# 4x16MUX_3.net
KiCad netlist of a schematic drawn in EAGLE
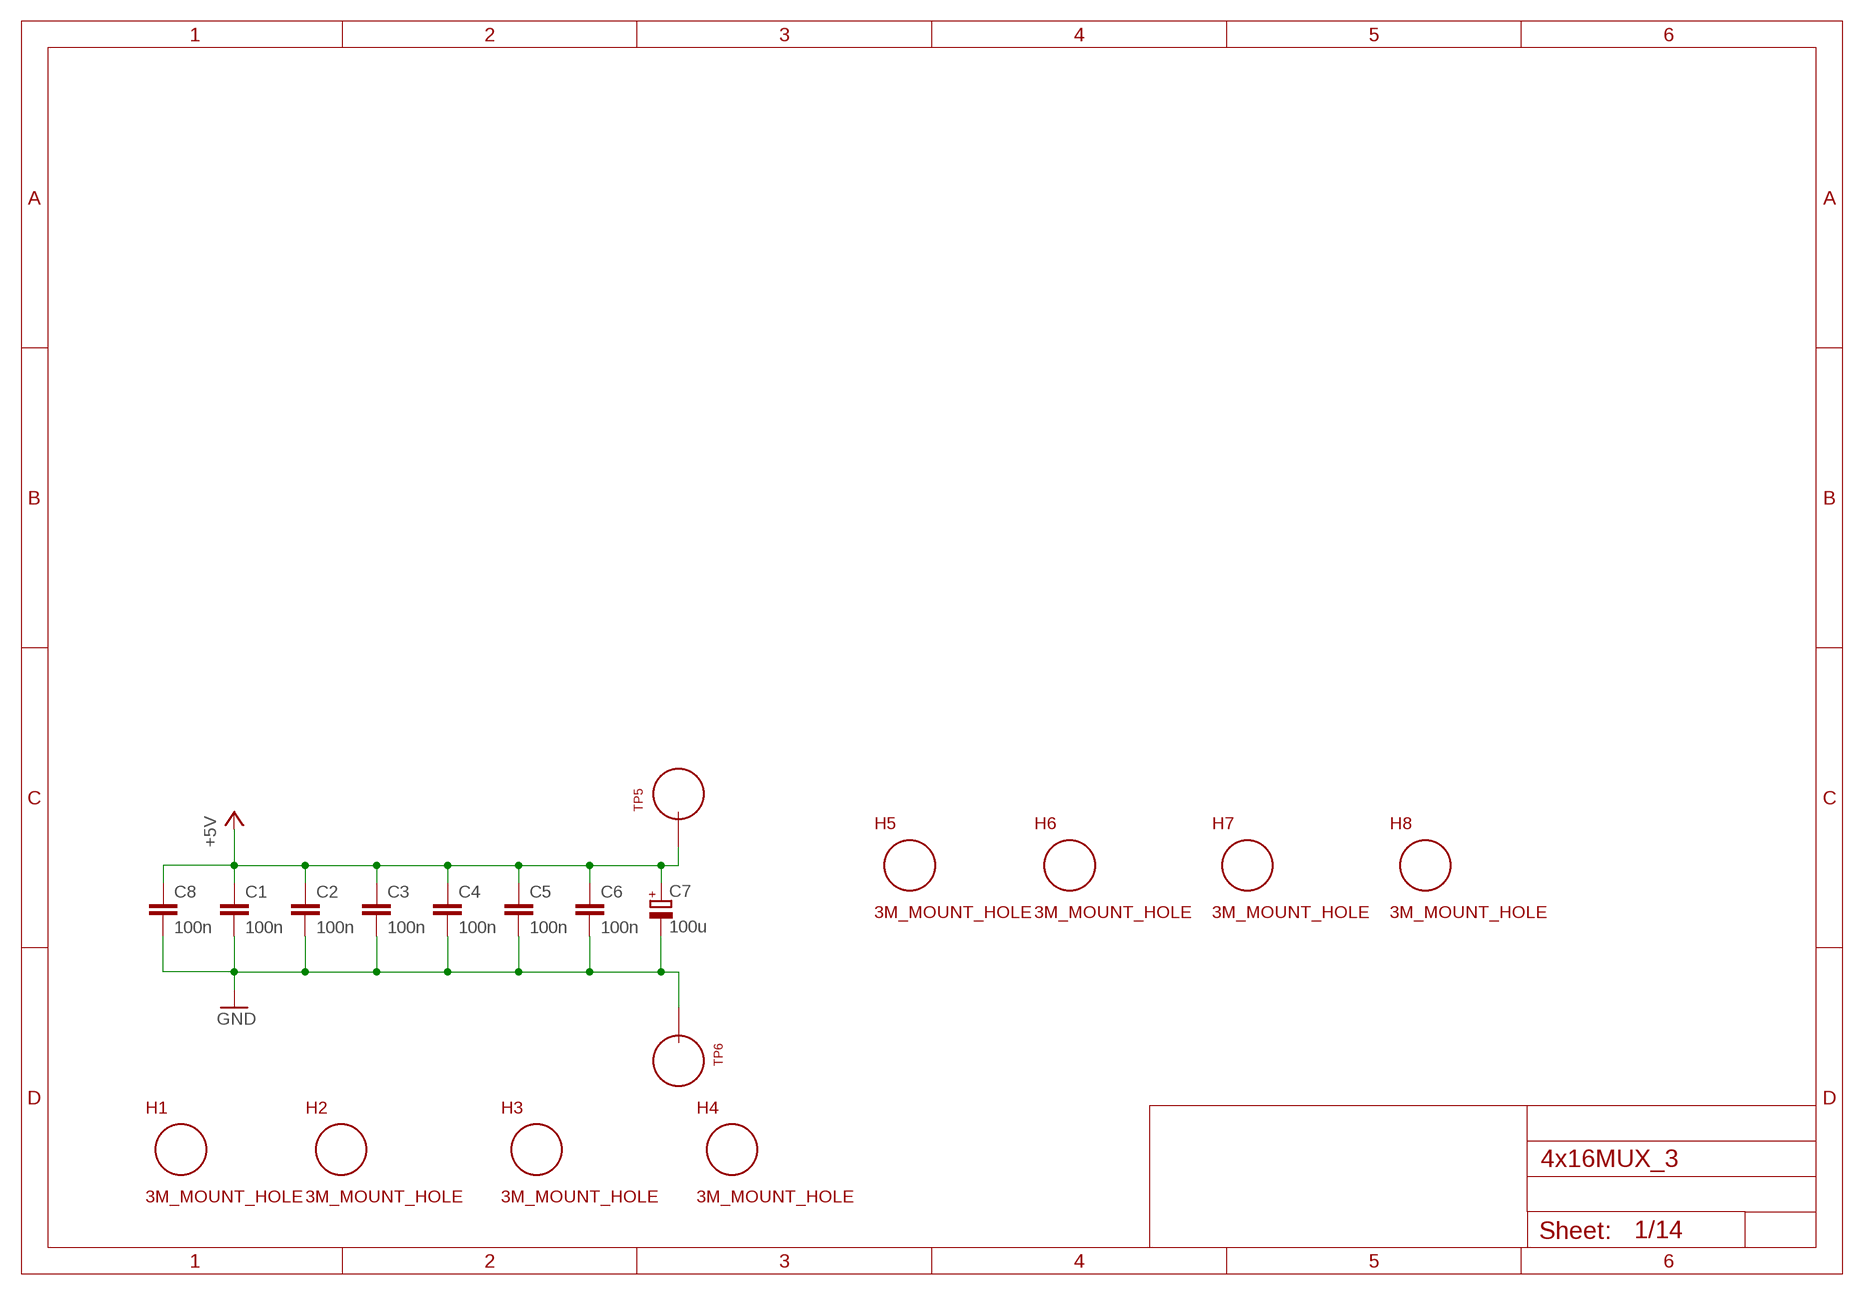
[diagram p0: schematic, sheet 1]
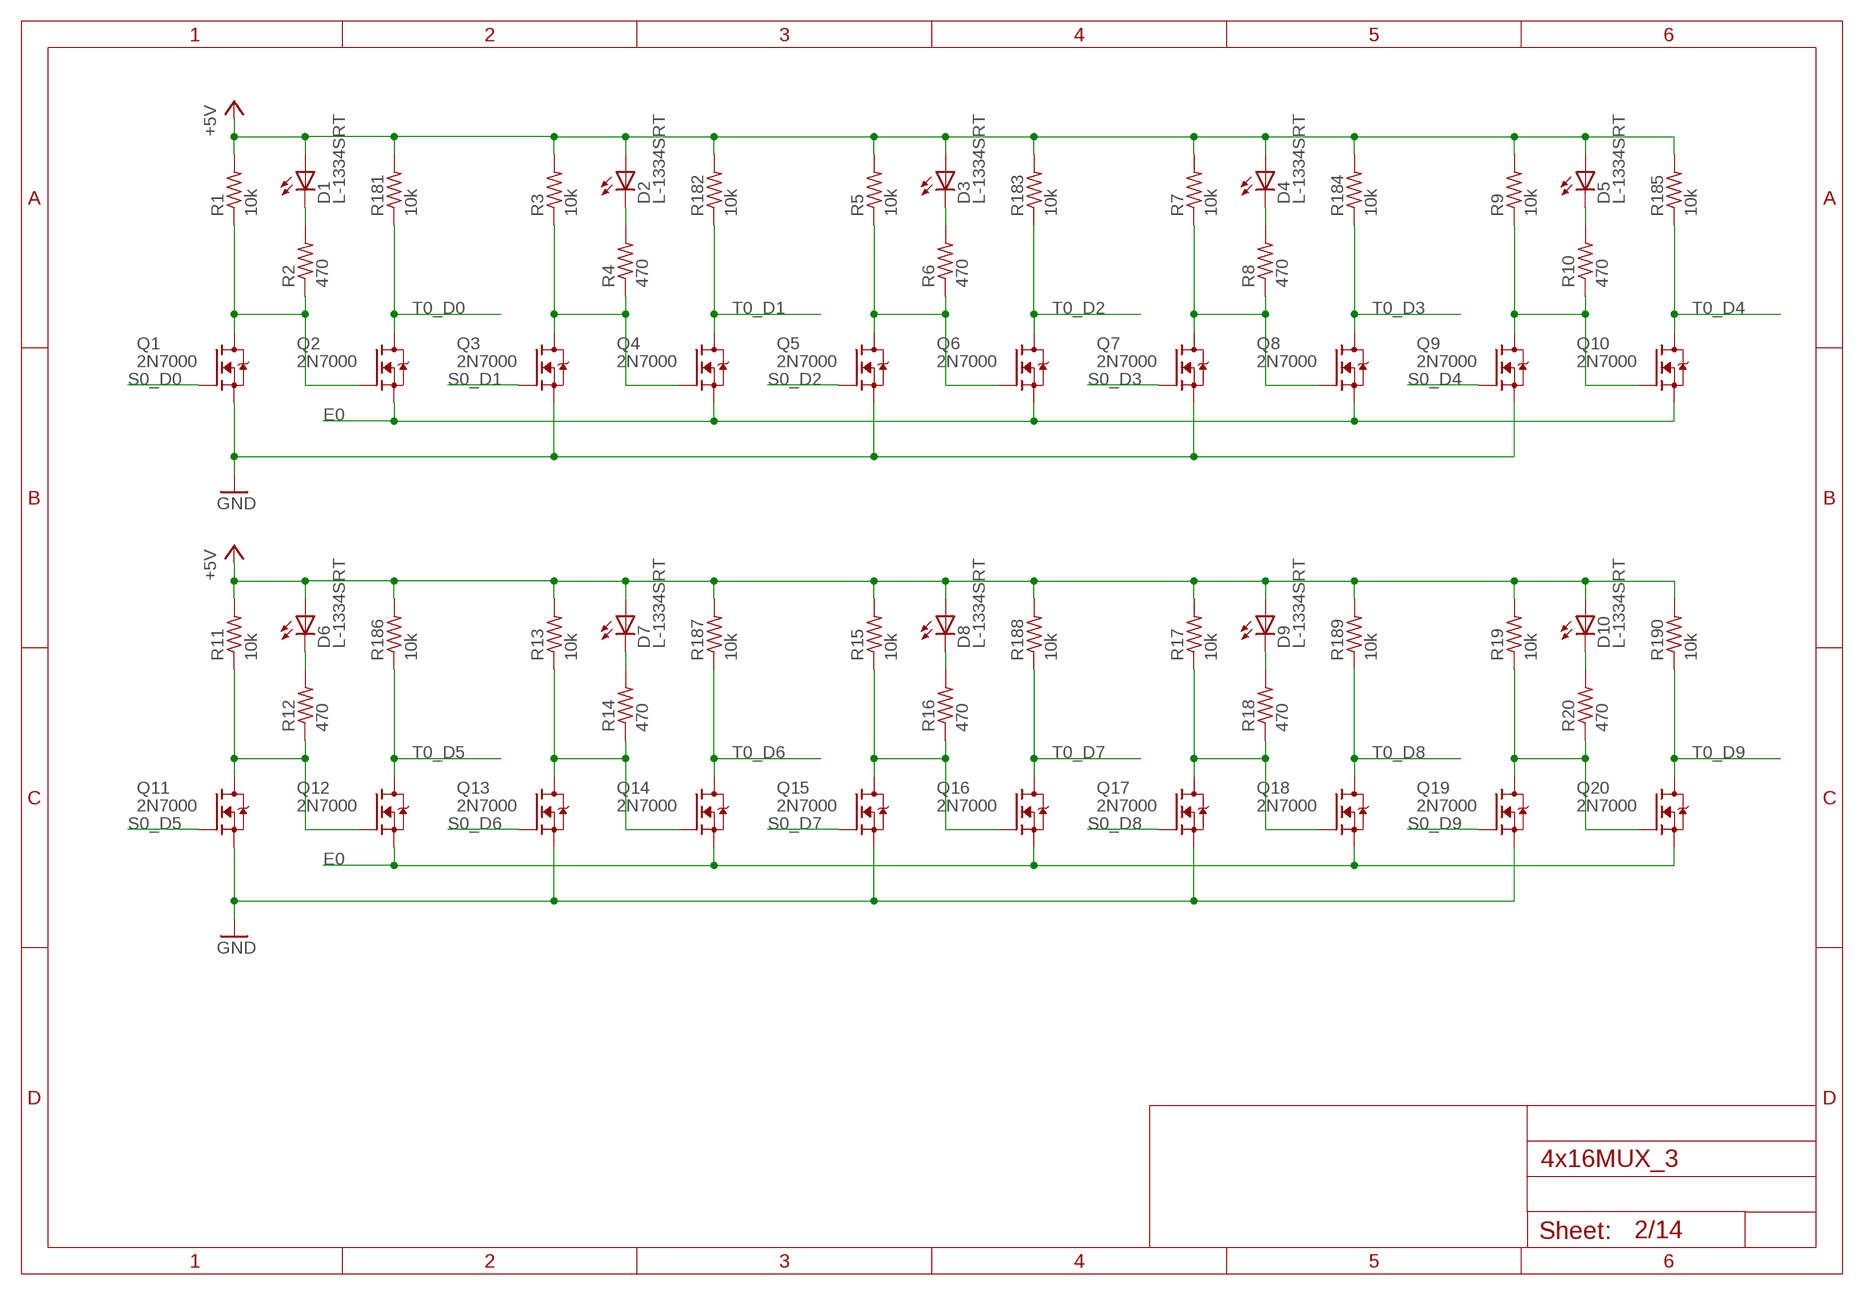
[diagram p1: schematic, sheet 2]
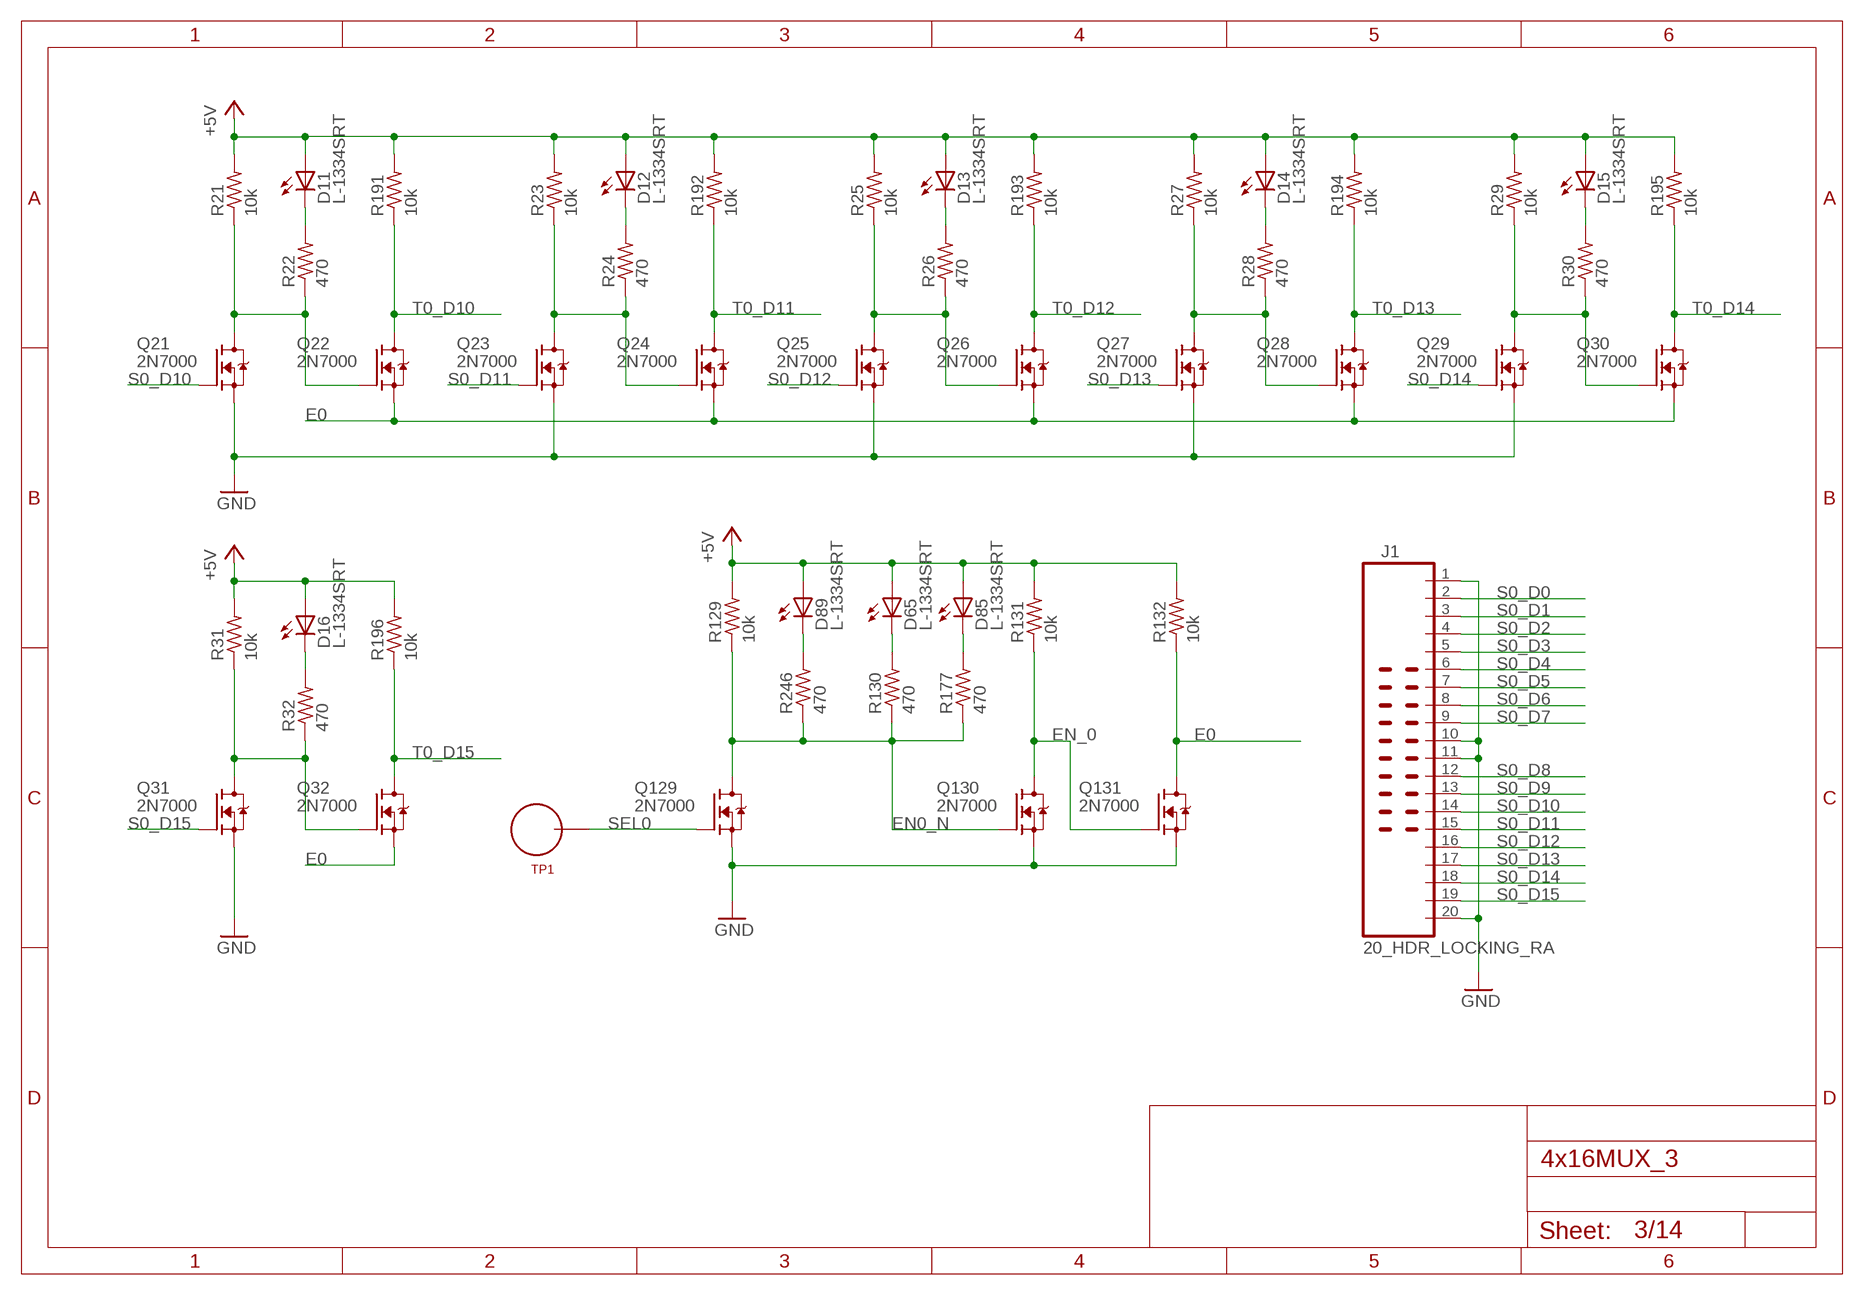
[diagram p2: schematic, sheet 3]
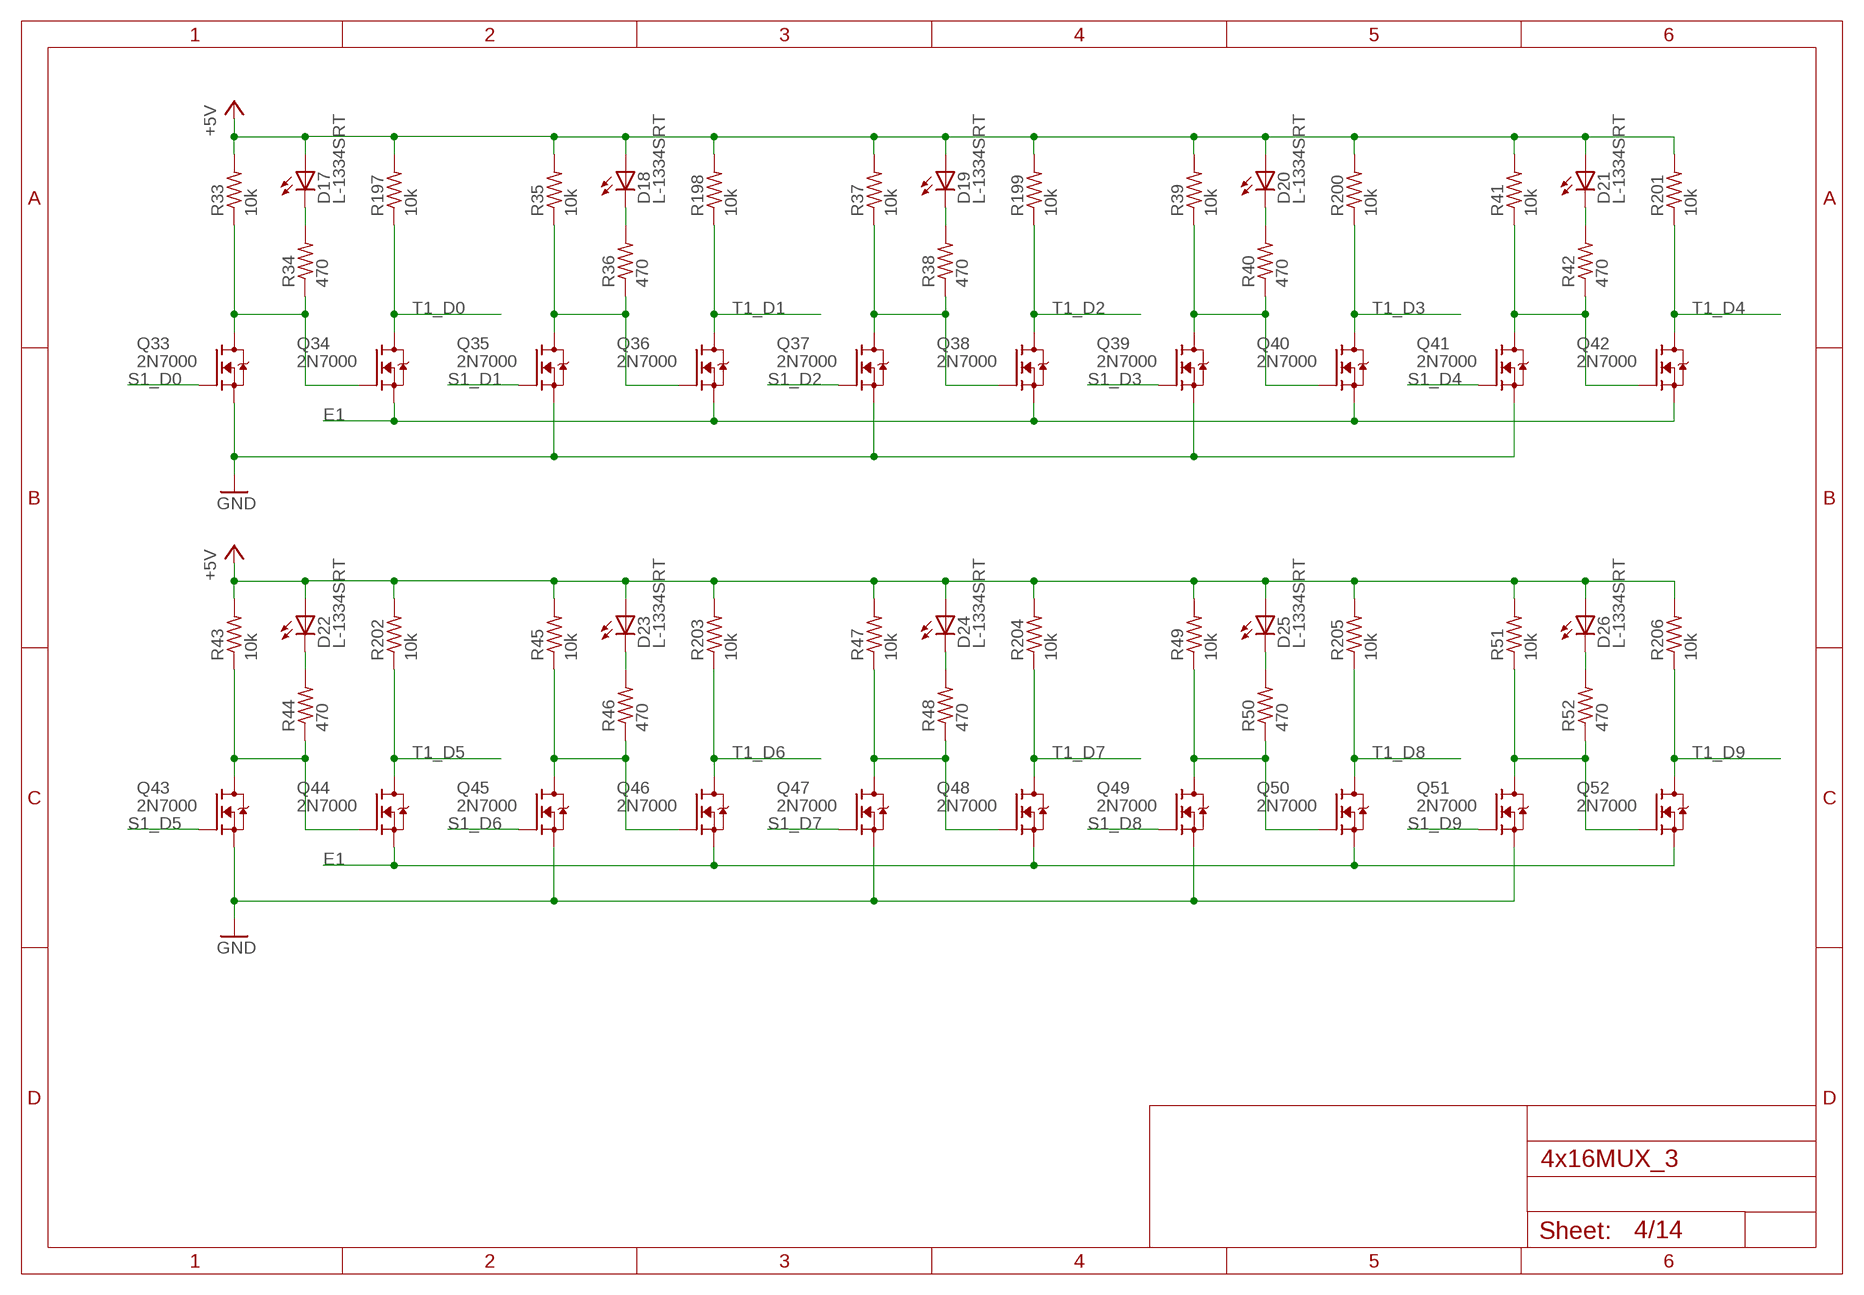
[diagram p3: schematic, sheet 4]
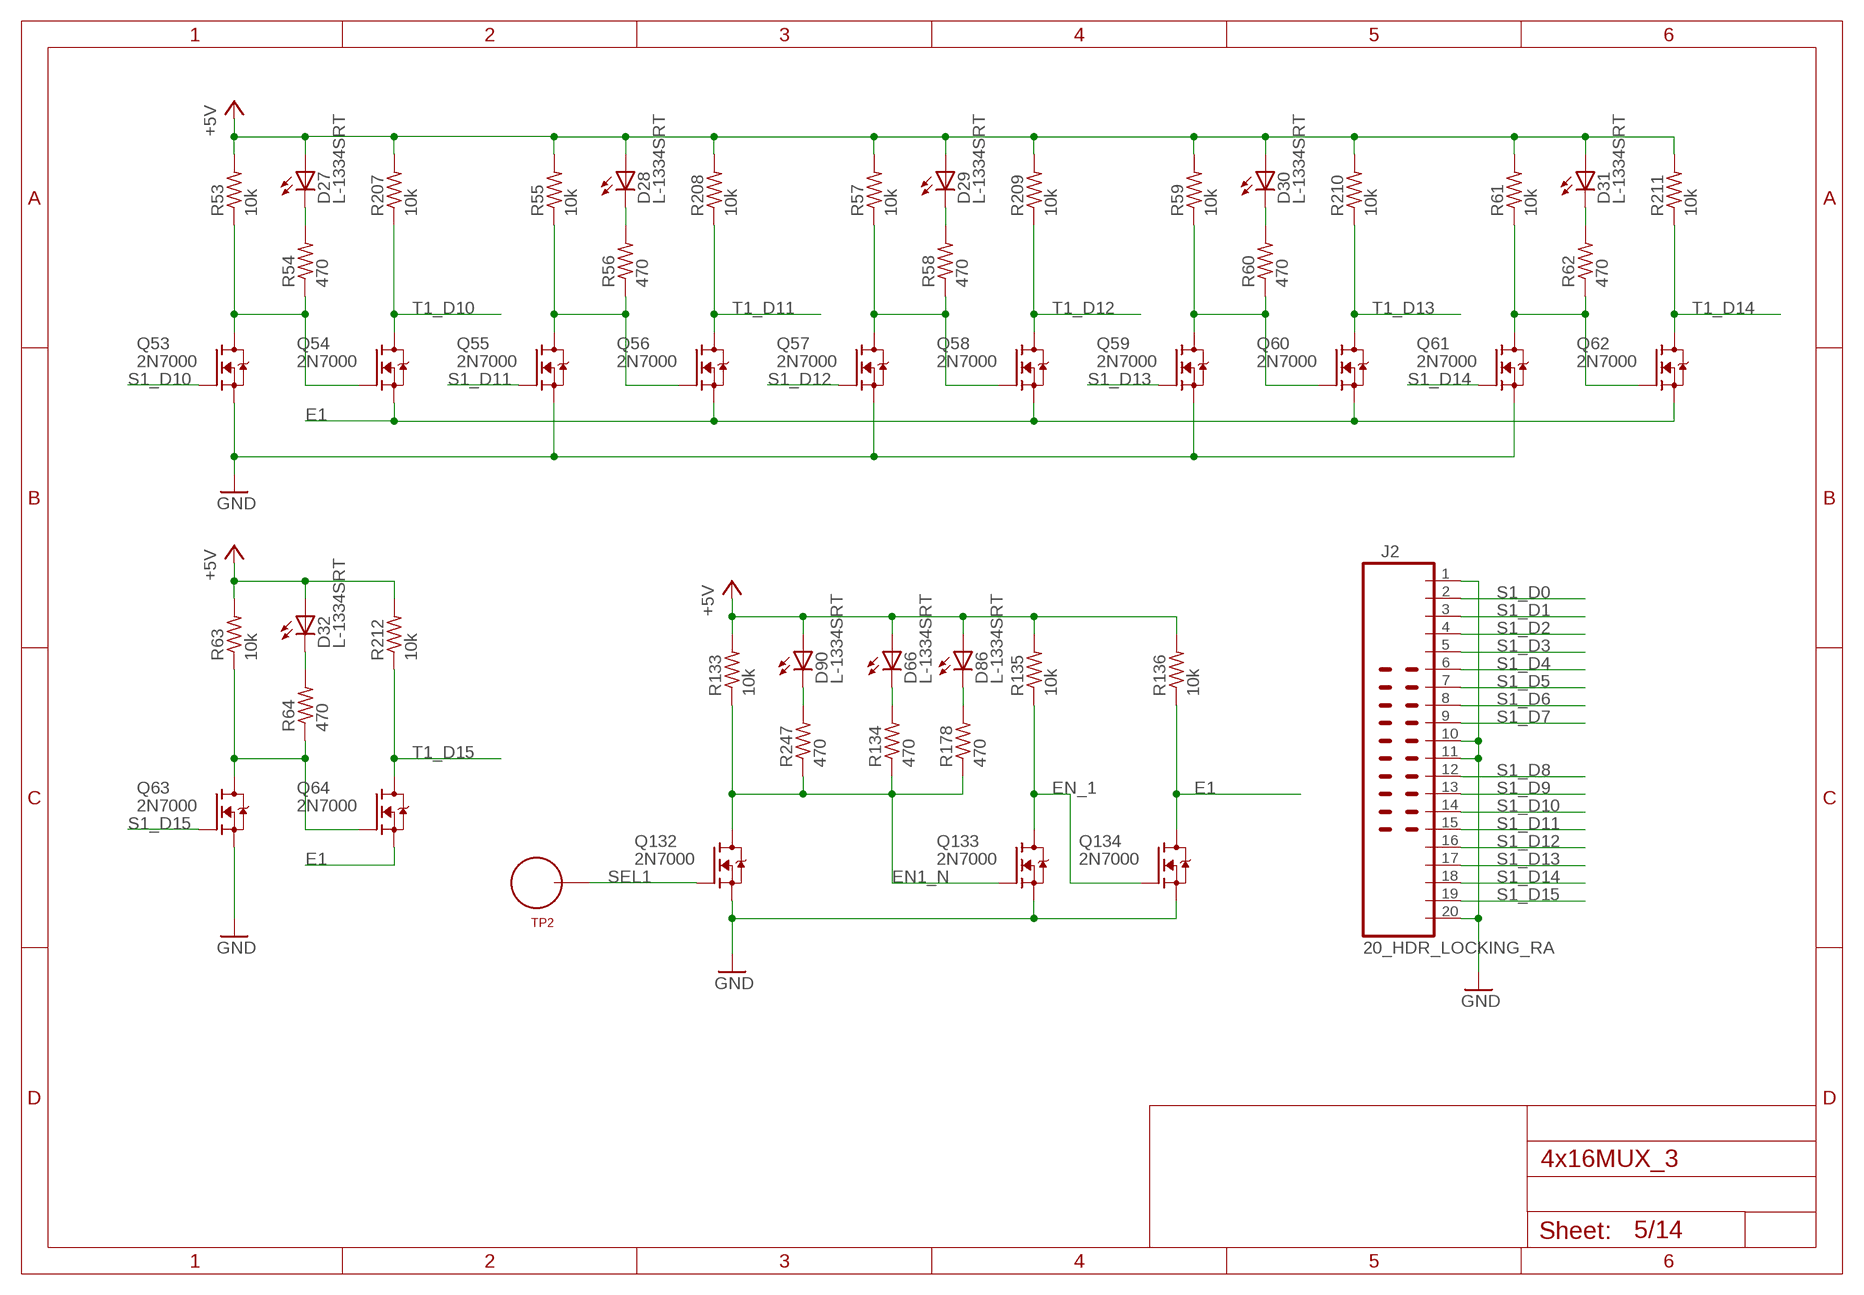
[diagram p4: schematic, sheet 5]
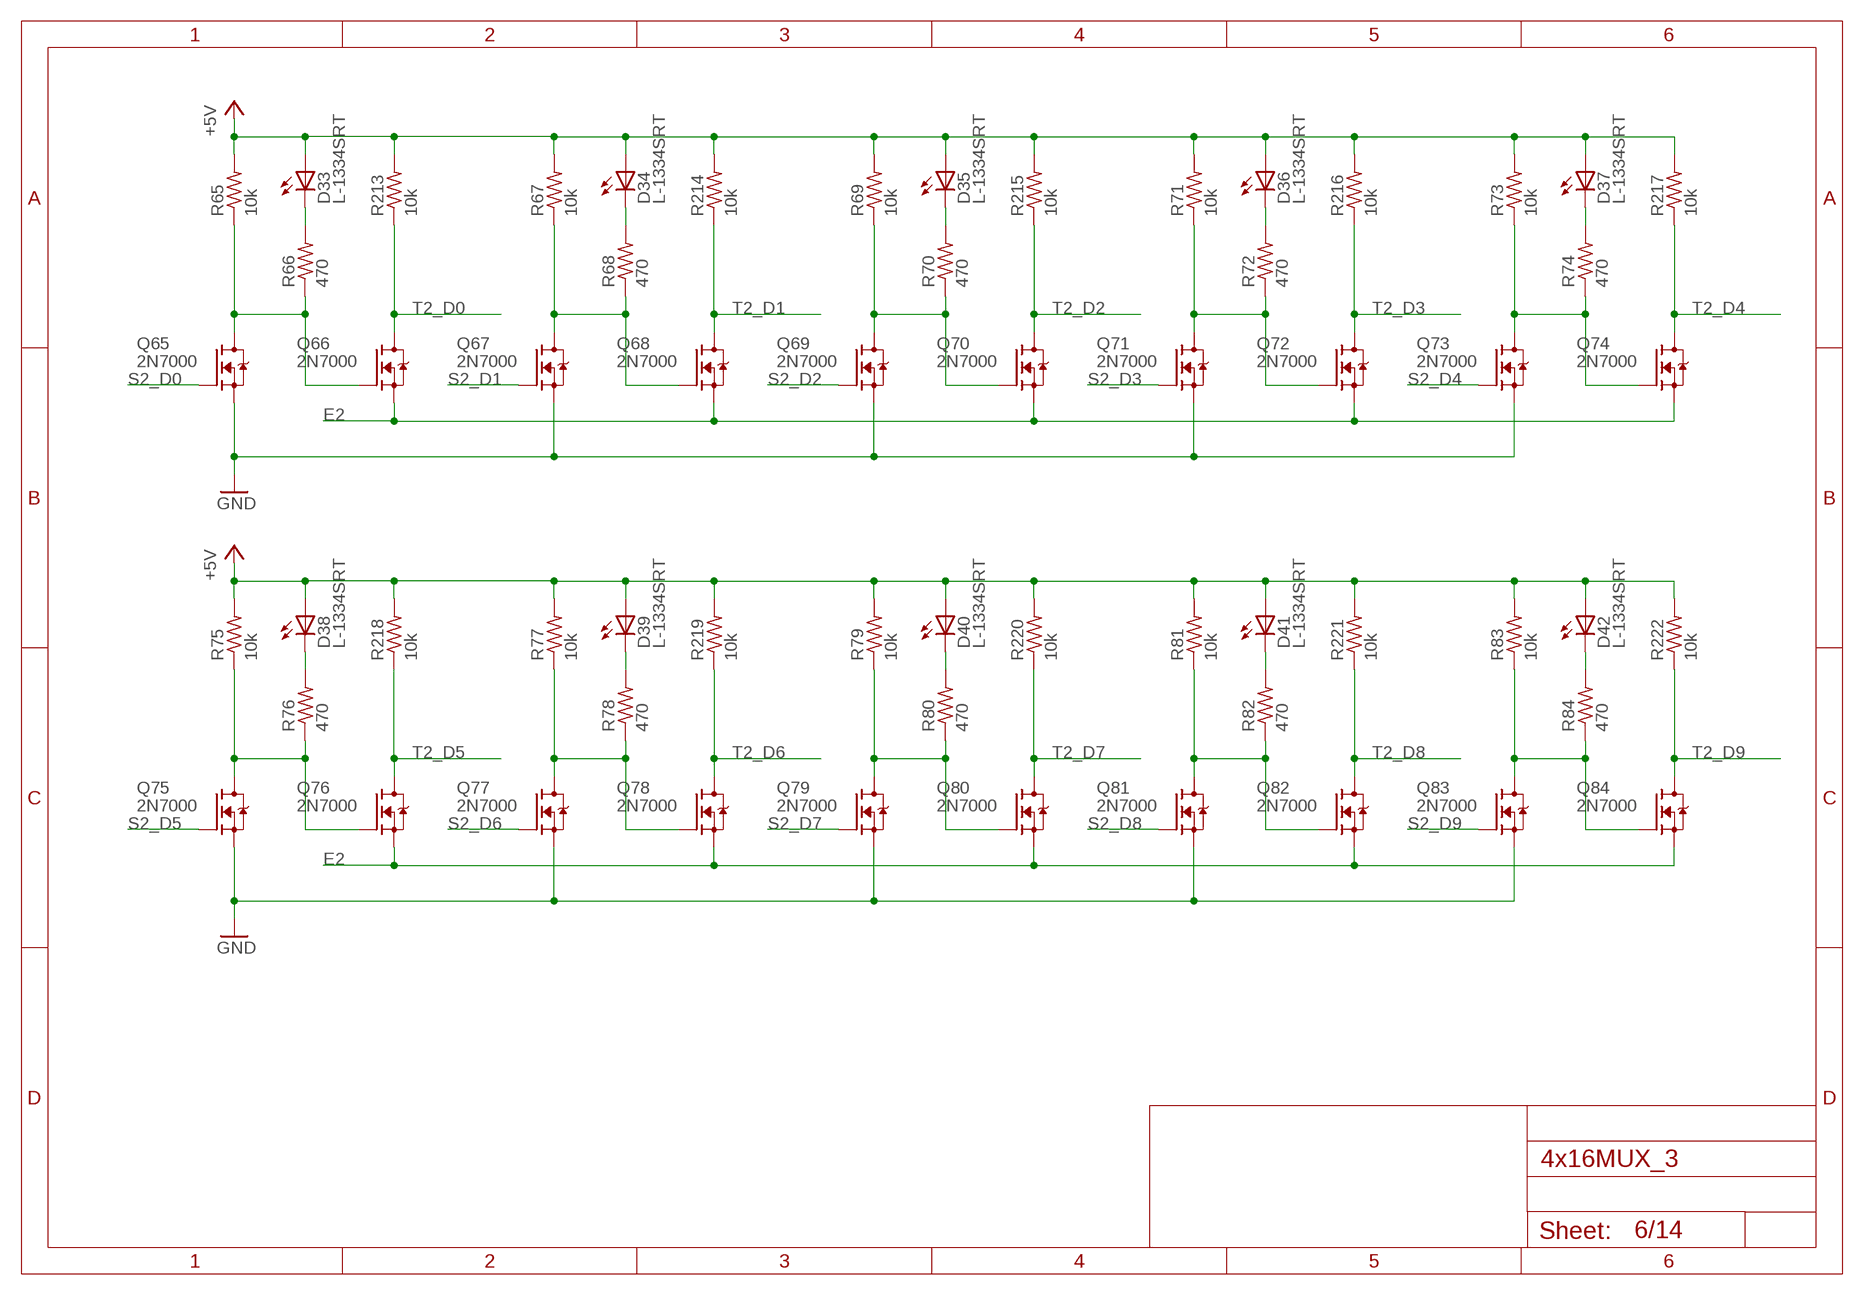
[diagram p5: schematic, sheet 6]
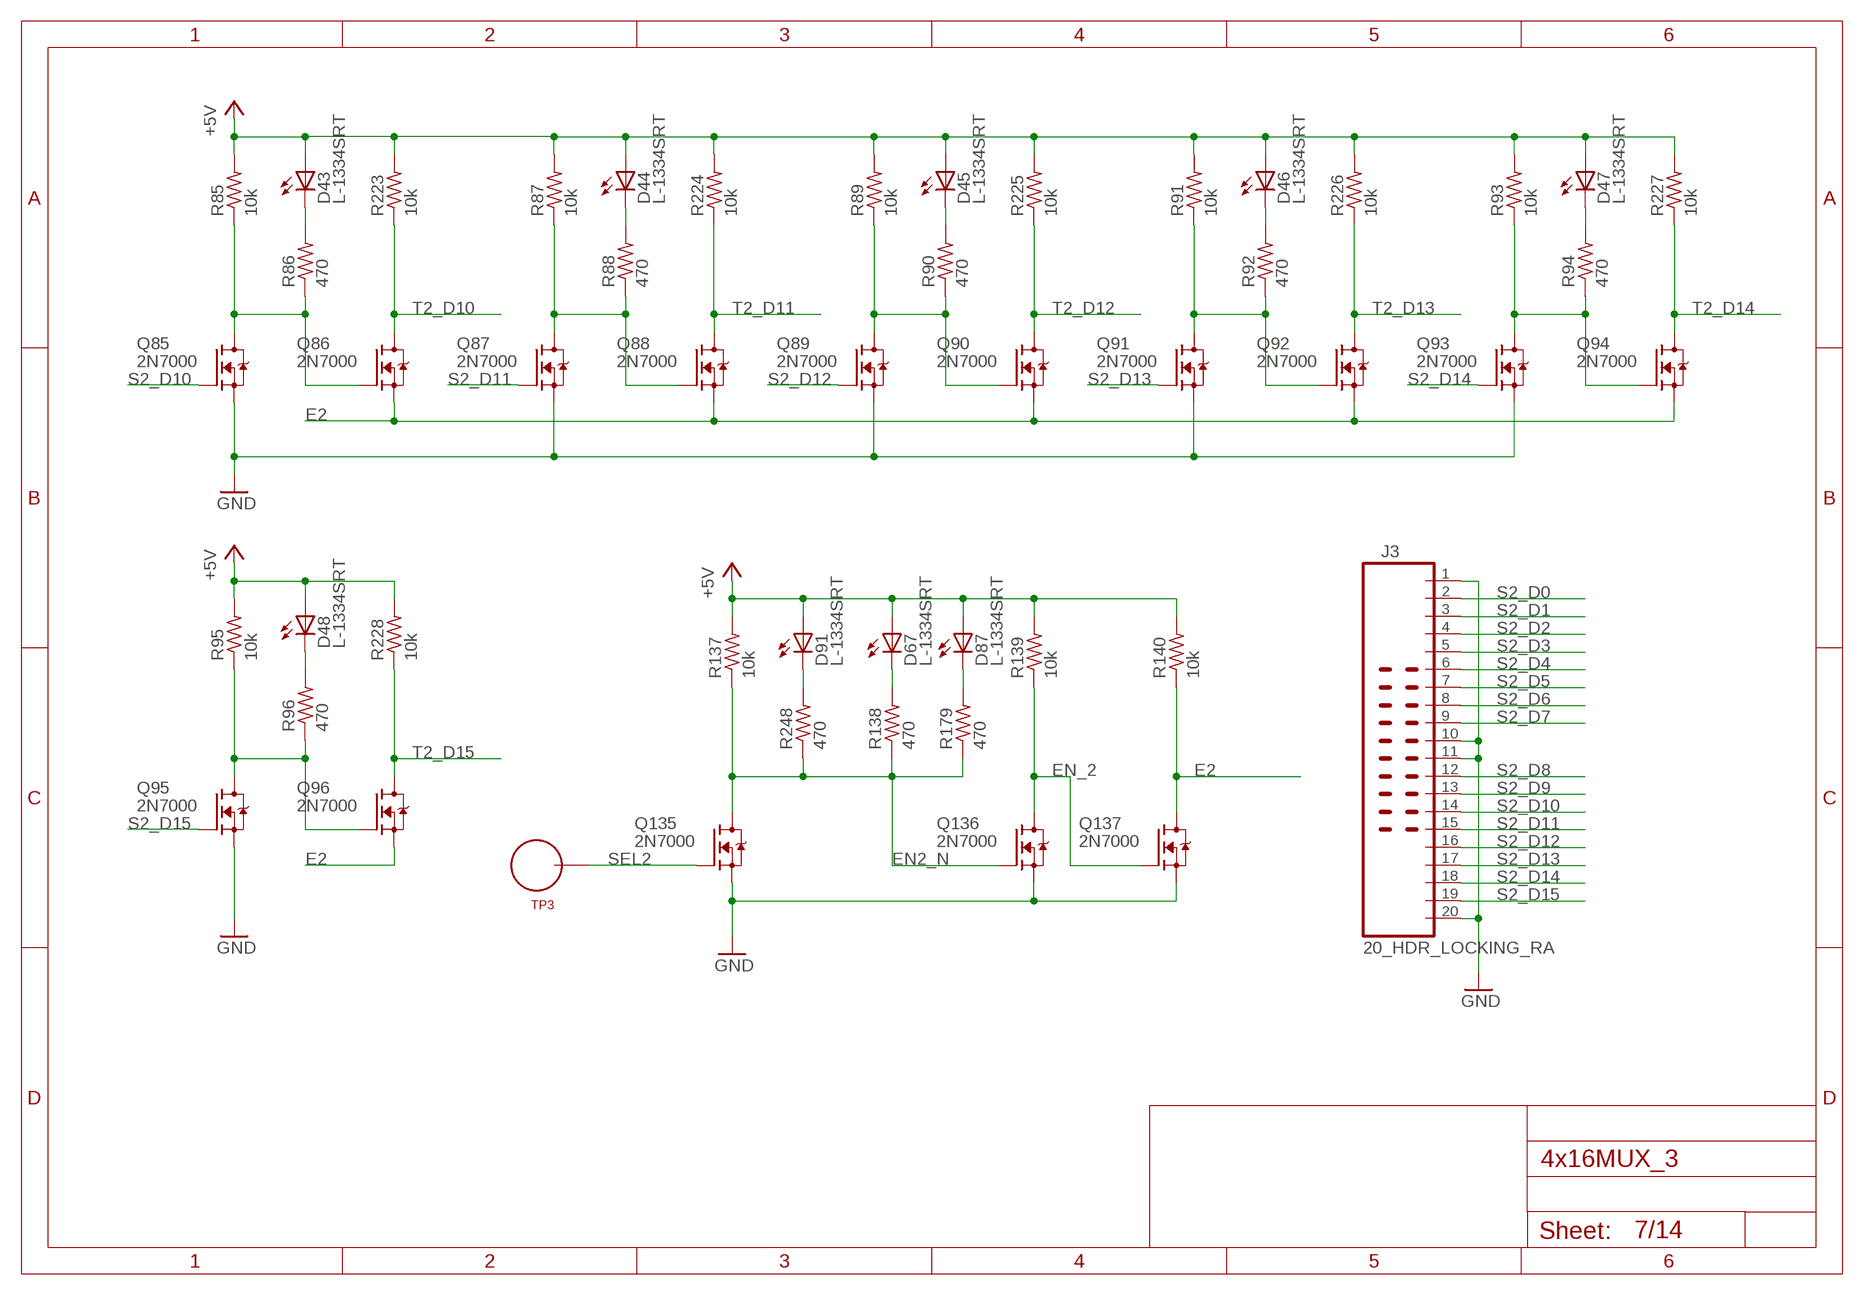
[diagram p6: schematic, sheet 7]
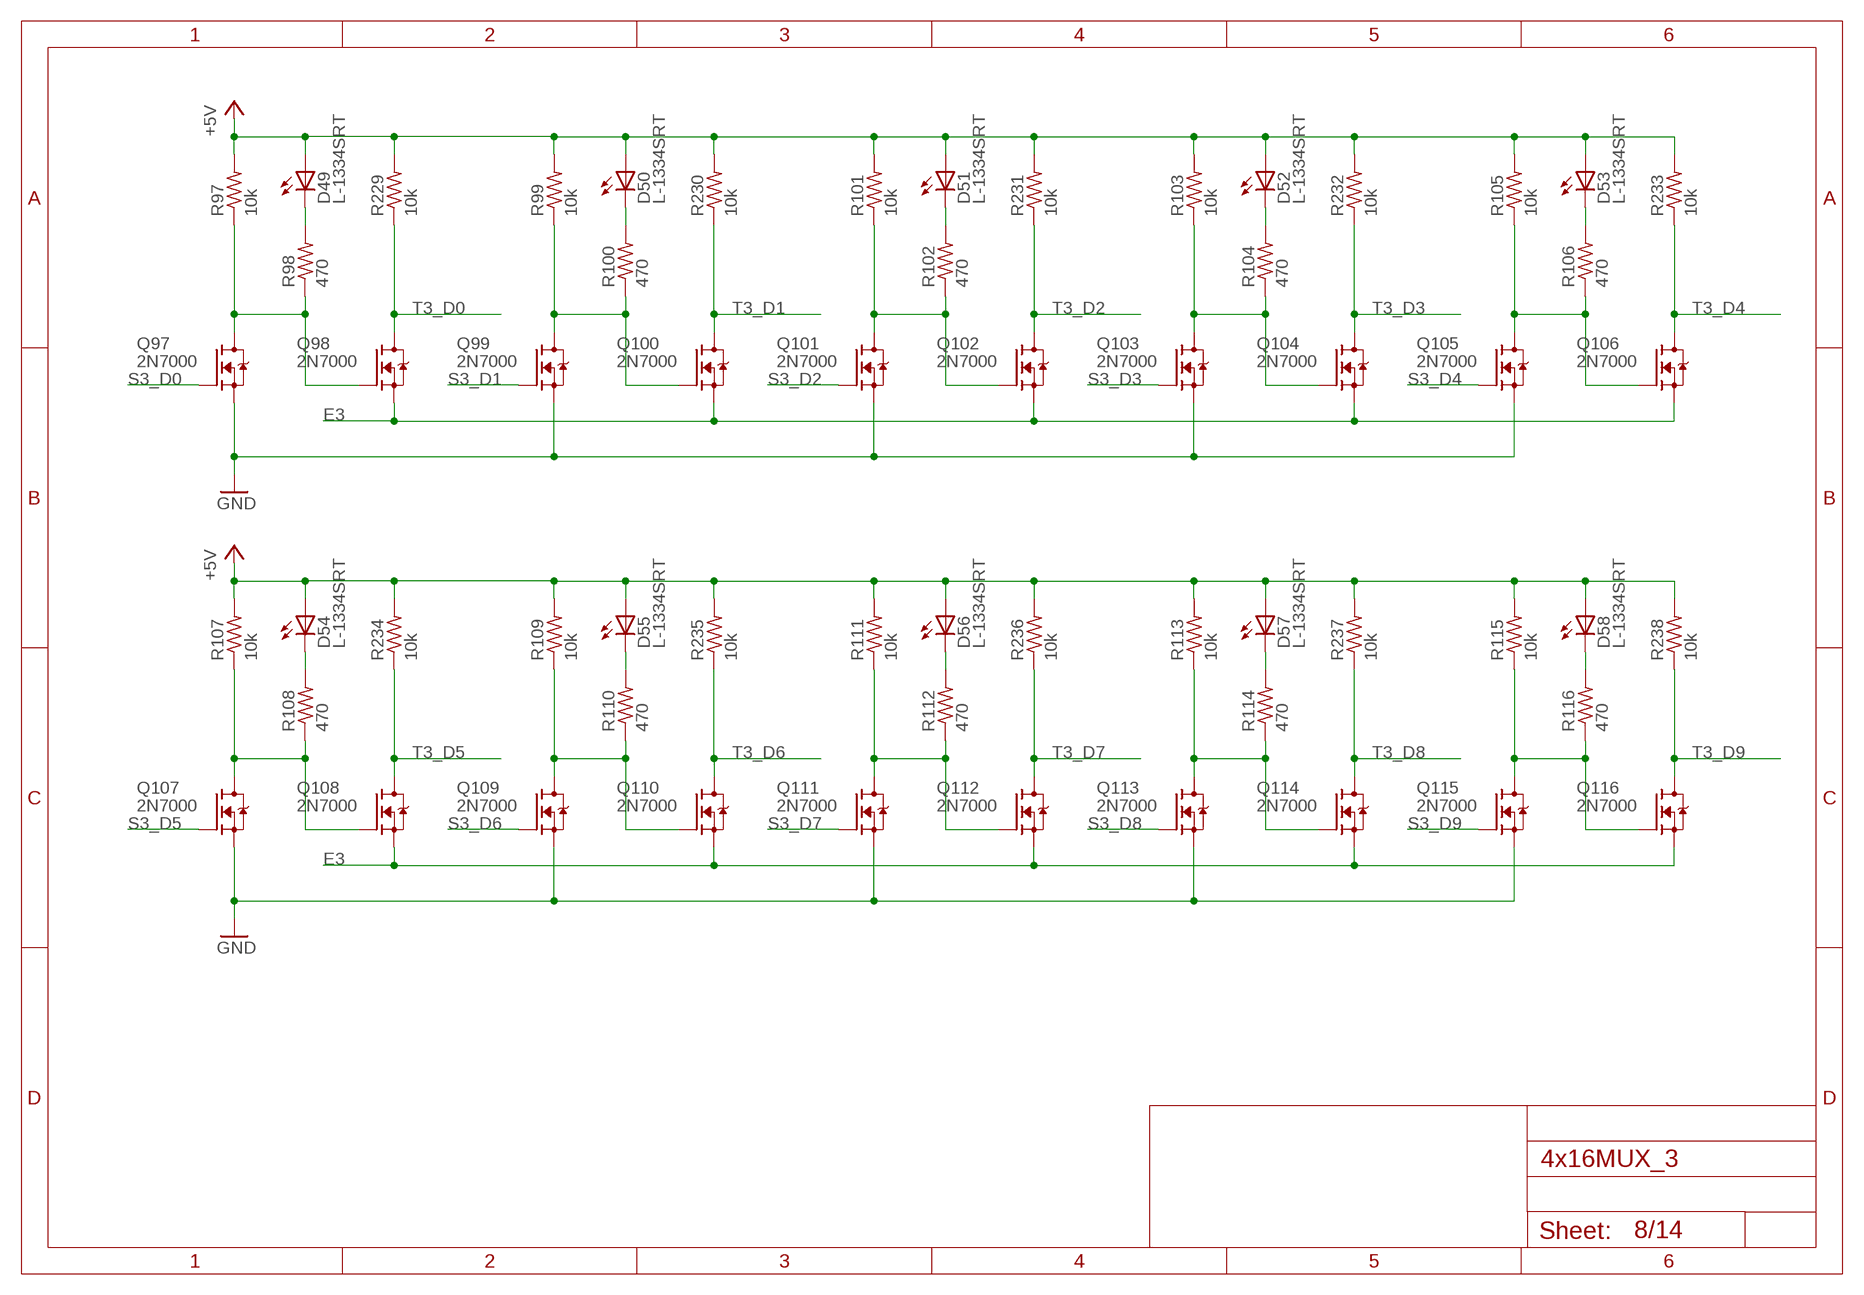
[diagram p7: schematic, sheet 8]
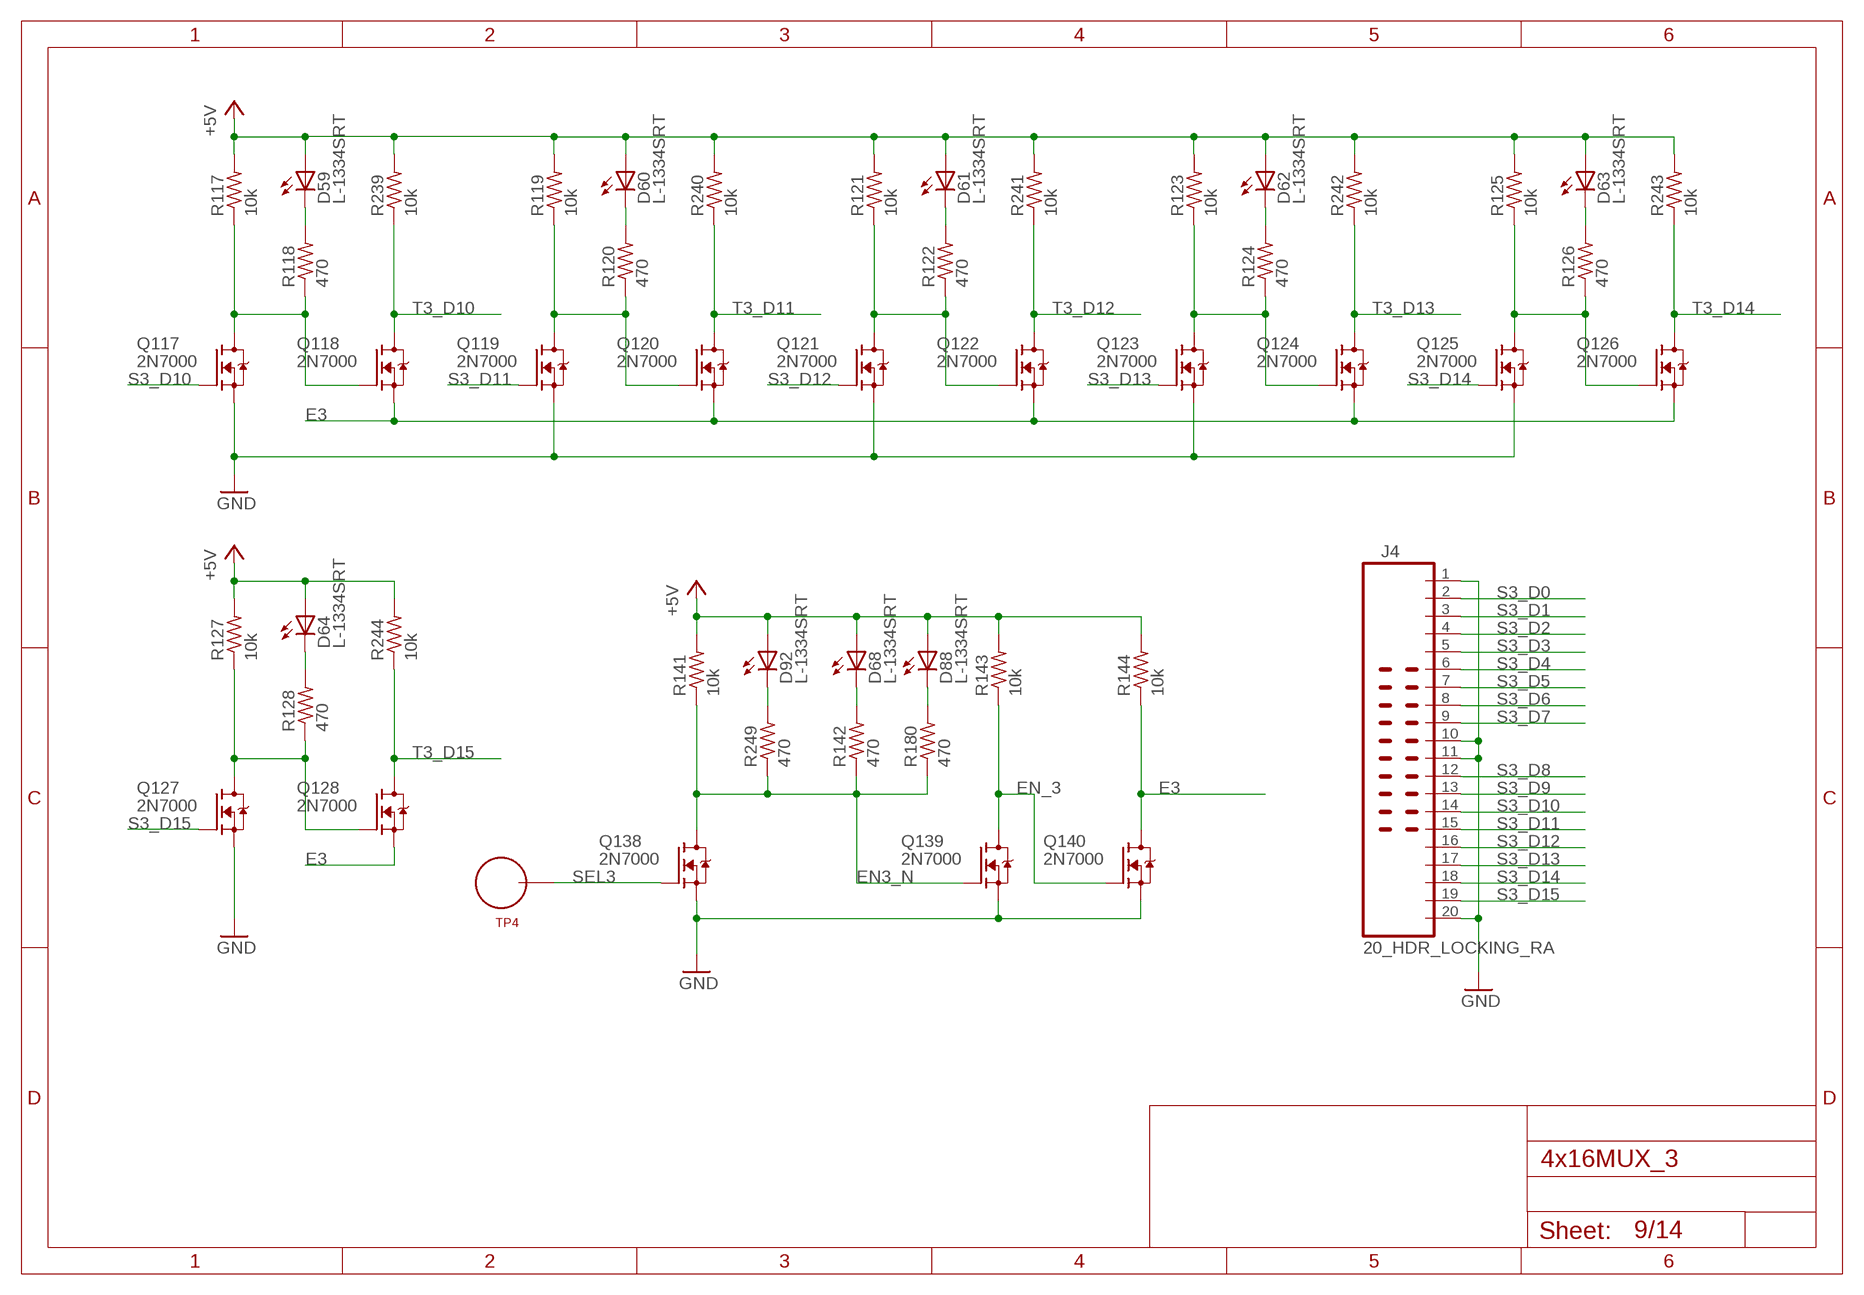
[diagram p8: schematic, sheet 9]
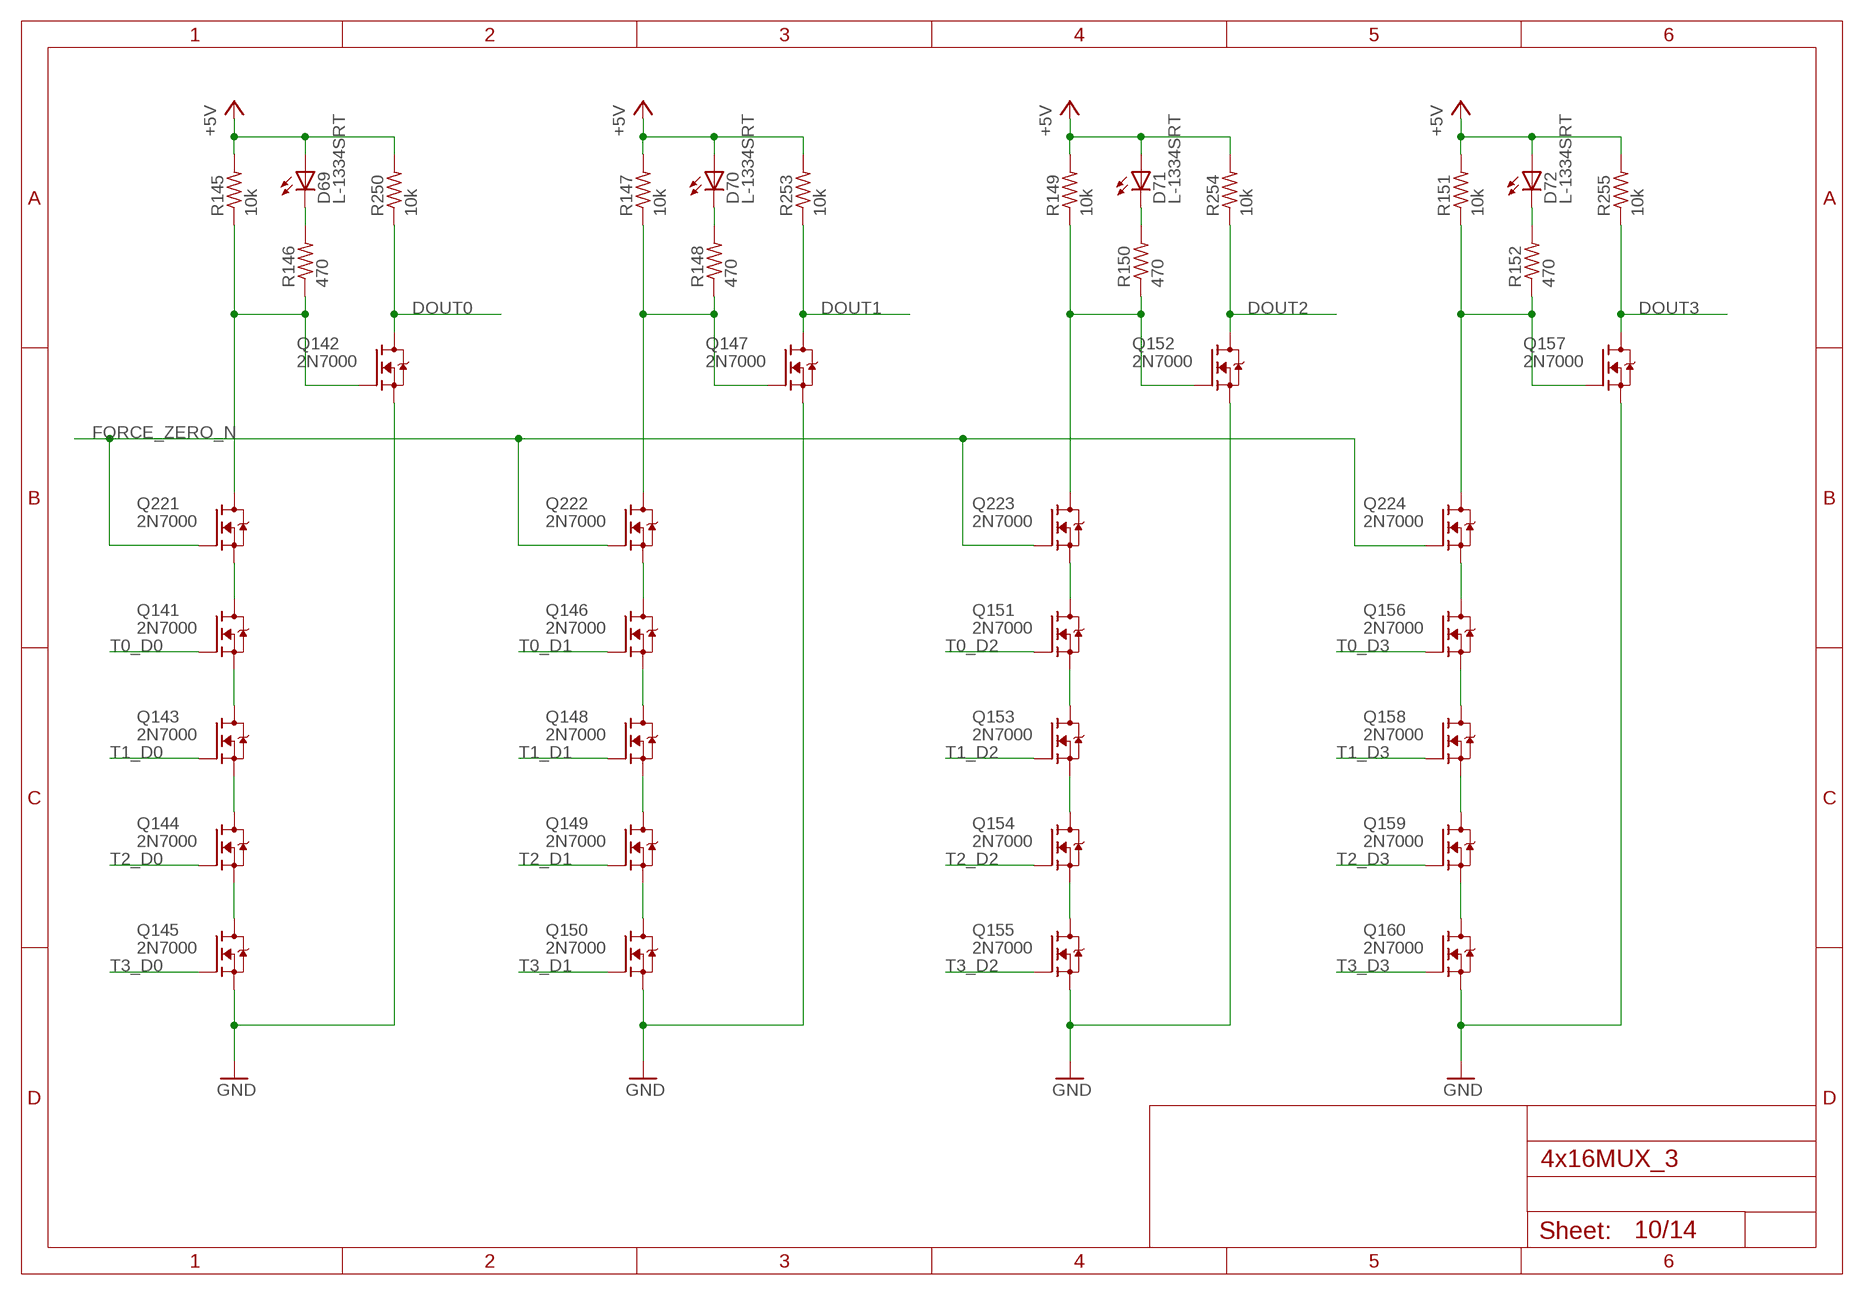
[diagram p9: schematic, sheet 10]
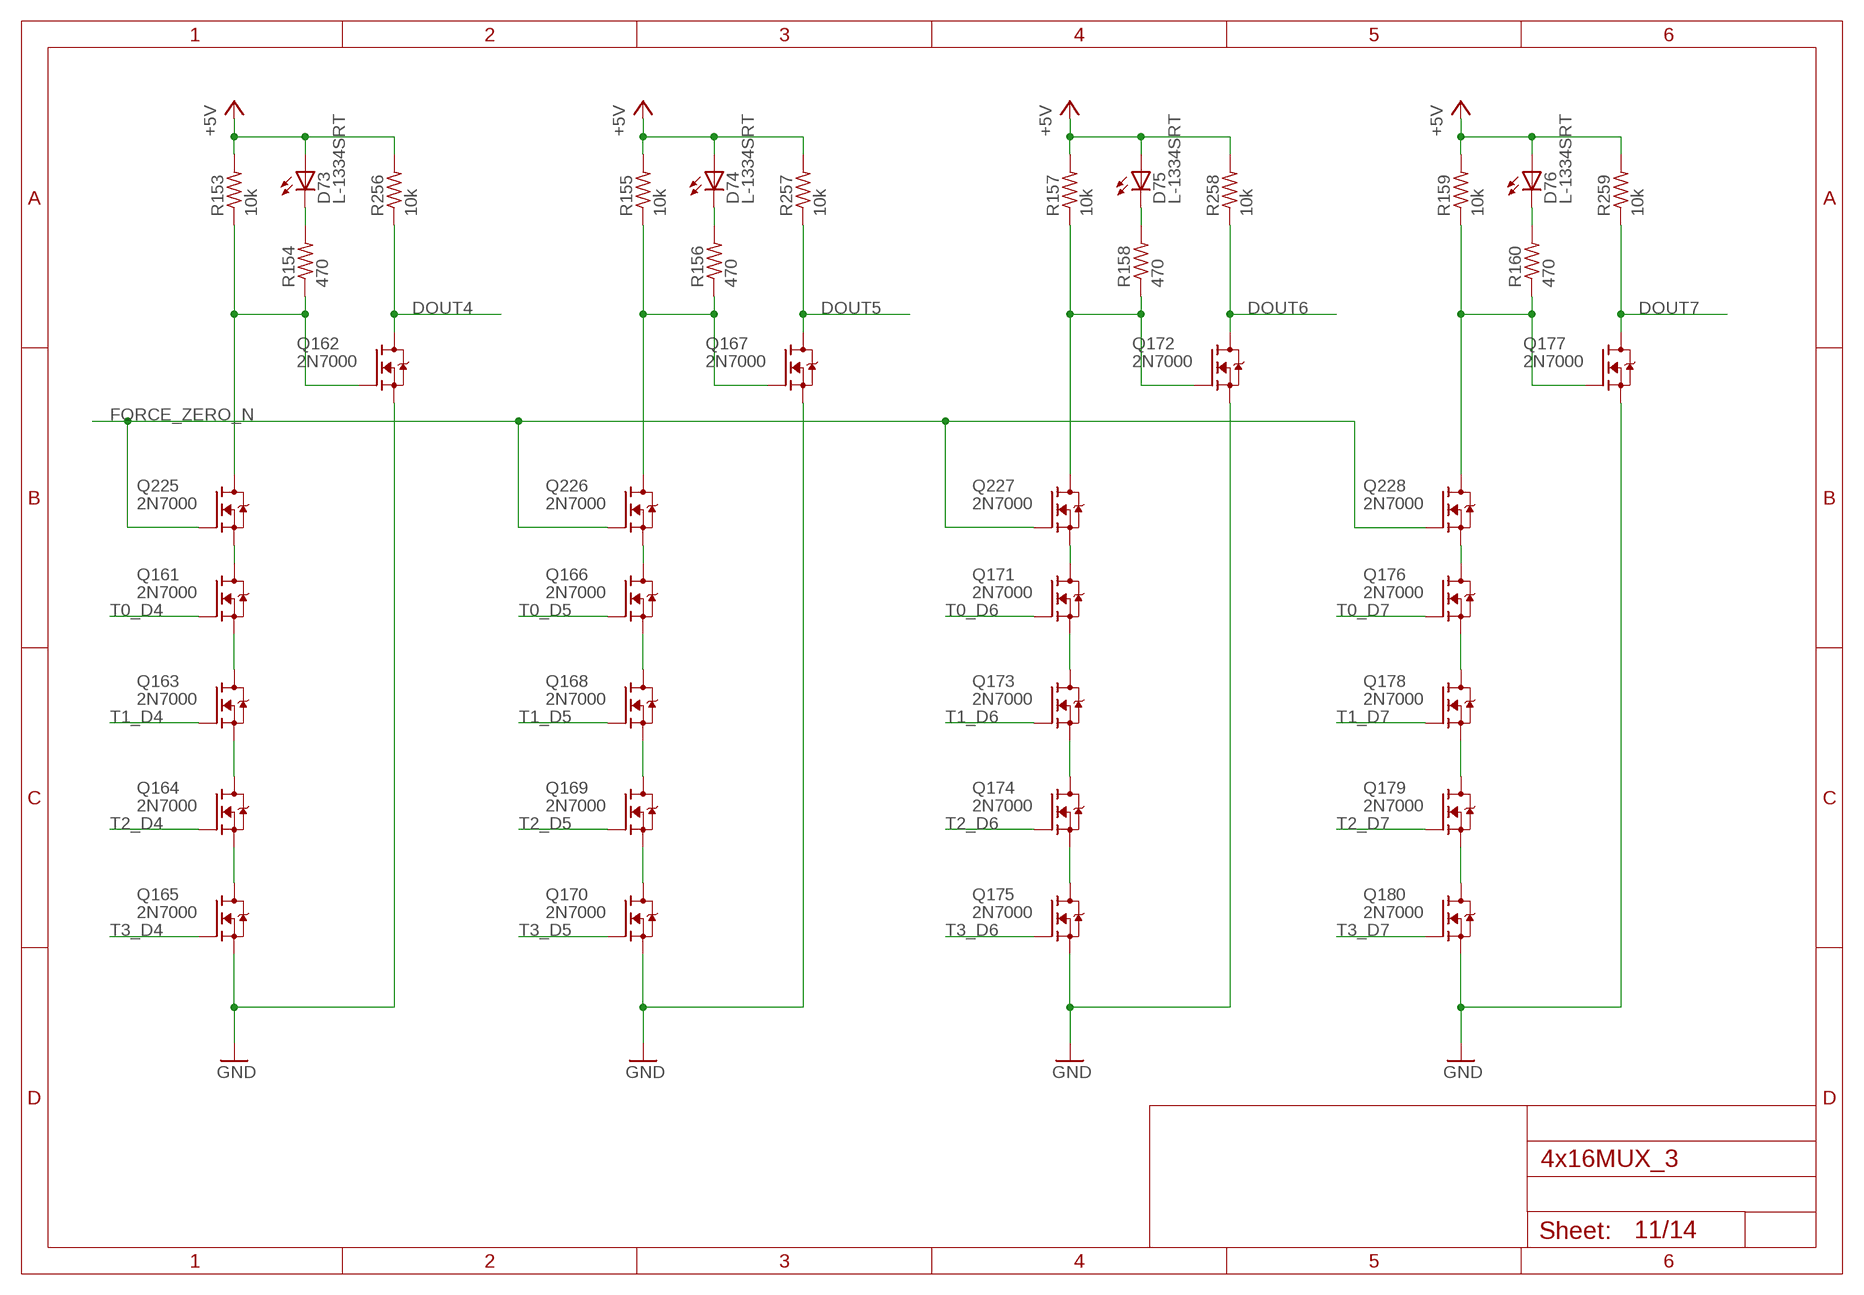
[diagram p10: schematic, sheet 11]
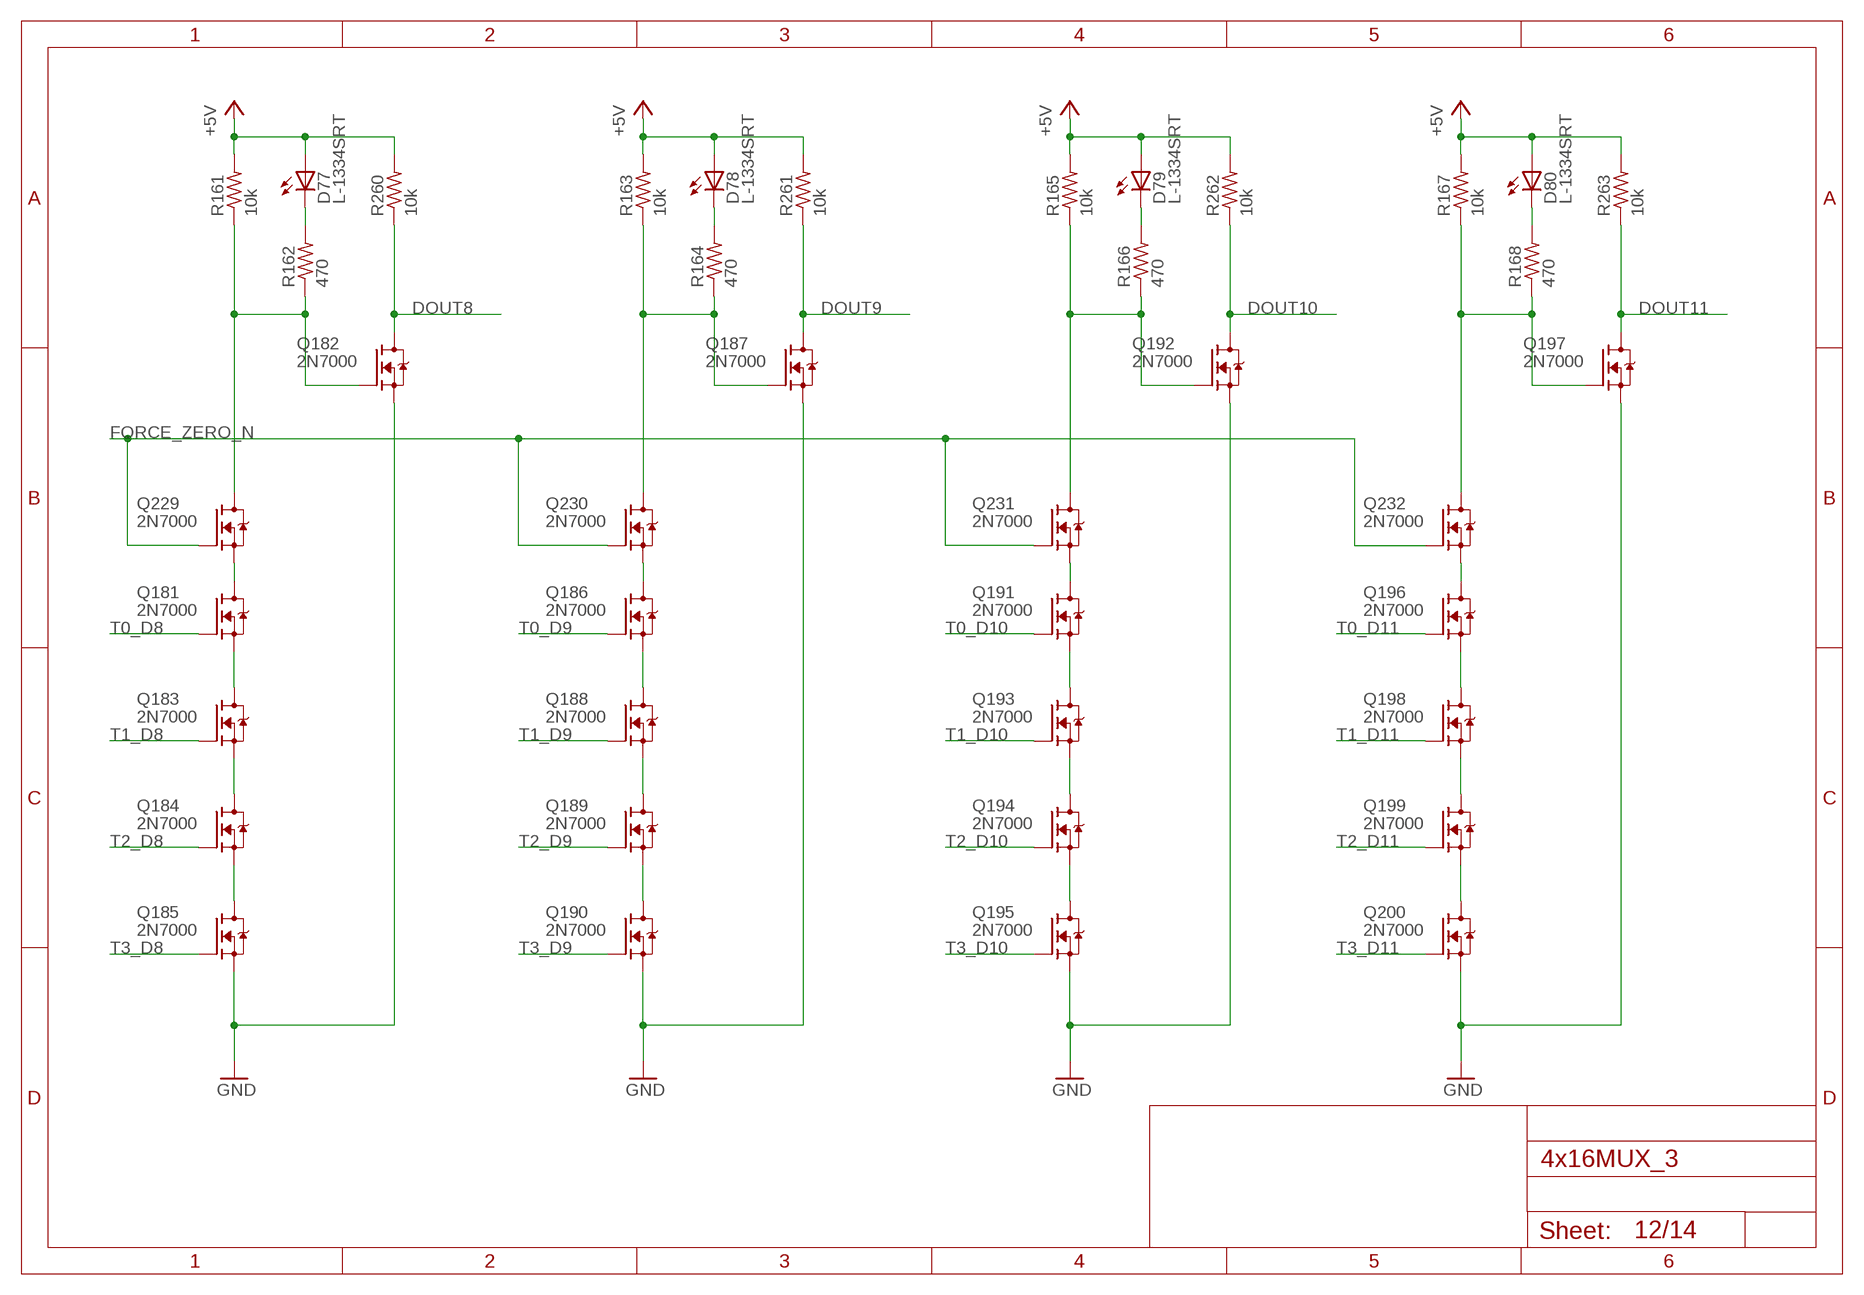
[diagram p11: schematic, sheet 12]
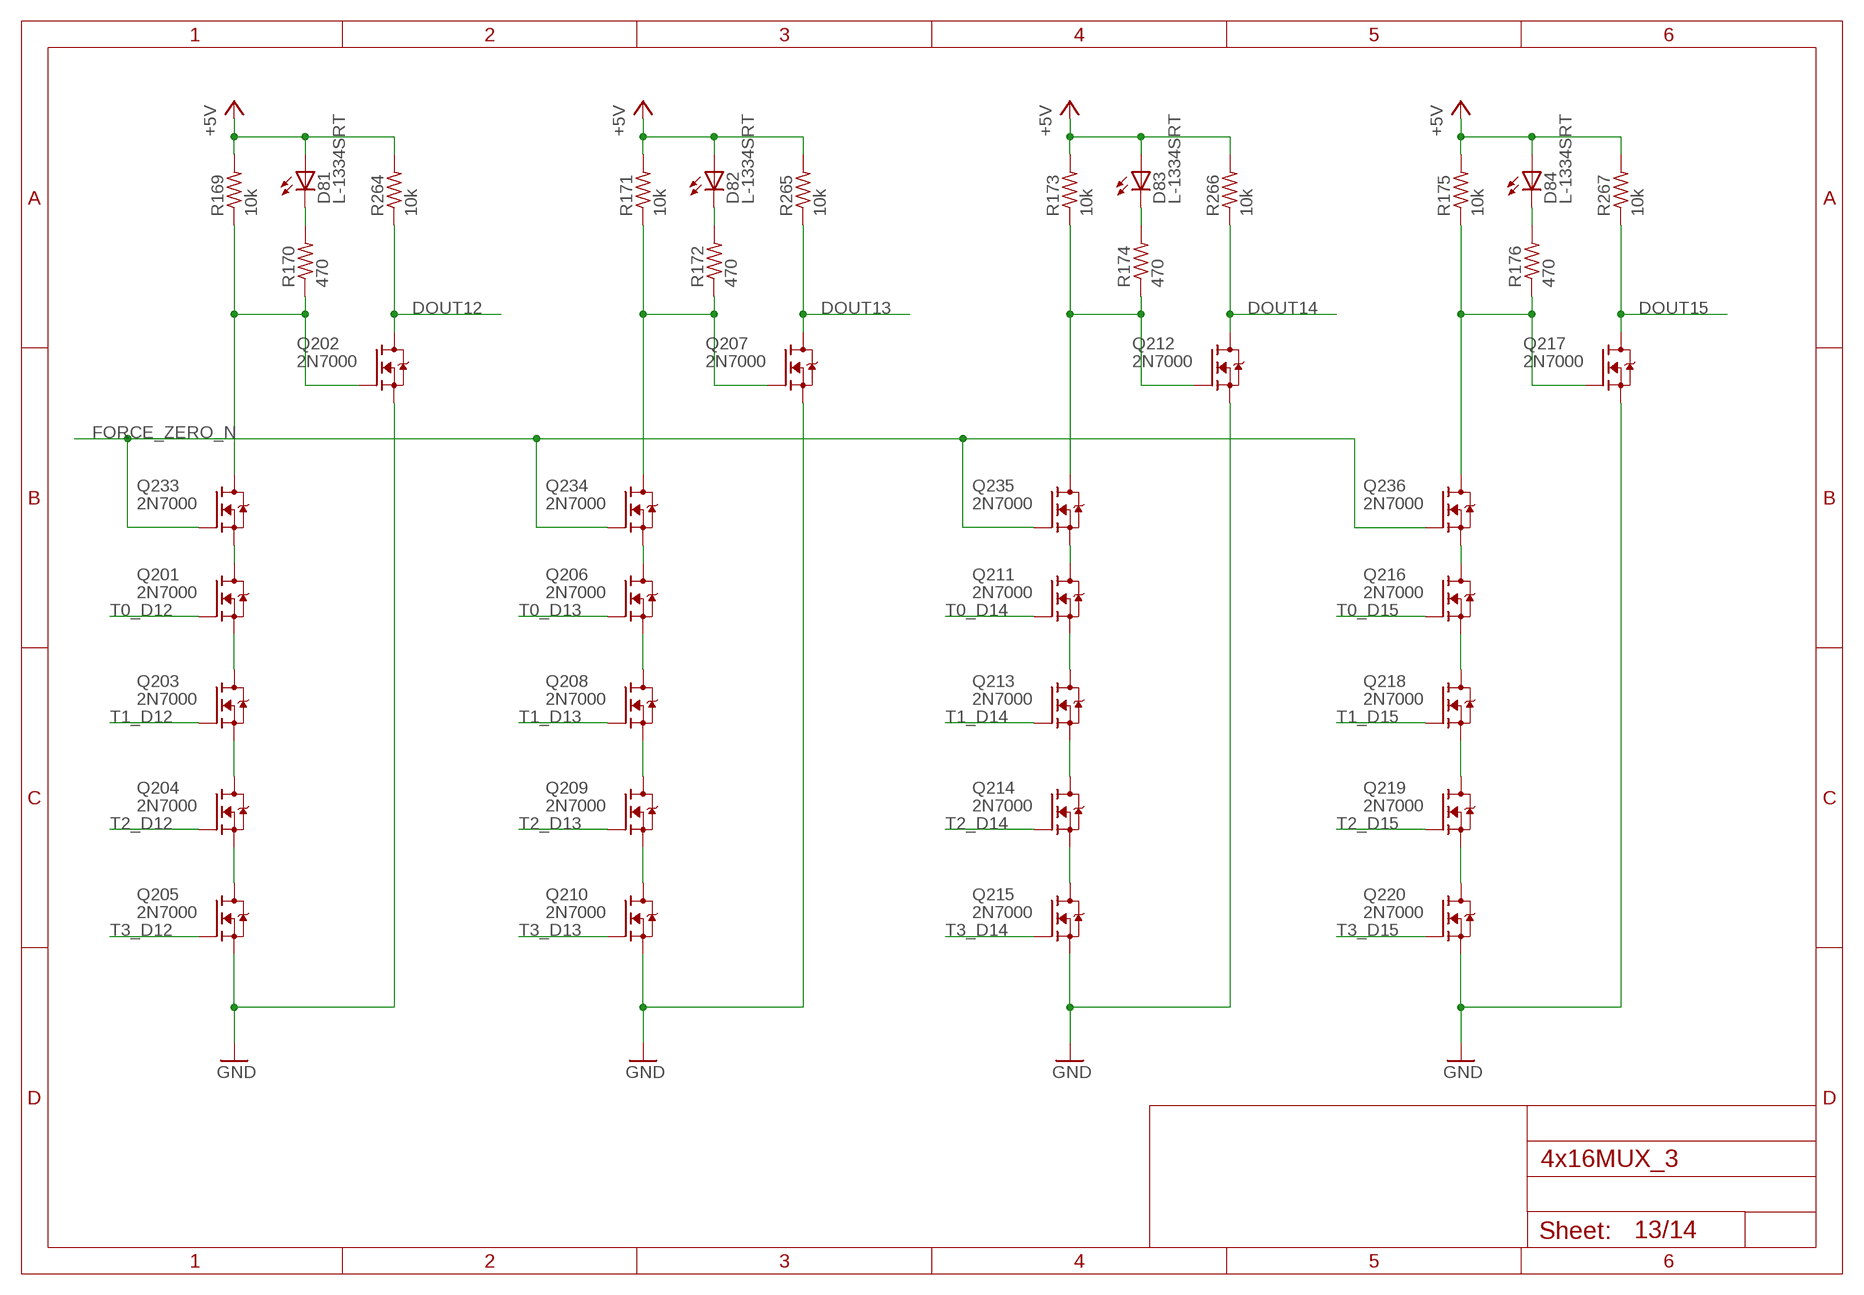
[diagram p12: schematic, sheet 13]
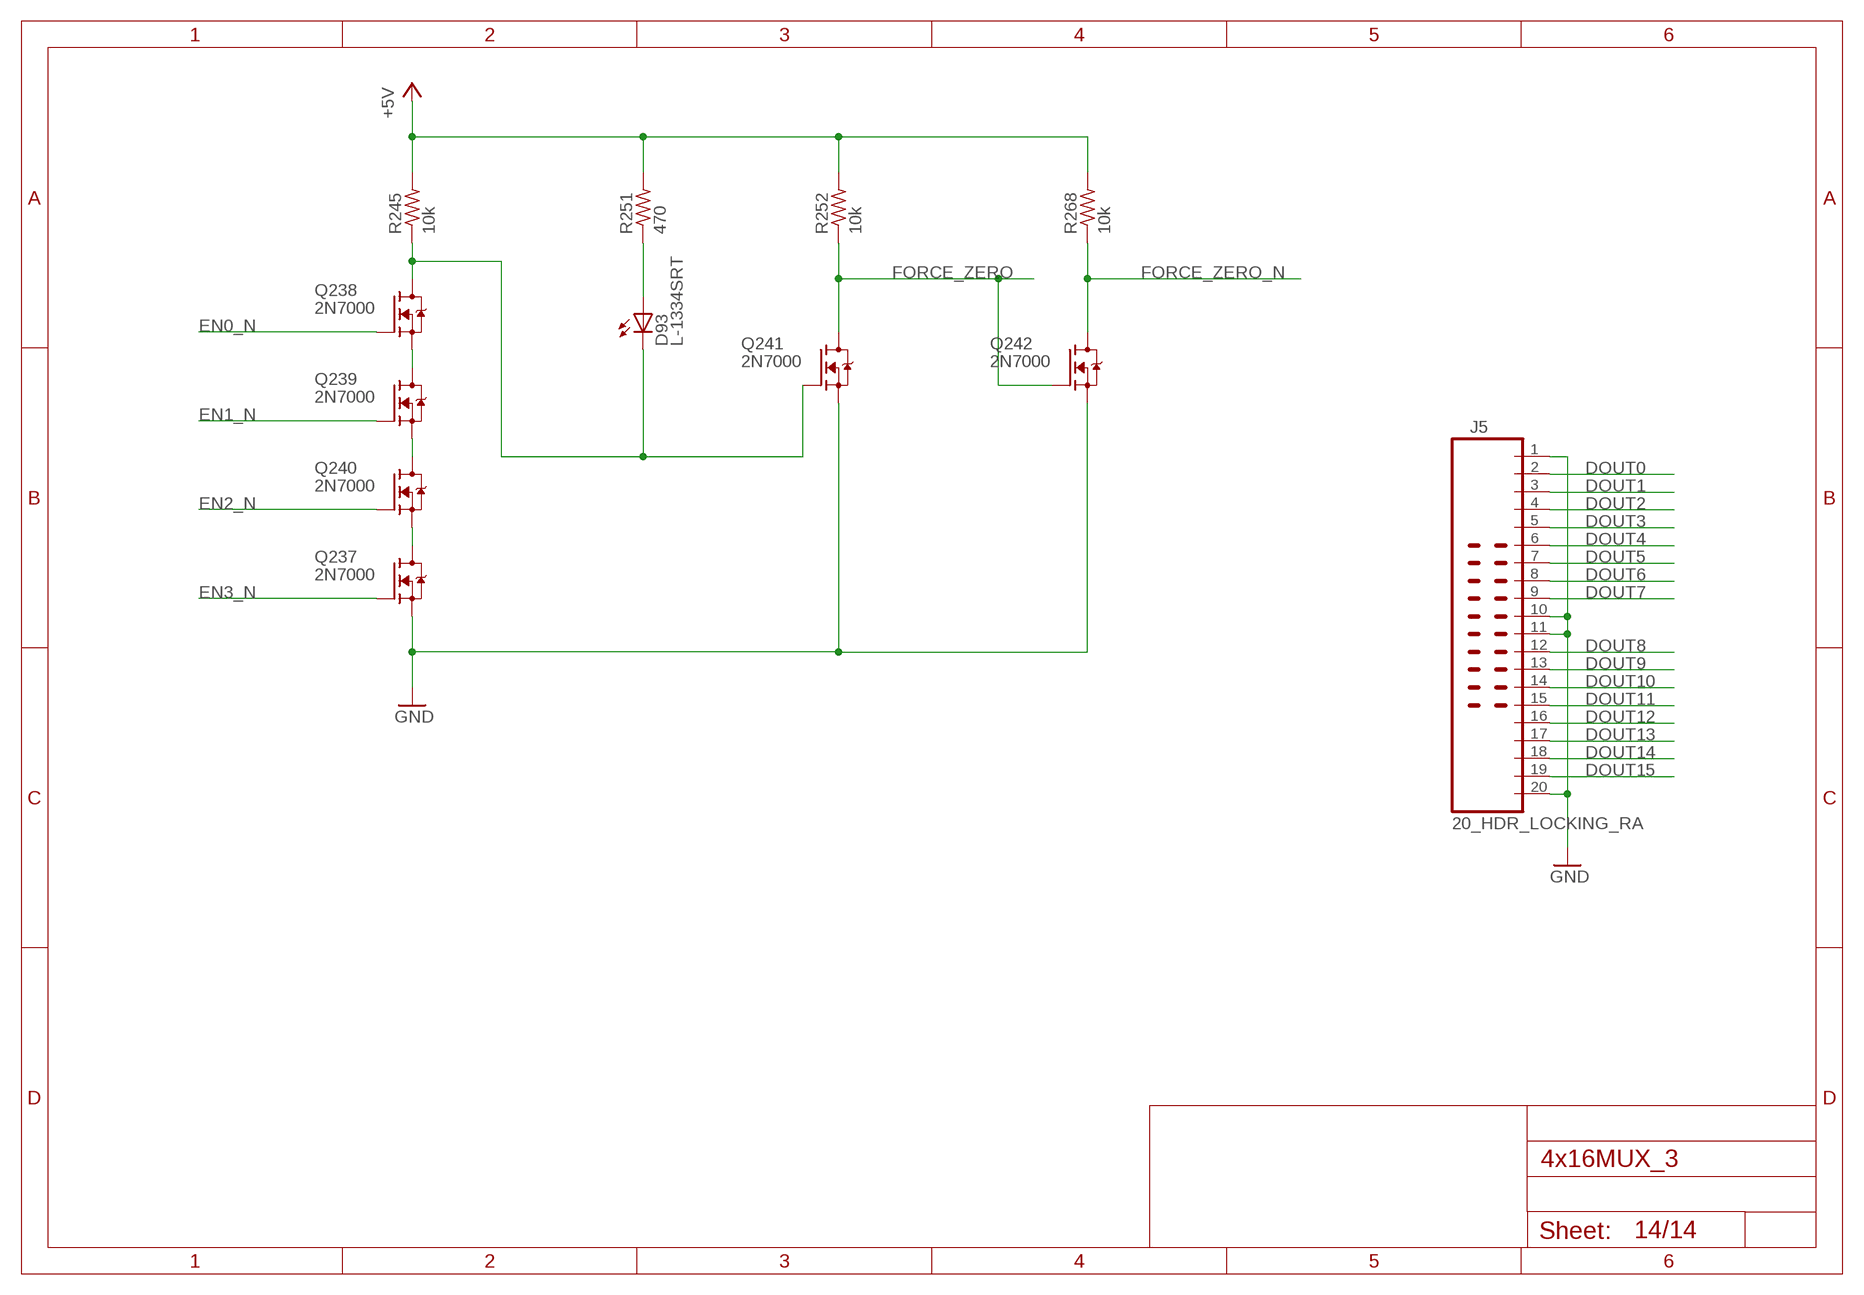
[diagram p13: schematic, sheet 14]

(export (version "E")
  (design (tool "Eeschema 10.0.6"))
  (components
    (comp (ref "D1")
      (value "L-1334SRT")
      (footprint "eagle-import:LED3MM")
      (libsource (lib "eagle-import") (part "L-1334SRT"))
    )
    (comp (ref "D2")
      (value "L-1334SRT")
      (footprint "eagle-import:LED3MM")
      (libsource (lib "eagle-import") (part "L-1334SRT"))
    )
    (comp (ref "D3")
      (value "L-1334SRT")
      (footprint "eagle-import:LED3MM")
      (libsource (lib "eagle-import") (part "L-1334SRT"))
    )
    (comp (ref "D4")
      (value "L-1334SRT")
      (footprint "eagle-import:LED3MM")
      (libsource (lib "eagle-import") (part "L-1334SRT"))
    )
    (comp (ref "D5")
      (value "L-1334SRT")
      (footprint "eagle-import:LED3MM")
      (libsource (lib "eagle-import") (part "L-1334SRT"))
    )
    (comp (ref "D6")
      (value "L-1334SRT")
      (footprint "eagle-import:LED3MM")
      (libsource (lib "eagle-import") (part "L-1334SRT"))
    )
    (comp (ref "D7")
      (value "L-1334SRT")
      (footprint "eagle-import:LED3MM")
      (libsource (lib "eagle-import") (part "L-1334SRT"))
    )
    (comp (ref "D8")
      (value "L-1334SRT")
      (footprint "eagle-import:LED3MM")
      (libsource (lib "eagle-import") (part "L-1334SRT"))
    )
    (comp (ref "D9")
      (value "L-1334SRT")
      (footprint "eagle-import:LED3MM")
      (libsource (lib "eagle-import") (part "L-1334SRT"))
    )
    (comp (ref "D10")
      (value "L-1334SRT")
      (footprint "eagle-import:LED3MM")
      (libsource (lib "eagle-import") (part "L-1334SRT"))
    )
    (comp (ref "Q1")
      (value "2N7000")
      (footprint "eagle-import:TO92-DGS")
      (libsource (lib "eagle-import") (part "2N7000"))
    )
    (comp (ref "Q2")
      (value "2N7000")
      (footprint "eagle-import:TO92-DGS")
      (libsource (lib "eagle-import") (part "2N7000"))
    )
    (comp (ref "Q3")
      (value "2N7000")
      (footprint "eagle-import:TO92-DGS")
      (libsource (lib "eagle-import") (part "2N7000"))
    )
    (comp (ref "Q4")
      (value "2N7000")
      (footprint "eagle-import:TO92-DGS")
      (libsource (lib "eagle-import") (part "2N7000"))
    )
    (comp (ref "Q5")
      (value "2N7000")
      (footprint "eagle-import:TO92-DGS")
      (libsource (lib "eagle-import") (part "2N7000"))
    )
    (comp (ref "Q6")
      (value "2N7000")
      (footprint "eagle-import:TO92-DGS")
      (libsource (lib "eagle-import") (part "2N7000"))
    )
    (comp (ref "Q7")
      (value "2N7000")
      (footprint "eagle-import:TO92-DGS")
      (libsource (lib "eagle-import") (part "2N7000"))
    )
    (comp (ref "Q8")
      (value "2N7000")
      (footprint "eagle-import:TO92-DGS")
      (libsource (lib "eagle-import") (part "2N7000"))
    )
    (comp (ref "Q9")
      (value "2N7000")
      (footprint "eagle-import:TO92-DGS")
      (libsource (lib "eagle-import") (part "2N7000"))
    )
    (comp (ref "Q10")
      (value "2N7000")
      (footprint "eagle-import:TO92-DGS")
      (libsource (lib "eagle-import") (part "2N7000"))
    )
    (comp (ref "Q11")
      (value "2N7000")
      (footprint "eagle-import:TO92-DGS")
      (libsource (lib "eagle-import") (part "2N7000"))
    )
    (comp (ref "Q12")
      (value "2N7000")
      (footprint "eagle-import:TO92-DGS")
      (libsource (lib "eagle-import") (part "2N7000"))
    )
    (comp (ref "Q13")
      (value "2N7000")
      (footprint "eagle-import:TO92-DGS")
      (libsource (lib "eagle-import") (part "2N7000"))
    )
    (comp (ref "Q14")
      (value "2N7000")
      (footprint "eagle-import:TO92-DGS")
      (libsource (lib "eagle-import") (part "2N7000"))
    )
    (comp (ref "Q15")
      (value "2N7000")
      (footprint "eagle-import:TO92-DGS")
      (libsource (lib "eagle-import") (part "2N7000"))
    )
    (comp (ref "Q16")
      (value "2N7000")
      (footprint "eagle-import:TO92-DGS")
      (libsource (lib "eagle-import") (part "2N7000"))
    )
    (comp (ref "Q17")
      (value "2N7000")
      (footprint "eagle-import:TO92-DGS")
      (libsource (lib "eagle-import") (part "2N7000"))
    )
    (comp (ref "Q18")
      (value "2N7000")
      (footprint "eagle-import:TO92-DGS")
      (libsource (lib "eagle-import") (part "2N7000"))
    )
    (comp (ref "Q19")
      (value "2N7000")
      (footprint "eagle-import:TO92-DGS")
      (libsource (lib "eagle-import") (part "2N7000"))
    )
    (comp (ref "Q20")
      (value "2N7000")
      (footprint "eagle-import:TO92-DGS")
      (libsource (lib "eagle-import") (part "2N7000"))
    )
    (comp (ref "R1")
      (value "10k")
      (footprint "eagle-import:R_P2INCH")
      (libsource (lib "eagle-import") (part "R_P2INCH"))
    )
    (comp (ref "R2")
      (value "470")
      (footprint "eagle-import:R_P2INCH")
      (libsource (lib "eagle-import") (part "R_P2INCH"))
    )
    (comp (ref "R3")
      (value "10k")
      (footprint "eagle-import:R_P2INCH")
      (libsource (lib "eagle-import") (part "R_P2INCH"))
    )
    (comp (ref "R4")
      (value "470")
      (footprint "eagle-import:R_P2INCH")
      (libsource (lib "eagle-import") (part "R_P2INCH"))
    )
    (comp (ref "R5")
      (value "10k")
      (footprint "eagle-import:R_P2INCH")
      (libsource (lib "eagle-import") (part "R_P2INCH"))
    )
    (comp (ref "R6")
      (value "470")
      (footprint "eagle-import:R_P2INCH")
      (libsource (lib "eagle-import") (part "R_P2INCH"))
    )
    (comp (ref "R7")
      (value "10k")
      (footprint "eagle-import:R_P2INCH")
      (libsource (lib "eagle-import") (part "R_P2INCH"))
    )
    (comp (ref "R8")
      (value "470")
      (footprint "eagle-import:R_P2INCH")
      (libsource (lib "eagle-import") (part "R_P2INCH"))
    )
    (comp (ref "R9")
      (value "10k")
      (footprint "eagle-import:R_P2INCH")
      (libsource (lib "eagle-import") (part "R_P2INCH"))
    )
    (comp (ref "R10")
      (value "470")
      (footprint "eagle-import:R_P2INCH")
      (libsource (lib "eagle-import") (part "R_P2INCH"))
    )
    (comp (ref "R11")
      (value "10k")
      (footprint "eagle-import:R_P2INCH")
      (libsource (lib "eagle-import") (part "R_P2INCH"))
    )
    (comp (ref "R12")
      (value "470")
      (footprint "eagle-import:R_P2INCH")
      (libsource (lib "eagle-import") (part "R_P2INCH"))
    )
    (comp (ref "R13")
      (value "10k")
      (footprint "eagle-import:R_P2INCH")
      (libsource (lib "eagle-import") (part "R_P2INCH"))
    )
    (comp (ref "R14")
      (value "470")
      (footprint "eagle-import:R_P2INCH")
      (libsource (lib "eagle-import") (part "R_P2INCH"))
    )
    (comp (ref "R15")
      (value "10k")
      (footprint "eagle-import:R_P2INCH")
      (libsource (lib "eagle-import") (part "R_P2INCH"))
    )
    (comp (ref "R16")
      (value "470")
      (footprint "eagle-import:R_P2INCH")
      (libsource (lib "eagle-import") (part "R_P2INCH"))
    )
    (comp (ref "R17")
      (value "10k")
      (footprint "eagle-import:R_P2INCH")
      (libsource (lib "eagle-import") (part "R_P2INCH"))
    )
    (comp (ref "R18")
      (value "470")
      (footprint "eagle-import:R_P2INCH")
      (libsource (lib "eagle-import") (part "R_P2INCH"))
    )
    (comp (ref "R19")
      (value "10k")
      (footprint "eagle-import:R_P2INCH")
      (libsource (lib "eagle-import") (part "R_P2INCH"))
    )
    (comp (ref "R20")
      (value "470")
      (footprint "eagle-import:R_P2INCH")
      (libsource (lib "eagle-import") (part "R_P2INCH"))
    )
    (comp (ref "R181")
      (value "10k")
      (footprint "eagle-import:R_P2INCH")
      (libsource (lib "eagle-import") (part "R_P2INCH"))
    )
    (comp (ref "R182")
      (value "10k")
      (footprint "eagle-import:R_P2INCH")
      (libsource (lib "eagle-import") (part "R_P2INCH"))
    )
    (comp (ref "R183")
      (value "10k")
      (footprint "eagle-import:R_P2INCH")
      (libsource (lib "eagle-import") (part "R_P2INCH"))
    )
    (comp (ref "R184")
      (value "10k")
      (footprint "eagle-import:R_P2INCH")
      (libsource (lib "eagle-import") (part "R_P2INCH"))
    )
    (comp (ref "R185")
      (value "10k")
      (footprint "eagle-import:R_P2INCH")
      (libsource (lib "eagle-import") (part "R_P2INCH"))
    )
    (comp (ref "R186")
      (value "10k")
      (footprint "eagle-import:R_P2INCH")
      (libsource (lib "eagle-import") (part "R_P2INCH"))
    )
    (comp (ref "R187")
      (value "10k")
      (footprint "eagle-import:R_P2INCH")
      (libsource (lib "eagle-import") (part "R_P2INCH"))
    )
    (comp (ref "R188")
      (value "10k")
      (footprint "eagle-import:R_P2INCH")
      (libsource (lib "eagle-import") (part "R_P2INCH"))
    )
    (comp (ref "R189")
      (value "10k")
      (footprint "eagle-import:R_P2INCH")
      (libsource (lib "eagle-import") (part "R_P2INCH"))
    )
    (comp (ref "R190")
      (value "10k")
      (footprint "eagle-import:R_P2INCH")
      (libsource (lib "eagle-import") (part "R_P2INCH"))
    )
    (comp (ref "D69")
      (value "L-1334SRT")
      (footprint "eagle-import:LED3MM")
      (libsource (lib "eagle-import") (part "L-1334SRT"))
    )
    (comp (ref "D70")
      (value "L-1334SRT")
      (footprint "eagle-import:LED3MM")
      (libsource (lib "eagle-import") (part "L-1334SRT"))
    )
    (comp (ref "D71")
      (value "L-1334SRT")
      (footprint "eagle-import:LED3MM")
      (libsource (lib "eagle-import") (part "L-1334SRT"))
    )
    (comp (ref "D72")
      (value "L-1334SRT")
      (footprint "eagle-import:LED3MM")
      (libsource (lib "eagle-import") (part "L-1334SRT"))
    )
    (comp (ref "Q141")
      (value "2N7000")
      (footprint "eagle-import:TO92-DGS")
      (libsource (lib "eagle-import") (part "2N7000"))
    )
    (comp (ref "Q142")
      (value "2N7000")
      (footprint "eagle-import:TO92-DGS")
      (libsource (lib "eagle-import") (part "2N7000"))
    )
    (comp (ref "Q143")
      (value "2N7000")
      (footprint "eagle-import:TO92-DGS")
      (libsource (lib "eagle-import") (part "2N7000"))
    )
    (comp (ref "Q144")
      (value "2N7000")
      (footprint "eagle-import:TO92-DGS")
      (libsource (lib "eagle-import") (part "2N7000"))
    )
    (comp (ref "Q145")
      (value "2N7000")
      (footprint "eagle-import:TO92-DGS")
      (libsource (lib "eagle-import") (part "2N7000"))
    )
    (comp (ref "Q146")
      (value "2N7000")
      (footprint "eagle-import:TO92-DGS")
      (libsource (lib "eagle-import") (part "2N7000"))
    )
    (comp (ref "Q147")
      (value "2N7000")
      (footprint "eagle-import:TO92-DGS")
      (libsource (lib "eagle-import") (part "2N7000"))
    )
    (comp (ref "Q148")
      (value "2N7000")
      (footprint "eagle-import:TO92-DGS")
      (libsource (lib "eagle-import") (part "2N7000"))
    )
    (comp (ref "Q149")
      (value "2N7000")
      (footprint "eagle-import:TO92-DGS")
      (libsource (lib "eagle-import") (part "2N7000"))
    )
    (comp (ref "Q150")
      (value "2N7000")
      (footprint "eagle-import:TO92-DGS")
      (libsource (lib "eagle-import") (part "2N7000"))
    )
    (comp (ref "Q151")
      (value "2N7000")
      (footprint "eagle-import:TO92-DGS")
      (libsource (lib "eagle-import") (part "2N7000"))
    )
    (comp (ref "Q152")
      (value "2N7000")
      (footprint "eagle-import:TO92-DGS")
      (libsource (lib "eagle-import") (part "2N7000"))
    )
    (comp (ref "Q153")
      (value "2N7000")
      (footprint "eagle-import:TO92-DGS")
      (libsource (lib "eagle-import") (part "2N7000"))
    )
    (comp (ref "Q154")
      (value "2N7000")
      (footprint "eagle-import:TO92-DGS")
      (libsource (lib "eagle-import") (part "2N7000"))
    )
    (comp (ref "Q155")
      (value "2N7000")
      (footprint "eagle-import:TO92-DGS")
      (libsource (lib "eagle-import") (part "2N7000"))
    )
    (comp (ref "Q156")
      (value "2N7000")
      (footprint "eagle-import:TO92-DGS")
      (libsource (lib "eagle-import") (part "2N7000"))
    )
    (comp (ref "Q157")
      (value "2N7000")
      (footprint "eagle-import:TO92-DGS")
      (libsource (lib "eagle-import") (part "2N7000"))
    )
    (comp (ref "Q158")
      (value "2N7000")
      (footprint "eagle-import:TO92-DGS")
      (libsource (lib "eagle-import") (part "2N7000"))
    )
    (comp (ref "Q159")
      (value "2N7000")
      (footprint "eagle-import:TO92-DGS")
      (libsource (lib "eagle-import") (part "2N7000"))
    )
    (comp (ref "Q160")
      (value "2N7000")
      (footprint "eagle-import:TO92-DGS")
      (libsource (lib "eagle-import") (part "2N7000"))
    )
    (comp (ref "Q221")
      (value "2N7000")
      (footprint "eagle-import:TO92-DGS")
      (libsource (lib "eagle-import") (part "2N7000"))
    )
    (comp (ref "Q222")
      (value "2N7000")
      (footprint "eagle-import:TO92-DGS")
      (libsource (lib "eagle-import") (part "2N7000"))
    )
    (comp (ref "Q223")
      (value "2N7000")
      (footprint "eagle-import:TO92-DGS")
      (libsource (lib "eagle-import") (part "2N7000"))
    )
    (comp (ref "Q224")
      (value "2N7000")
      (footprint "eagle-import:TO92-DGS")
      (libsource (lib "eagle-import") (part "2N7000"))
    )
    (comp (ref "R145")
      (value "10k")
      (footprint "eagle-import:R_P2INCH")
      (libsource (lib "eagle-import") (part "R_P2INCH"))
    )
    (comp (ref "R146")
      (value "470")
      (footprint "eagle-import:R_P2INCH")
      (libsource (lib "eagle-import") (part "R_P2INCH"))
    )
    (comp (ref "R147")
      (value "10k")
      (footprint "eagle-import:R_P2INCH")
      (libsource (lib "eagle-import") (part "R_P2INCH"))
    )
    (comp (ref "R148")
      (value "470")
      (footprint "eagle-import:R_P2INCH")
      (libsource (lib "eagle-import") (part "R_P2INCH"))
    )
    (comp (ref "R149")
      (value "10k")
      (footprint "eagle-import:R_P2INCH")
      (libsource (lib "eagle-import") (part "R_P2INCH"))
    )
    (comp (ref "R150")
      (value "470")
      (footprint "eagle-import:R_P2INCH")
      (libsource (lib "eagle-import") (part "R_P2INCH"))
    )
    (comp (ref "R151")
      (value "10k")
      (footprint "eagle-import:R_P2INCH")
      (libsource (lib "eagle-import") (part "R_P2INCH"))
    )
    (comp (ref "R152")
      (value "470")
      (footprint "eagle-import:R_P2INCH")
      (libsource (lib "eagle-import") (part "R_P2INCH"))
    )
    (comp (ref "R250")
      (value "10k")
      (footprint "eagle-import:R_P2INCH")
      (libsource (lib "eagle-import") (part "R_P2INCH"))
    )
    (comp (ref "R253")
      (value "10k")
      (footprint "eagle-import:R_P2INCH")
      (libsource (lib "eagle-import") (part "R_P2INCH"))
    )
    (comp (ref "R254")
      (value "10k")
      (footprint "eagle-import:R_P2INCH")
      (libsource (lib "eagle-import") (part "R_P2INCH"))
    )
    (comp (ref "R255")
      (value "10k")
      (footprint "eagle-import:R_P2INCH")
      (libsource (lib "eagle-import") (part "R_P2INCH"))
    )
    (comp (ref "D49")
      (value "L-1334SRT")
      (footprint "eagle-import:LED3MM")
      (libsource (lib "eagle-import") (part "L-1334SRT"))
    )
    (comp (ref "D50")
      (value "L-1334SRT")
      (footprint "eagle-import:LED3MM")
      (libsource (lib "eagle-import") (part "L-1334SRT"))
    )
    (comp (ref "D51")
      (value "L-1334SRT")
      (footprint "eagle-import:LED3MM")
      (libsource (lib "eagle-import") (part "L-1334SRT"))
    )
    (comp (ref "D52")
      (value "L-1334SRT")
      (footprint "eagle-import:LED3MM")
      (libsource (lib "eagle-import") (part "L-1334SRT"))
    )
    (comp (ref "D53")
      (value "L-1334SRT")
      (footprint "eagle-import:LED3MM")
      (libsource (lib "eagle-import") (part "L-1334SRT"))
    )
    (comp (ref "D54")
      (value "L-1334SRT")
      (footprint "eagle-import:LED3MM")
      (libsource (lib "eagle-import") (part "L-1334SRT"))
    )
    (comp (ref "D55")
      (value "L-1334SRT")
      (footprint "eagle-import:LED3MM")
      (libsource (lib "eagle-import") (part "L-1334SRT"))
    )
    (comp (ref "D56")
      (value "L-1334SRT")
      (footprint "eagle-import:LED3MM")
      (libsource (lib "eagle-import") (part "L-1334SRT"))
    )
    (comp (ref "D57")
      (value "L-1334SRT")
      (footprint "eagle-import:LED3MM")
      (libsource (lib "eagle-import") (part "L-1334SRT"))
    )
    (comp (ref "D58")
      (value "L-1334SRT")
      (footprint "eagle-import:LED3MM")
      (libsource (lib "eagle-import") (part "L-1334SRT"))
    )
    (comp (ref "Q97")
      (value "2N7000")
      (footprint "eagle-import:TO92-DGS")
      (libsource (lib "eagle-import") (part "2N7000"))
    )
    (comp (ref "Q98")
      (value "2N7000")
      (footprint "eagle-import:TO92-DGS")
      (libsource (lib "eagle-import") (part "2N7000"))
    )
    (comp (ref "Q99")
      (value "2N7000")
      (footprint "eagle-import:TO92-DGS")
      (libsource (lib "eagle-import") (part "2N7000"))
    )
    (comp (ref "Q100")
      (value "2N7000")
      (footprint "eagle-import:TO92-DGS")
      (libsource (lib "eagle-import") (part "2N7000"))
    )
    (comp (ref "Q101")
      (value "2N7000")
      (footprint "eagle-import:TO92-DGS")
      (libsource (lib "eagle-import") (part "2N7000"))
    )
    (comp (ref "Q102")
      (value "2N7000")
      (footprint "eagle-import:TO92-DGS")
      (libsource (lib "eagle-import") (part "2N7000"))
    )
    (comp (ref "Q103")
      (value "2N7000")
      (footprint "eagle-import:TO92-DGS")
      (libsource (lib "eagle-import") (part "2N7000"))
    )
    (comp (ref "Q104")
      (value "2N7000")
      (footprint "eagle-import:TO92-DGS")
      (libsource (lib "eagle-import") (part "2N7000"))
    )
    (comp (ref "Q105")
      (value "2N7000")
      (footprint "eagle-import:TO92-DGS")
      (libsource (lib "eagle-import") (part "2N7000"))
    )
    (comp (ref "Q106")
      (value "2N7000")
      (footprint "eagle-import:TO92-DGS")
      (libsource (lib "eagle-import") (part "2N7000"))
    )
    (comp (ref "Q107")
      (value "2N7000")
      (footprint "eagle-import:TO92-DGS")
      (libsource (lib "eagle-import") (part "2N7000"))
    )
    (comp (ref "Q108")
      (value "2N7000")
      (footprint "eagle-import:TO92-DGS")
      (libsource (lib "eagle-import") (part "2N7000"))
    )
    (comp (ref "Q109")
      (value "2N7000")
      (footprint "eagle-import:TO92-DGS")
      (libsource (lib "eagle-import") (part "2N7000"))
    )
    (comp (ref "Q110")
      (value "2N7000")
      (footprint "eagle-import:TO92-DGS")
      (libsource (lib "eagle-import") (part "2N7000"))
    )
    (comp (ref "Q111")
      (value "2N7000")
      (footprint "eagle-import:TO92-DGS")
      (libsource (lib "eagle-import") (part "2N7000"))
    )
    (comp (ref "Q112")
      (value "2N7000")
      (footprint "eagle-import:TO92-DGS")
      (libsource (lib "eagle-import") (part "2N7000"))
    )
    (comp (ref "Q113")
      (value "2N7000")
      (footprint "eagle-import:TO92-DGS")
      (libsource (lib "eagle-import") (part "2N7000"))
    )
    (comp (ref "Q114")
      (value "2N7000")
      (footprint "eagle-import:TO92-DGS")
      (libsource (lib "eagle-import") (part "2N7000"))
    )
    (comp (ref "Q115")
      (value "2N7000")
      (footprint "eagle-import:TO92-DGS")
      (libsource (lib "eagle-import") (part "2N7000"))
    )
    (comp (ref "Q116")
      (value "2N7000")
      (footprint "eagle-import:TO92-DGS")
      (libsource (lib "eagle-import") (part "2N7000"))
    )
    (comp (ref "R97")
      (value "10k")
      (footprint "eagle-import:R_P2INCH")
      (libsource (lib "eagle-import") (part "R_P2INCH"))
    )
    (comp (ref "R98")
      (value "470")
      (footprint "eagle-import:R_P2INCH")
      (libsource (lib "eagle-import") (part "R_P2INCH"))
    )
    (comp (ref "R99")
      (value "10k")
      (footprint "eagle-import:R_P2INCH")
      (libsource (lib "eagle-import") (part "R_P2INCH"))
    )
    (comp (ref "R100")
      (value "470")
      (footprint "eagle-import:R_P2INCH")
      (libsource (lib "eagle-import") (part "R_P2INCH"))
    )
    (comp (ref "R101")
      (value "10k")
      (footprint "eagle-import:R_P2INCH")
      (libsource (lib "eagle-import") (part "R_P2INCH"))
    )
    (comp (ref "R102")
      (value "470")
      (footprint "eagle-import:R_P2INCH")
      (libsource (lib "eagle-import") (part "R_P2INCH"))
    )
    (comp (ref "R103")
      (value "10k")
      (footprint "eagle-import:R_P2INCH")
      (libsource (lib "eagle-import") (part "R_P2INCH"))
    )
    (comp (ref "R104")
      (value "470")
      (footprint "eagle-import:R_P2INCH")
      (libsource (lib "eagle-import") (part "R_P2INCH"))
    )
    (comp (ref "R105")
      (value "10k")
      (footprint "eagle-import:R_P2INCH")
      (libsource (lib "eagle-import") (part "R_P2INCH"))
    )
    (comp (ref "R106")
      (value "470")
      (footprint "eagle-import:R_P2INCH")
      (libsource (lib "eagle-import") (part "R_P2INCH"))
    )
    (comp (ref "R107")
      (value "10k")
      (footprint "eagle-import:R_P2INCH")
      (libsource (lib "eagle-import") (part "R_P2INCH"))
    )
    (comp (ref "R108")
      (value "470")
      (footprint "eagle-import:R_P2INCH")
      (libsource (lib "eagle-import") (part "R_P2INCH"))
    )
    (comp (ref "R109")
      (value "10k")
      (footprint "eagle-import:R_P2INCH")
      (libsource (lib "eagle-import") (part "R_P2INCH"))
    )
    (comp (ref "R110")
      (value "470")
      (footprint "eagle-import:R_P2INCH")
      (libsource (lib "eagle-import") (part "R_P2INCH"))
    )
    (comp (ref "R111")
      (value "10k")
      (footprint "eagle-import:R_P2INCH")
      (libsource (lib "eagle-import") (part "R_P2INCH"))
    )
    (comp (ref "R112")
      (value "470")
      (footprint "eagle-import:R_P2INCH")
      (libsource (lib "eagle-import") (part "R_P2INCH"))
    )
    (comp (ref "R113")
      (value "10k")
      (footprint "eagle-import:R_P2INCH")
      (libsource (lib "eagle-import") (part "R_P2INCH"))
    )
    (comp (ref "R114")
      (value "470")
      (footprint "eagle-import:R_P2INCH")
      (libsource (lib "eagle-import") (part "R_P2INCH"))
    )
    (comp (ref "R115")
      (value "10k")
      (footprint "eagle-import:R_P2INCH")
      (libsource (lib "eagle-import") (part "R_P2INCH"))
    )
    (comp (ref "R116")
      (value "470")
      (footprint "eagle-import:R_P2INCH")
      (libsource (lib "eagle-import") (part "R_P2INCH"))
    )
    (comp (ref "R229")
      (value "10k")
      (footprint "eagle-import:R_P2INCH")
      (libsource (lib "eagle-import") (part "R_P2INCH"))
    )
    (comp (ref "R230")
      (value "10k")
      (footprint "eagle-import:R_P2INCH")
      (libsource (lib "eagle-import") (part "R_P2INCH"))
    )
    (comp (ref "R231")
      (value "10k")
      (footprint "eagle-import:R_P2INCH")
      (libsource (lib "eagle-import") (part "R_P2INCH"))
    )
    (comp (ref "R232")
      (value "10k")
      (footprint "eagle-import:R_P2INCH")
      (libsource (lib "eagle-import") (part "R_P2INCH"))
    )
    (comp (ref "R233")
      (value "10k")
      (footprint "eagle-import:R_P2INCH")
      (libsource (lib "eagle-import") (part "R_P2INCH"))
    )
    (comp (ref "R234")
      (value "10k")
      (footprint "eagle-import:R_P2INCH")
      (libsource (lib "eagle-import") (part "R_P2INCH"))
    )
    (comp (ref "R235")
      (value "10k")
      (footprint "eagle-import:R_P2INCH")
      (libsource (lib "eagle-import") (part "R_P2INCH"))
    )
    (comp (ref "R236")
      (value "10k")
      (footprint "eagle-import:R_P2INCH")
      (libsource (lib "eagle-import") (part "R_P2INCH"))
    )
    (comp (ref "R237")
      (value "10k")
      (footprint "eagle-import:R_P2INCH")
      (libsource (lib "eagle-import") (part "R_P2INCH"))
    )
    (comp (ref "R238")
      (value "10k")
      (footprint "eagle-import:R_P2INCH")
      (libsource (lib "eagle-import") (part "R_P2INCH"))
    )
    (comp (ref "C1")
      (value "100n")
      (footprint "eagle-import:CAP_P2INCH")
      (libsource (lib "eagle-import") (part "C_P2INCH"))
    )
    (comp (ref "C2")
      (value "100n")
      (footprint "eagle-import:CAP_P2INCH")
      (libsource (lib "eagle-import") (part "C_P2INCH"))
    )
    (comp (ref "C3")
      (value "100n")
      (footprint "eagle-import:CAP_P2INCH")
      (libsource (lib "eagle-import") (part "C_P2INCH"))
    )
    (comp (ref "C4")
      (value "100n")
      (footprint "eagle-import:CAP_P2INCH")
      (libsource (lib "eagle-import") (part "C_P2INCH"))
    )
    (comp (ref "C5")
      (value "100n")
      (footprint "eagle-import:CAP_P2INCH")
      (libsource (lib "eagle-import") (part "C_P2INCH"))
    )
    (comp (ref "C6")
      (value "100n")
      (footprint "eagle-import:CAP_P2INCH")
      (libsource (lib "eagle-import") (part "C_P2INCH"))
    )
    (comp (ref "C7")
      (value "100u")
      (footprint "eagle-import:POLARISED_CAP_2P5_6P3MM")
      (libsource (lib "eagle-import") (part "POLARISED_CAP_2P5_6P3MM"))
    )
    (comp (ref "C8")
      (value "100n")
      (footprint "eagle-import:CAP_P2INCH")
      (libsource (lib "eagle-import") (part "C_P2INCH"))
    )
    (comp (ref "H1")
      (value "3M_MOUNT_HOLE")
      (footprint "eagle-import:3M_HOLE")
      (libsource (lib "eagle-import") (part "3M_MOUNT_HOLE"))
    )
    (comp (ref "H2")
      (value "3M_MOUNT_HOLE")
      (footprint "eagle-import:3M_HOLE")
      (libsource (lib "eagle-import") (part "3M_MOUNT_HOLE"))
    )
    (comp (ref "H3")
      (value "3M_MOUNT_HOLE")
      (footprint "eagle-import:3M_HOLE")
      (libsource (lib "eagle-import") (part "3M_MOUNT_HOLE"))
    )
    (comp (ref "H4")
      (value "3M_MOUNT_HOLE")
      (footprint "eagle-import:3M_HOLE")
      (libsource (lib "eagle-import") (part "3M_MOUNT_HOLE"))
    )
    (comp (ref "H5")
      (value "3M_MOUNT_HOLE")
      (footprint "eagle-import:3M_HOLE")
      (libsource (lib "eagle-import") (part "3M_MOUNT_HOLE"))
    )
    (comp (ref "H6")
      (value "3M_MOUNT_HOLE")
      (footprint "eagle-import:3M_HOLE")
      (libsource (lib "eagle-import") (part "3M_MOUNT_HOLE"))
    )
    (comp (ref "H7")
      (value "3M_MOUNT_HOLE")
      (footprint "eagle-import:3M_HOLE")
      (libsource (lib "eagle-import") (part "3M_MOUNT_HOLE"))
    )
    (comp (ref "H8")
      (value "3M_MOUNT_HOLE")
      (footprint "eagle-import:3M_HOLE")
      (libsource (lib "eagle-import") (part "3M_MOUNT_HOLE"))
    )
    (comp (ref "TP5")
      (value "TEST_LOOP")
      (footprint "eagle-import:TEST_LOOP")
      (libsource (lib "eagle-import") (part "TEST_LOOP"))
    )
    (comp (ref "TP6")
      (value "TEST_LOOP")
      (footprint "eagle-import:TEST_LOOP")
      (libsource (lib "eagle-import") (part "TEST_LOOP"))
    )
    (comp (ref "D73")
      (value "L-1334SRT")
      (footprint "eagle-import:LED3MM")
      (libsource (lib "eagle-import") (part "L-1334SRT"))
    )
    (comp (ref "D74")
      (value "L-1334SRT")
      (footprint "eagle-import:LED3MM")
      (libsource (lib "eagle-import") (part "L-1334SRT"))
    )
    (comp (ref "D75")
      (value "L-1334SRT")
      (footprint "eagle-import:LED3MM")
      (libsource (lib "eagle-import") (part "L-1334SRT"))
    )
    (comp (ref "D76")
      (value "L-1334SRT")
      (footprint "eagle-import:LED3MM")
      (libsource (lib "eagle-import") (part "L-1334SRT"))
    )
    (comp (ref "Q161")
      (value "2N7000")
      (footprint "eagle-import:TO92-DGS")
      (libsource (lib "eagle-import") (part "2N7000"))
    )
    (comp (ref "Q162")
      (value "2N7000")
      (footprint "eagle-import:TO92-DGS")
      (libsource (lib "eagle-import") (part "2N7000"))
    )
    (comp (ref "Q163")
      (value "2N7000")
      (footprint "eagle-import:TO92-DGS")
      (libsource (lib "eagle-import") (part "2N7000"))
    )
    (comp (ref "Q164")
      (value "2N7000")
      (footprint "eagle-import:TO92-DGS")
      (libsource (lib "eagle-import") (part "2N7000"))
    )
    (comp (ref "Q165")
      (value "2N7000")
      (footprint "eagle-import:TO92-DGS")
      (libsource (lib "eagle-import") (part "2N7000"))
    )
    (comp (ref "Q166")
      (value "2N7000")
      (footprint "eagle-import:TO92-DGS")
      (libsource (lib "eagle-import") (part "2N7000"))
    )
    (comp (ref "Q167")
      (value "2N7000")
      (footprint "eagle-import:TO92-DGS")
      (libsource (lib "eagle-import") (part "2N7000"))
    )
    (comp (ref "Q168")
      (value "2N7000")
      (footprint "eagle-import:TO92-DGS")
      (libsource (lib "eagle-import") (part "2N7000"))
    )
    (comp (ref "Q169")
      (value "2N7000")
      (footprint "eagle-import:TO92-DGS")
      (libsource (lib "eagle-import") (part "2N7000"))
    )
    (comp (ref "Q170")
      (value "2N7000")
      (footprint "eagle-import:TO92-DGS")
      (libsource (lib "eagle-import") (part "2N7000"))
    )
    (comp (ref "Q171")
      (value "2N7000")
      (footprint "eagle-import:TO92-DGS")
      (libsource (lib "eagle-import") (part "2N7000"))
    )
    (comp (ref "Q172")
      (value "2N7000")
      (footprint "eagle-import:TO92-DGS")
      (libsource (lib "eagle-import") (part "2N7000"))
    )
    (comp (ref "Q173")
      (value "2N7000")
      (footprint "eagle-import:TO92-DGS")
      (libsource (lib "eagle-import") (part "2N7000"))
    )
    (comp (ref "Q174")
      (value "2N7000")
      (footprint "eagle-import:TO92-DGS")
      (libsource (lib "eagle-import") (part "2N7000"))
    )
    (comp (ref "Q175")
      (value "2N7000")
      (footprint "eagle-import:TO92-DGS")
      (libsource (lib "eagle-import") (part "2N7000"))
    )
    (comp (ref "Q176")
      (value "2N7000")
      (footprint "eagle-import:TO92-DGS")
      (libsource (lib "eagle-import") (part "2N7000"))
    )
    (comp (ref "Q177")
      (value "2N7000")
      (footprint "eagle-import:TO92-DGS")
      (libsource (lib "eagle-import") (part "2N7000"))
    )
    (comp (ref "Q178")
      (value "2N7000")
      (footprint "eagle-import:TO92-DGS")
      (libsource (lib "eagle-import") (part "2N7000"))
    )
    (comp (ref "Q179")
      (value "2N7000")
      (footprint "eagle-import:TO92-DGS")
      (libsource (lib "eagle-import") (part "2N7000"))
    )
    (comp (ref "Q180")
      (value "2N7000")
      (footprint "eagle-import:TO92-DGS")
      (libsource (lib "eagle-import") (part "2N7000"))
    )
    (comp (ref "Q225")
      (value "2N7000")
      (footprint "eagle-import:TO92-DGS")
      (libsource (lib "eagle-import") (part "2N7000"))
    )
    (comp (ref "Q226")
      (value "2N7000")
      (footprint "eagle-import:TO92-DGS")
      (libsource (lib "eagle-import") (part "2N7000"))
    )
    (comp (ref "Q227")
      (value "2N7000")
      (footprint "eagle-import:TO92-DGS")
      (libsource (lib "eagle-import") (part "2N7000"))
    )
    (comp (ref "Q228")
      (value "2N7000")
      (footprint "eagle-import:TO92-DGS")
      (libsource (lib "eagle-import") (part "2N7000"))
    )
    (comp (ref "R153")
      (value "10k")
      (footprint "eagle-import:R_P2INCH")
      (libsource (lib "eagle-import") (part "R_P2INCH"))
    )
    (comp (ref "R154")
      (value "470")
      (footprint "eagle-import:R_P2INCH")
      (libsource (lib "eagle-import") (part "R_P2INCH"))
    )
    (comp (ref "R155")
      (value "10k")
      (footprint "eagle-import:R_P2INCH")
      (libsource (lib "eagle-import") (part "R_P2INCH"))
    )
    (comp (ref "R156")
      (value "470")
      (footprint "eagle-import:R_P2INCH")
      (libsource (lib "eagle-import") (part "R_P2INCH"))
    )
    (comp (ref "R157")
      (value "10k")
      (footprint "eagle-import:R_P2INCH")
      (libsource (lib "eagle-import") (part "R_P2INCH"))
    )
    (comp (ref "R158")
      (value "470")
      (footprint "eagle-import:R_P2INCH")
      (libsource (lib "eagle-import") (part "R_P2INCH"))
    )
    (comp (ref "R159")
      (value "10k")
      (footprint "eagle-import:R_P2INCH")
      (libsource (lib "eagle-import") (part "R_P2INCH"))
    )
    (comp (ref "R160")
      (value "470")
      (footprint "eagle-import:R_P2INCH")
      (libsource (lib "eagle-import") (part "R_P2INCH"))
    )
    (comp (ref "R256")
      (value "10k")
      (footprint "eagle-import:R_P2INCH")
      (libsource (lib "eagle-import") (part "R_P2INCH"))
    )
    (comp (ref "R257")
      (value "10k")
      (footprint "eagle-import:R_P2INCH")
      (libsource (lib "eagle-import") (part "R_P2INCH"))
    )
    (comp (ref "R258")
      (value "10k")
      (footprint "eagle-import:R_P2INCH")
      (libsource (lib "eagle-import") (part "R_P2INCH"))
    )
    (comp (ref "R259")
      (value "10k")
      (footprint "eagle-import:R_P2INCH")
      (libsource (lib "eagle-import") (part "R_P2INCH"))
    )
    (comp (ref "D77")
      (value "L-1334SRT")
      (footprint "eagle-import:LED3MM")
      (libsource (lib "eagle-import") (part "L-1334SRT"))
    )
    (comp (ref "D78")
      (value "L-1334SRT")
      (footprint "eagle-import:LED3MM")
      (libsource (lib "eagle-import") (part "L-1334SRT"))
    )
    (comp (ref "D79")
      (value "L-1334SRT")
      (footprint "eagle-import:LED3MM")
      (libsource (lib "eagle-import") (part "L-1334SRT"))
    )
    (comp (ref "D80")
      (value "L-1334SRT")
      (footprint "eagle-import:LED3MM")
      (libsource (lib "eagle-import") (part "L-1334SRT"))
    )
    (comp (ref "Q181")
      (value "2N7000")
      (footprint "eagle-import:TO92-DGS")
      (libsource (lib "eagle-import") (part "2N7000"))
    )
    (comp (ref "Q182")
      (value "2N7000")
      (footprint "eagle-import:TO92-DGS")
      (libsource (lib "eagle-import") (part "2N7000"))
    )
    (comp (ref "Q183")
      (value "2N7000")
      (footprint "eagle-import:TO92-DGS")
      (libsource (lib "eagle-import") (part "2N7000"))
    )
    (comp (ref "Q184")
      (value "2N7000")
      (footprint "eagle-import:TO92-DGS")
      (libsource (lib "eagle-import") (part "2N7000"))
    )
    (comp (ref "Q185")
      (value "2N7000")
      (footprint "eagle-import:TO92-DGS")
      (libsource (lib "eagle-import") (part "2N7000"))
    )
    (comp (ref "Q186")
      (value "2N7000")
      (footprint "eagle-import:TO92-DGS")
      (libsource (lib "eagle-import") (part "2N7000"))
    )
    (comp (ref "Q187")
      (value "2N7000")
      (footprint "eagle-import:TO92-DGS")
      (libsource (lib "eagle-import") (part "2N7000"))
    )
    (comp (ref "Q188")
      (value "2N7000")
      (footprint "eagle-import:TO92-DGS")
      (libsource (lib "eagle-import") (part "2N7000"))
    )
    (comp (ref "Q189")
      (value "2N7000")
      (footprint "eagle-import:TO92-DGS")
      (libsource (lib "eagle-import") (part "2N7000"))
    )
    (comp (ref "Q190")
      (value "2N7000")
      (footprint "eagle-import:TO92-DGS")
      (libsource (lib "eagle-import") (part "2N7000"))
    )
    (comp (ref "Q191")
      (value "2N7000")
      (footprint "eagle-import:TO92-DGS")
      (libsource (lib "eagle-import") (part "2N7000"))
    )
    (comp (ref "Q192")
      (value "2N7000")
      (footprint "eagle-import:TO92-DGS")
      (libsource (lib "eagle-import") (part "2N7000"))
    )
    (comp (ref "Q193")
      (value "2N7000")
      (footprint "eagle-import:TO92-DGS")
      (libsource (lib "eagle-import") (part "2N7000"))
    )
    (comp (ref "Q194")
      (value "2N7000")
      (footprint "eagle-import:TO92-DGS")
      (libsource (lib "eagle-import") (part "2N7000"))
    )
    (comp (ref "Q195")
      (value "2N7000")
      (footprint "eagle-import:TO92-DGS")
      (libsource (lib "eagle-import") (part "2N7000"))
    )
    (comp (ref "Q196")
      (value "2N7000")
      (footprint "eagle-import:TO92-DGS")
      (libsource (lib "eagle-import") (part "2N7000"))
    )
    (comp (ref "Q197")
      (value "2N7000")
      (footprint "eagle-import:TO92-DGS")
      (libsource (lib "eagle-import") (part "2N7000"))
    )
    (comp (ref "Q198")
      (value "2N7000")
      (footprint "eagle-import:TO92-DGS")
      (libsource (lib "eagle-import") (part "2N7000"))
    )
    (comp (ref "Q199")
      (value "2N7000")
      (footprint "eagle-import:TO92-DGS")
      (libsource (lib "eagle-import") (part "2N7000"))
    )
    (comp (ref "Q200")
      (value "2N7000")
      (footprint "eagle-import:TO92-DGS")
      (libsource (lib "eagle-import") (part "2N7000"))
    )
    (comp (ref "Q229")
      (value "2N7000")
      (footprint "eagle-import:TO92-DGS")
      (libsource (lib "eagle-import") (part "2N7000"))
    )
    (comp (ref "Q230")
      (value "2N7000")
      (footprint "eagle-import:TO92-DGS")
      (libsource (lib "eagle-import") (part "2N7000"))
    )
    (comp (ref "Q231")
      (value "2N7000")
      (footprint "eagle-import:TO92-DGS")
      (libsource (lib "eagle-import") (part "2N7000"))
    )
    (comp (ref "Q232")
      (value "2N7000")
      (footprint "eagle-import:TO92-DGS")
      (libsource (lib "eagle-import") (part "2N7000"))
    )
    (comp (ref "R161")
      (value "10k")
      (footprint "eagle-import:R_P2INCH")
      (libsource (lib "eagle-import") (part "R_P2INCH"))
    )
    (comp (ref "R162")
      (value "470")
      (footprint "eagle-import:R_P2INCH")
      (libsource (lib "eagle-import") (part "R_P2INCH"))
    )
    (comp (ref "R163")
      (value "10k")
      (footprint "eagle-import:R_P2INCH")
      (libsource (lib "eagle-import") (part "R_P2INCH"))
    )
    (comp (ref "R164")
      (value "470")
      (footprint "eagle-import:R_P2INCH")
      (libsource (lib "eagle-import") (part "R_P2INCH"))
    )
    (comp (ref "R165")
      (value "10k")
      (footprint "eagle-import:R_P2INCH")
      (libsource (lib "eagle-import") (part "R_P2INCH"))
    )
    (comp (ref "R166")
      (value "470")
      (footprint "eagle-import:R_P2INCH")
      (libsource (lib "eagle-import") (part "R_P2INCH"))
    )
    (comp (ref "R167")
      (value "10k")
      (footprint "eagle-import:R_P2INCH")
      (libsource (lib "eagle-import") (part "R_P2INCH"))
    )
    (comp (ref "R168")
      (value "470")
      (footprint "eagle-import:R_P2INCH")
      (libsource (lib "eagle-import") (part "R_P2INCH"))
    )
    (comp (ref "R260")
      (value "10k")
      (footprint "eagle-import:R_P2INCH")
      (libsource (lib "eagle-import") (part "R_P2INCH"))
    )
    (comp (ref "R261")
      (value "10k")
      (footprint "eagle-import:R_P2INCH")
      (libsource (lib "eagle-import") (part "R_P2INCH"))
    )
    (comp (ref "R262")
      (value "10k")
      (footprint "eagle-import:R_P2INCH")
      (libsource (lib "eagle-import") (part "R_P2INCH"))
    )
    (comp (ref "R263")
      (value "10k")
      (footprint "eagle-import:R_P2INCH")
      (libsource (lib "eagle-import") (part "R_P2INCH"))
    )
    (comp (ref "D43")
      (value "L-1334SRT")
      (footprint "eagle-import:LED3MM")
      (libsource (lib "eagle-import") (part "L-1334SRT"))
    )
    (comp (ref "D44")
      (value "L-1334SRT")
      (footprint "eagle-import:LED3MM")
      (libsource (lib "eagle-import") (part "L-1334SRT"))
    )
    (comp (ref "D45")
      (value "L-1334SRT")
      (footprint "eagle-import:LED3MM")
      (libsource (lib "eagle-import") (part "L-1334SRT"))
    )
    (comp (ref "D46")
      (value "L-1334SRT")
      (footprint "eagle-import:LED3MM")
      (libsource (lib "eagle-import") (part "L-1334SRT"))
    )
    (comp (ref "D47")
      (value "L-1334SRT")
      (footprint "eagle-import:LED3MM")
      (libsource (lib "eagle-import") (part "L-1334SRT"))
    )
    (comp (ref "D48")
      (value "L-1334SRT")
      (footprint "eagle-import:LED3MM")
      (libsource (lib "eagle-import") (part "L-1334SRT"))
    )
    (comp (ref "D67")
      (value "L-1334SRT")
      (footprint "eagle-import:LED3MM")
      (libsource (lib "eagle-import") (part "L-1334SRT"))
    )
    (comp (ref "D87")
      (value "L-1334SRT")
      (footprint "eagle-import:LED3MM")
      (libsource (lib "eagle-import") (part "L-1334SRT"))
    )
    (comp (ref "D91")
      (value "L-1334SRT")
      (footprint "eagle-import:LED3MM")
      (libsource (lib "eagle-import") (part "L-1334SRT"))
    )
    (comp (ref "J3")
      (value "20_HDR_LOCKING_RA")
      (footprint "eagle-import:20_HDR_LOCKING_RA")
      (libsource (lib "eagle-import") (part "20_HDR_LOCKING_RA"))
    )
    (comp (ref "Q85")
      (value "2N7000")
      (footprint "eagle-import:TO92-DGS")
      (libsource (lib "eagle-import") (part "2N7000"))
    )
    (comp (ref "Q86")
      (value "2N7000")
      (footprint "eagle-import:TO92-DGS")
      (libsource (lib "eagle-import") (part "2N7000"))
    )
    (comp (ref "Q87")
      (value "2N7000")
      (footprint "eagle-import:TO92-DGS")
      (libsource (lib "eagle-import") (part "2N7000"))
    )
    (comp (ref "Q88")
      (value "2N7000")
      (footprint "eagle-import:TO92-DGS")
      (libsource (lib "eagle-import") (part "2N7000"))
    )
    (comp (ref "Q89")
      (value "2N7000")
      (footprint "eagle-import:TO92-DGS")
      (libsource (lib "eagle-import") (part "2N7000"))
    )
    (comp (ref "Q90")
      (value "2N7000")
      (footprint "eagle-import:TO92-DGS")
      (libsource (lib "eagle-import") (part "2N7000"))
    )
    (comp (ref "Q91")
      (value "2N7000")
      (footprint "eagle-import:TO92-DGS")
      (libsource (lib "eagle-import") (part "2N7000"))
    )
    (comp (ref "Q92")
      (value "2N7000")
      (footprint "eagle-import:TO92-DGS")
      (libsource (lib "eagle-import") (part "2N7000"))
    )
    (comp (ref "Q93")
      (value "2N7000")
      (footprint "eagle-import:TO92-DGS")
      (libsource (lib "eagle-import") (part "2N7000"))
    )
    (comp (ref "Q94")
      (value "2N7000")
      (footprint "eagle-import:TO92-DGS")
      (libsource (lib "eagle-import") (part "2N7000"))
    )
    (comp (ref "Q95")
      (value "2N7000")
      (footprint "eagle-import:TO92-DGS")
      (libsource (lib "eagle-import") (part "2N7000"))
    )
    (comp (ref "Q96")
      (value "2N7000")
      (footprint "eagle-import:TO92-DGS")
      (libsource (lib "eagle-import") (part "2N7000"))
    )
    (comp (ref "Q135")
      (value "2N7000")
      (footprint "eagle-import:TO92-DGS")
      (libsource (lib "eagle-import") (part "2N7000"))
    )
    (comp (ref "Q136")
      (value "2N7000")
      (footprint "eagle-import:TO92-DGS")
      (libsource (lib "eagle-import") (part "2N7000"))
    )
    (comp (ref "Q137")
      (value "2N7000")
      (footprint "eagle-import:TO92-DGS")
      (libsource (lib "eagle-import") (part "2N7000"))
    )
    (comp (ref "R85")
      (value "10k")
      (footprint "eagle-import:R_P2INCH")
      (libsource (lib "eagle-import") (part "R_P2INCH"))
    )
    (comp (ref "R86")
      (value "470")
      (footprint "eagle-import:R_P2INCH")
      (libsource (lib "eagle-import") (part "R_P2INCH"))
    )
    (comp (ref "R87")
      (value "10k")
      (footprint "eagle-import:R_P2INCH")
      (libsource (lib "eagle-import") (part "R_P2INCH"))
    )
    (comp (ref "R88")
      (value "470")
      (footprint "eagle-import:R_P2INCH")
      (libsource (lib "eagle-import") (part "R_P2INCH"))
    )
    (comp (ref "R89")
      (value "10k")
      (footprint "eagle-import:R_P2INCH")
      (libsource (lib "eagle-import") (part "R_P2INCH"))
    )
    (comp (ref "R90")
      (value "470")
      (footprint "eagle-import:R_P2INCH")
      (libsource (lib "eagle-import") (part "R_P2INCH"))
    )
    (comp (ref "R91")
      (value "10k")
      (footprint "eagle-import:R_P2INCH")
      (libsource (lib "eagle-import") (part "R_P2INCH"))
    )
    (comp (ref "R92")
      (value "470")
      (footprint "eagle-import:R_P2INCH")
      (libsource (lib "eagle-import") (part "R_P2INCH"))
    )
    (comp (ref "R93")
      (value "10k")
      (footprint "eagle-import:R_P2INCH")
      (libsource (lib "eagle-import") (part "R_P2INCH"))
    )
    (comp (ref "R94")
      (value "470")
      (footprint "eagle-import:R_P2INCH")
      (libsource (lib "eagle-import") (part "R_P2INCH"))
    )
    (comp (ref "R95")
      (value "10k")
      (footprint "eagle-import:R_P2INCH")
      (libsource (lib "eagle-import") (part "R_P2INCH"))
    )
    (comp (ref "R96")
      (value "470")
      (footprint "eagle-import:R_P2INCH")
      (libsource (lib "eagle-import") (part "R_P2INCH"))
    )
    (comp (ref "R137")
      (value "10k")
      (footprint "eagle-import:R_P2INCH")
      (libsource (lib "eagle-import") (part "R_P2INCH"))
    )
    (comp (ref "R138")
      (value "470")
      (footprint "eagle-import:R_P2INCH")
      (libsource (lib "eagle-import") (part "R_P2INCH"))
    )
    (comp (ref "R139")
      (value "10k")
      (footprint "eagle-import:R_P2INCH")
      (libsource (lib "eagle-import") (part "R_P2INCH"))
    )
    (comp (ref "R140")
      (value "10k")
      (footprint "eagle-import:R_P2INCH")
      (libsource (lib "eagle-import") (part "R_P2INCH"))
    )
    (comp (ref "R179")
      (value "470")
      (footprint "eagle-import:R_P2INCH")
      (libsource (lib "eagle-import") (part "R_P2INCH"))
    )
    (comp (ref "R223")
      (value "10k")
      (footprint "eagle-import:R_P2INCH")
      (libsource (lib "eagle-import") (part "R_P2INCH"))
    )
    (comp (ref "R224")
      (value "10k")
      (footprint "eagle-import:R_P2INCH")
      (libsource (lib "eagle-import") (part "R_P2INCH"))
    )
    (comp (ref "R225")
      (value "10k")
      (footprint "eagle-import:R_P2INCH")
      (libsource (lib "eagle-import") (part "R_P2INCH"))
    )
    (comp (ref "R226")
      (value "10k")
      (footprint "eagle-import:R_P2INCH")
      (libsource (lib "eagle-import") (part "R_P2INCH"))
    )
    (comp (ref "R227")
      (value "10k")
      (footprint "eagle-import:R_P2INCH")
      (libsource (lib "eagle-import") (part "R_P2INCH"))
    )
    (comp (ref "R228")
      (value "10k")
      (footprint "eagle-import:R_P2INCH")
      (libsource (lib "eagle-import") (part "R_P2INCH"))
    )
    (comp (ref "R248")
      (value "470")
      (footprint "eagle-import:R_P2INCH")
      (libsource (lib "eagle-import") (part "R_P2INCH"))
    )
    (comp (ref "TP3")
      (value "TEST_LOOP")
      (footprint "eagle-import:TEST_LOOP")
      (libsource (lib "eagle-import") (part "TEST_LOOP"))
    )
    (comp (ref "D27")
      (value "L-1334SRT")
      (footprint "eagle-import:LED3MM")
      (libsource (lib "eagle-import") (part "L-1334SRT"))
    )
    (comp (ref "D28")
      (value "L-1334SRT")
      (footprint "eagle-import:LED3MM")
      (libsource (lib "eagle-import") (part "L-1334SRT"))
    )
    (comp (ref "D29")
      (value "L-1334SRT")
      (footprint "eagle-import:LED3MM")
      (libsource (lib "eagle-import") (part "L-1334SRT"))
    )
    (comp (ref "D30")
      (value "L-1334SRT")
      (footprint "eagle-import:LED3MM")
      (libsource (lib "eagle-import") (part "L-1334SRT"))
    )
    (comp (ref "D31")
      (value "L-1334SRT")
      (footprint "eagle-import:LED3MM")
      (libsource (lib "eagle-import") (part "L-1334SRT"))
    )
    (comp (ref "D32")
      (value "L-1334SRT")
      (footprint "eagle-import:LED3MM")
      (libsource (lib "eagle-import") (part "L-1334SRT"))
    )
    (comp (ref "D66")
      (value "L-1334SRT")
      (footprint "eagle-import:LED3MM")
      (libsource (lib "eagle-import") (part "L-1334SRT"))
    )
    (comp (ref "D86")
      (value "L-1334SRT")
      (footprint "eagle-import:LED3MM")
      (libsource (lib "eagle-import") (part "L-1334SRT"))
    )
    (comp (ref "D90")
      (value "L-1334SRT")
      (footprint "eagle-import:LED3MM")
      (libsource (lib "eagle-import") (part "L-1334SRT"))
    )
    (comp (ref "J2")
      (value "20_HDR_LOCKING_RA")
      (footprint "eagle-import:20_HDR_LOCKING_RA")
      (libsource (lib "eagle-import") (part "20_HDR_LOCKING_RA"))
    )
    (comp (ref "Q53")
      (value "2N7000")
      (footprint "eagle-import:TO92-DGS")
      (libsource (lib "eagle-import") (part "2N7000"))
    )
    (comp (ref "Q54")
      (value "2N7000")
      (footprint "eagle-import:TO92-DGS")
      (libsource (lib "eagle-import") (part "2N7000"))
    )
    (comp (ref "Q55")
      (value "2N7000")
      (footprint "eagle-import:TO92-DGS")
      (libsource (lib "eagle-import") (part "2N7000"))
    )
    (comp (ref "Q56")
      (value "2N7000")
      (footprint "eagle-import:TO92-DGS")
      (libsource (lib "eagle-import") (part "2N7000"))
    )
    (comp (ref "Q57")
      (value "2N7000")
      (footprint "eagle-import:TO92-DGS")
      (libsource (lib "eagle-import") (part "2N7000"))
    )
    (comp (ref "Q58")
      (value "2N7000")
      (footprint "eagle-import:TO92-DGS")
      (libsource (lib "eagle-import") (part "2N7000"))
    )
    (comp (ref "Q59")
      (value "2N7000")
      (footprint "eagle-import:TO92-DGS")
      (libsource (lib "eagle-import") (part "2N7000"))
    )
    (comp (ref "Q60")
      (value "2N7000")
      (footprint "eagle-import:TO92-DGS")
      (libsource (lib "eagle-import") (part "2N7000"))
    )
    (comp (ref "Q61")
      (value "2N7000")
      (footprint "eagle-import:TO92-DGS")
      (libsource (lib "eagle-import") (part "2N7000"))
    )
    (comp (ref "Q62")
      (value "2N7000")
      (footprint "eagle-import:TO92-DGS")
      (libsource (lib "eagle-import") (part "2N7000"))
    )
    (comp (ref "Q63")
      (value "2N7000")
      (footprint "eagle-import:TO92-DGS")
      (libsource (lib "eagle-import") (part "2N7000"))
    )
    (comp (ref "Q64")
      (value "2N7000")
      (footprint "eagle-import:TO92-DGS")
      (libsource (lib "eagle-import") (part "2N7000"))
    )
    (comp (ref "Q132")
      (value "2N7000")
      (footprint "eagle-import:TO92-DGS")
      (libsource (lib "eagle-import") (part "2N7000"))
    )
    (comp (ref "Q133")
      (value "2N7000")
      (footprint "eagle-import:TO92-DGS")
      (libsource (lib "eagle-import") (part "2N7000"))
    )
    (comp (ref "Q134")
      (value "2N7000")
      (footprint "eagle-import:TO92-DGS")
      (libsource (lib "eagle-import") (part "2N7000"))
    )
    (comp (ref "R53")
      (value "10k")
      (footprint "eagle-import:R_P2INCH")
      (libsource (lib "eagle-import") (part "R_P2INCH"))
    )
    (comp (ref "R54")
      (value "470")
      (footprint "eagle-import:R_P2INCH")
      (libsource (lib "eagle-import") (part "R_P2INCH"))
    )
    (comp (ref "R55")
      (value "10k")
      (footprint "eagle-import:R_P2INCH")
      (libsource (lib "eagle-import") (part "R_P2INCH"))
    )
    (comp (ref "R56")
      (value "470")
      (footprint "eagle-import:R_P2INCH")
      (libsource (lib "eagle-import") (part "R_P2INCH"))
    )
    (comp (ref "R57")
      (value "10k")
      (footprint "eagle-import:R_P2INCH")
      (libsource (lib "eagle-import") (part "R_P2INCH"))
    )
    (comp (ref "R58")
      (value "470")
      (footprint "eagle-import:R_P2INCH")
      (libsource (lib "eagle-import") (part "R_P2INCH"))
    )
    (comp (ref "R59")
      (value "10k")
      (footprint "eagle-import:R_P2INCH")
      (libsource (lib "eagle-import") (part "R_P2INCH"))
    )
    (comp (ref "R60")
      (value "470")
      (footprint "eagle-import:R_P2INCH")
      (libsource (lib "eagle-import") (part "R_P2INCH"))
    )
    (comp (ref "R61")
      (value "10k")
      (footprint "eagle-import:R_P2INCH")
      (libsource (lib "eagle-import") (part "R_P2INCH"))
    )
    (comp (ref "R62")
      (value "470")
      (footprint "eagle-import:R_P2INCH")
      (libsource (lib "eagle-import") (part "R_P2INCH"))
    )
    (comp (ref "R63")
      (value "10k")
      (footprint "eagle-import:R_P2INCH")
      (libsource (lib "eagle-import") (part "R_P2INCH"))
    )
    (comp (ref "R64")
      (value "470")
      (footprint "eagle-import:R_P2INCH")
      (libsource (lib "eagle-import") (part "R_P2INCH"))
    )
    (comp (ref "R133")
      (value "10k")
      (footprint "eagle-import:R_P2INCH")
      (libsource (lib "eagle-import") (part "R_P2INCH"))
    )
    (comp (ref "R134")
      (value "470")
      (footprint "eagle-import:R_P2INCH")
      (libsource (lib "eagle-import") (part "R_P2INCH"))
    )
    (comp (ref "R135")
      (value "10k")
      (footprint "eagle-import:R_P2INCH")
      (libsource (lib "eagle-import") (part "R_P2INCH"))
    )
    (comp (ref "R136")
      (value "10k")
      (footprint "eagle-import:R_P2INCH")
      (libsource (lib "eagle-import") (part "R_P2INCH"))
    )
    (comp (ref "R178")
      (value "470")
      (footprint "eagle-import:R_P2INCH")
      (libsource (lib "eagle-import") (part "R_P2INCH"))
    )
    (comp (ref "R207")
      (value "10k")
      (footprint "eagle-import:R_P2INCH")
      (libsource (lib "eagle-import") (part "R_P2INCH"))
    )
    (comp (ref "R208")
      (value "10k")
      (footprint "eagle-import:R_P2INCH")
      (libsource (lib "eagle-import") (part "R_P2INCH"))
    )
    (comp (ref "R209")
      (value "10k")
      (footprint "eagle-import:R_P2INCH")
      (libsource (lib "eagle-import") (part "R_P2INCH"))
    )
    (comp (ref "R210")
      (value "10k")
      (footprint "eagle-import:R_P2INCH")
      (libsource (lib "eagle-import") (part "R_P2INCH"))
    )
    (comp (ref "R211")
      (value "10k")
      (footprint "eagle-import:R_P2INCH")
      (libsource (lib "eagle-import") (part "R_P2INCH"))
    )
    (comp (ref "R212")
      (value "10k")
      (footprint "eagle-import:R_P2INCH")
      (libsource (lib "eagle-import") (part "R_P2INCH"))
    )
    (comp (ref "R247")
      (value "470")
      (footprint "eagle-import:R_P2INCH")
      (libsource (lib "eagle-import") (part "R_P2INCH"))
    )
    (comp (ref "TP2")
      (value "TEST_LOOP")
      (footprint "eagle-import:TEST_LOOP")
      (libsource (lib "eagle-import") (part "TEST_LOOP"))
    )
    (comp (ref "D11")
      (value "L-1334SRT")
      (footprint "eagle-import:LED3MM")
      (libsource (lib "eagle-import") (part "L-1334SRT"))
    )
    (comp (ref "D12")
      (value "L-1334SRT")
      (footprint "eagle-import:LED3MM")
      (libsource (lib "eagle-import") (part "L-1334SRT"))
    )
    (comp (ref "D13")
      (value "L-1334SRT")
      (footprint "eagle-import:LED3MM")
      (libsource (lib "eagle-import") (part "L-1334SRT"))
    )
    (comp (ref "D14")
      (value "L-1334SRT")
      (footprint "eagle-import:LED3MM")
      (libsource (lib "eagle-import") (part "L-1334SRT"))
    )
    (comp (ref "D15")
      (value "L-1334SRT")
      (footprint "eagle-import:LED3MM")
      (libsource (lib "eagle-import") (part "L-1334SRT"))
    )
    (comp (ref "D16")
      (value "L-1334SRT")
      (footprint "eagle-import:LED3MM")
      (libsource (lib "eagle-import") (part "L-1334SRT"))
    )
    (comp (ref "D65")
      (value "L-1334SRT")
      (footprint "eagle-import:LED3MM")
      (libsource (lib "eagle-import") (part "L-1334SRT"))
    )
    (comp (ref "D85")
      (value "L-1334SRT")
      (footprint "eagle-import:LED3MM")
      (libsource (lib "eagle-import") (part "L-1334SRT"))
    )
    (comp (ref "D89")
      (value "L-1334SRT")
      (footprint "eagle-import:LED3MM")
      (libsource (lib "eagle-import") (part "L-1334SRT"))
    )
    (comp (ref "J1")
      (value "20_HDR_LOCKING_RA")
      (footprint "eagle-import:20_HDR_LOCKING_RA")
      (libsource (lib "eagle-import") (part "20_HDR_LOCKING_RA"))
    )
    (comp (ref "Q21")
      (value "2N7000")
      (footprint "eagle-import:TO92-DGS")
      (libsource (lib "eagle-import") (part "2N7000"))
    )
    (comp (ref "Q22")
      (value "2N7000")
      (footprint "eagle-import:TO92-DGS")
      (libsource (lib "eagle-import") (part "2N7000"))
    )
    (comp (ref "Q23")
      (value "2N7000")
      (footprint "eagle-import:TO92-DGS")
      (libsource (lib "eagle-import") (part "2N7000"))
    )
    (comp (ref "Q24")
      (value "2N7000")
      (footprint "eagle-import:TO92-DGS")
      (libsource (lib "eagle-import") (part "2N7000"))
    )
    (comp (ref "Q25")
      (value "2N7000")
      (footprint "eagle-import:TO92-DGS")
      (libsource (lib "eagle-import") (part "2N7000"))
    )
    (comp (ref "Q26")
      (value "2N7000")
      (footprint "eagle-import:TO92-DGS")
      (libsource (lib "eagle-import") (part "2N7000"))
    )
    (comp (ref "Q27")
      (value "2N7000")
      (footprint "eagle-import:TO92-DGS")
      (libsource (lib "eagle-import") (part "2N7000"))
    )
    (comp (ref "Q28")
      (value "2N7000")
      (footprint "eagle-import:TO92-DGS")
      (libsource (lib "eagle-import") (part "2N7000"))
    )
    (comp (ref "Q29")
      (value "2N7000")
      (footprint "eagle-import:TO92-DGS")
      (libsource (lib "eagle-import") (part "2N7000"))
    )
    (comp (ref "Q30")
      (value "2N7000")
      (footprint "eagle-import:TO92-DGS")
      (libsource (lib "eagle-import") (part "2N7000"))
    )
    (comp (ref "Q31")
      (value "2N7000")
      (footprint "eagle-import:TO92-DGS")
      (libsource (lib "eagle-import") (part "2N7000"))
    )
    (comp (ref "Q32")
      (value "2N7000")
      (footprint "eagle-import:TO92-DGS")
      (libsource (lib "eagle-import") (part "2N7000"))
    )
    (comp (ref "Q129")
      (value "2N7000")
      (footprint "eagle-import:TO92-DGS")
      (libsource (lib "eagle-import") (part "2N7000"))
    )
    (comp (ref "Q130")
      (value "2N7000")
      (footprint "eagle-import:TO92-DGS")
      (libsource (lib "eagle-import") (part "2N7000"))
    )
    (comp (ref "Q131")
      (value "2N7000")
      (footprint "eagle-import:TO92-DGS")
      (libsource (lib "eagle-import") (part "2N7000"))
    )
    (comp (ref "R21")
      (value "10k")
      (footprint "eagle-import:R_P2INCH")
      (libsource (lib "eagle-import") (part "R_P2INCH"))
    )
    (comp (ref "R22")
      (value "470")
      (footprint "eagle-import:R_P2INCH")
      (libsource (lib "eagle-import") (part "R_P2INCH"))
    )
    (comp (ref "R23")
      (value "10k")
      (footprint "eagle-import:R_P2INCH")
      (libsource (lib "eagle-import") (part "R_P2INCH"))
    )
    (comp (ref "R24")
      (value "470")
      (footprint "eagle-import:R_P2INCH")
      (libsource (lib "eagle-import") (part "R_P2INCH"))
    )
    (comp (ref "R25")
      (value "10k")
      (footprint "eagle-import:R_P2INCH")
      (libsource (lib "eagle-import") (part "R_P2INCH"))
    )
    (comp (ref "R26")
      (value "470")
      (footprint "eagle-import:R_P2INCH")
      (libsource (lib "eagle-import") (part "R_P2INCH"))
    )
    (comp (ref "R27")
      (value "10k")
      (footprint "eagle-import:R_P2INCH")
      (libsource (lib "eagle-import") (part "R_P2INCH"))
    )
    (comp (ref "R28")
      (value "470")
      (footprint "eagle-import:R_P2INCH")
      (libsource (lib "eagle-import") (part "R_P2INCH"))
    )
    (comp (ref "R29")
      (value "10k")
      (footprint "eagle-import:R_P2INCH")
      (libsource (lib "eagle-import") (part "R_P2INCH"))
    )
    (comp (ref "R30")
      (value "470")
      (footprint "eagle-import:R_P2INCH")
      (libsource (lib "eagle-import") (part "R_P2INCH"))
    )
    (comp (ref "R31")
      (value "10k")
      (footprint "eagle-import:R_P2INCH")
      (libsource (lib "eagle-import") (part "R_P2INCH"))
    )
    (comp (ref "R32")
      (value "470")
      (footprint "eagle-import:R_P2INCH")
      (libsource (lib "eagle-import") (part "R_P2INCH"))
    )
    (comp (ref "R129")
      (value "10k")
      (footprint "eagle-import:R_P2INCH")
      (libsource (lib "eagle-import") (part "R_P2INCH"))
    )
    (comp (ref "R130")
      (value "470")
      (footprint "eagle-import:R_P2INCH")
      (libsource (lib "eagle-import") (part "R_P2INCH"))
    )
    (comp (ref "R131")
      (value "10k")
      (footprint "eagle-import:R_P2INCH")
      (libsource (lib "eagle-import") (part "R_P2INCH"))
    )
    (comp (ref "R132")
      (value "10k")
      (footprint "eagle-import:R_P2INCH")
      (libsource (lib "eagle-import") (part "R_P2INCH"))
    )
    (comp (ref "R177")
      (value "470")
      (footprint "eagle-import:R_P2INCH")
      (libsource (lib "eagle-import") (part "R_P2INCH"))
    )
    (comp (ref "R191")
      (value "10k")
      (footprint "eagle-import:R_P2INCH")
      (libsource (lib "eagle-import") (part "R_P2INCH"))
    )
    (comp (ref "R192")
      (value "10k")
      (footprint "eagle-import:R_P2INCH")
      (libsource (lib "eagle-import") (part "R_P2INCH"))
    )
    (comp (ref "R193")
      (value "10k")
      (footprint "eagle-import:R_P2INCH")
      (libsource (lib "eagle-import") (part "R_P2INCH"))
    )
    (comp (ref "R194")
      (value "10k")
      (footprint "eagle-import:R_P2INCH")
      (libsource (lib "eagle-import") (part "R_P2INCH"))
    )
    (comp (ref "R195")
      (value "10k")
      (footprint "eagle-import:R_P2INCH")
      (libsource (lib "eagle-import") (part "R_P2INCH"))
    )
    (comp (ref "R196")
      (value "10k")
      (footprint "eagle-import:R_P2INCH")
      (libsource (lib "eagle-import") (part "R_P2INCH"))
    )
    (comp (ref "R246")
      (value "470")
      (footprint "eagle-import:R_P2INCH")
      (libsource (lib "eagle-import") (part "R_P2INCH"))
    )
    (comp (ref "TP1")
      (value "TEST_LOOP")
      (footprint "eagle-import:TEST_LOOP")
      (libsource (lib "eagle-import") (part "TEST_LOOP"))
    )
    (comp (ref "D17")
      (value "L-1334SRT")
      (footprint "eagle-import:LED3MM")
      (libsource (lib "eagle-import") (part "L-1334SRT"))
    )
    (comp (ref "D18")
      (value "L-1334SRT")
      (footprint "eagle-import:LED3MM")
      (libsource (lib "eagle-import") (part "L-1334SRT"))
    )
    (comp (ref "D19")
      (value "L-1334SRT")
      (footprint "eagle-import:LED3MM")
      (libsource (lib "eagle-import") (part "L-1334SRT"))
    )
    (comp (ref "D20")
      (value "L-1334SRT")
      (footprint "eagle-import:LED3MM")
      (libsource (lib "eagle-import") (part "L-1334SRT"))
    )
    (comp (ref "D21")
      (value "L-1334SRT")
      (footprint "eagle-import:LED3MM")
      (libsource (lib "eagle-import") (part "L-1334SRT"))
    )
    (comp (ref "D22")
      (value "L-1334SRT")
      (footprint "eagle-import:LED3MM")
      (libsource (lib "eagle-import") (part "L-1334SRT"))
    )
    (comp (ref "D23")
      (value "L-1334SRT")
      (footprint "eagle-import:LED3MM")
      (libsource (lib "eagle-import") (part "L-1334SRT"))
    )
    (comp (ref "D24")
      (value "L-1334SRT")
      (footprint "eagle-import:LED3MM")
      (libsource (lib "eagle-import") (part "L-1334SRT"))
    )
    (comp (ref "D25")
      (value "L-1334SRT")
      (footprint "eagle-import:LED3MM")
      (libsource (lib "eagle-import") (part "L-1334SRT"))
    )
    (comp (ref "D26")
      (value "L-1334SRT")
      (footprint "eagle-import:LED3MM")
      (libsource (lib "eagle-import") (part "L-1334SRT"))
    )
    (comp (ref "Q33")
      (value "2N7000")
      (footprint "eagle-import:TO92-DGS")
      (libsource (lib "eagle-import") (part "2N7000"))
    )
    (comp (ref "Q34")
      (value "2N7000")
      (footprint "eagle-import:TO92-DGS")
      (libsource (lib "eagle-import") (part "2N7000"))
    )
    (comp (ref "Q35")
      (value "2N7000")
      (footprint "eagle-import:TO92-DGS")
      (libsource (lib "eagle-import") (part "2N7000"))
    )
    (comp (ref "Q36")
      (value "2N7000")
      (footprint "eagle-import:TO92-DGS")
      (libsource (lib "eagle-import") (part "2N7000"))
    )
    (comp (ref "Q37")
      (value "2N7000")
      (footprint "eagle-import:TO92-DGS")
      (libsource (lib "eagle-import") (part "2N7000"))
    )
    (comp (ref "Q38")
      (value "2N7000")
      (footprint "eagle-import:TO92-DGS")
      (libsource (lib "eagle-import") (part "2N7000"))
    )
    (comp (ref "Q39")
      (value "2N7000")
      (footprint "eagle-import:TO92-DGS")
      (libsource (lib "eagle-import") (part "2N7000"))
    )
    (comp (ref "Q40")
      (value "2N7000")
      (footprint "eagle-import:TO92-DGS")
      (libsource (lib "eagle-import") (part "2N7000"))
    )
    (comp (ref "Q41")
      (value "2N7000")
      (footprint "eagle-import:TO92-DGS")
      (libsource (lib "eagle-import") (part "2N7000"))
    )
    (comp (ref "Q42")
      (value "2N7000")
      (footprint "eagle-import:TO92-DGS")
      (libsource (lib "eagle-import") (part "2N7000"))
    )
    (comp (ref "Q43")
      (value "2N7000")
      (footprint "eagle-import:TO92-DGS")
      (libsource (lib "eagle-import") (part "2N7000"))
    )
    (comp (ref "Q44")
      (value "2N7000")
      (footprint "eagle-import:TO92-DGS")
      (libsource (lib "eagle-import") (part "2N7000"))
    )
    (comp (ref "Q45")
      (value "2N7000")
      (footprint "eagle-import:TO92-DGS")
      (libsource (lib "eagle-import") (part "2N7000"))
    )
    (comp (ref "Q46")
      (value "2N7000")
      (footprint "eagle-import:TO92-DGS")
      (libsource (lib "eagle-import") (part "2N7000"))
    )
    (comp (ref "Q47")
      (value "2N7000")
      (footprint "eagle-import:TO92-DGS")
      (libsource (lib "eagle-import") (part "2N7000"))
    )
    (comp (ref "Q48")
      (value "2N7000")
      (footprint "eagle-import:TO92-DGS")
      (libsource (lib "eagle-import") (part "2N7000"))
    )
    (comp (ref "Q49")
      (value "2N7000")
      (footprint "eagle-import:TO92-DGS")
      (libsource (lib "eagle-import") (part "2N7000"))
    )
    (comp (ref "Q50")
      (value "2N7000")
      (footprint "eagle-import:TO92-DGS")
      (libsource (lib "eagle-import") (part "2N7000"))
    )
    (comp (ref "Q51")
      (value "2N7000")
      (footprint "eagle-import:TO92-DGS")
      (libsource (lib "eagle-import") (part "2N7000"))
    )
    (comp (ref "Q52")
      (value "2N7000")
      (footprint "eagle-import:TO92-DGS")
      (libsource (lib "eagle-import") (part "2N7000"))
    )
    (comp (ref "R33")
      (value "10k")
      (footprint "eagle-import:R_P2INCH")
      (libsource (lib "eagle-import") (part "R_P2INCH"))
    )
    (comp (ref "R34")
      (value "470")
      (footprint "eagle-import:R_P2INCH")
      (libsource (lib "eagle-import") (part "R_P2INCH"))
    )
    (comp (ref "R35")
      (value "10k")
      (footprint "eagle-import:R_P2INCH")
      (libsource (lib "eagle-import") (part "R_P2INCH"))
    )
    (comp (ref "R36")
      (value "470")
      (footprint "eagle-import:R_P2INCH")
      (libsource (lib "eagle-import") (part "R_P2INCH"))
    )
    (comp (ref "R37")
      (value "10k")
      (footprint "eagle-import:R_P2INCH")
      (libsource (lib "eagle-import") (part "R_P2INCH"))
    )
    (comp (ref "R38")
      (value "470")
      (footprint "eagle-import:R_P2INCH")
      (libsource (lib "eagle-import") (part "R_P2INCH"))
    )
    (comp (ref "R39")
      (value "10k")
      (footprint "eagle-import:R_P2INCH")
      (libsource (lib "eagle-import") (part "R_P2INCH"))
    )
    (comp (ref "R40")
      (value "470")
      (footprint "eagle-import:R_P2INCH")
      (libsource (lib "eagle-import") (part "R_P2INCH"))
    )
    (comp (ref "R41")
      (value "10k")
      (footprint "eagle-import:R_P2INCH")
      (libsource (lib "eagle-import") (part "R_P2INCH"))
    )
    (comp (ref "R42")
      (value "470")
      (footprint "eagle-import:R_P2INCH")
      (libsource (lib "eagle-import") (part "R_P2INCH"))
    )
    (comp (ref "R43")
      (value "10k")
      (footprint "eagle-import:R_P2INCH")
      (libsource (lib "eagle-import") (part "R_P2INCH"))
    )
    (comp (ref "R44")
      (value "470")
      (footprint "eagle-import:R_P2INCH")
      (libsource (lib "eagle-import") (part "R_P2INCH"))
    )
    (comp (ref "R45")
      (value "10k")
      (footprint "eagle-import:R_P2INCH")
      (libsource (lib "eagle-import") (part "R_P2INCH"))
    )
    (comp (ref "R46")
      (value "470")
      (footprint "eagle-import:R_P2INCH")
      (libsource (lib "eagle-import") (part "R_P2INCH"))
    )
    (comp (ref "R47")
      (value "10k")
      (footprint "eagle-import:R_P2INCH")
      (libsource (lib "eagle-import") (part "R_P2INCH"))
    )
    (comp (ref "R48")
      (value "470")
      (footprint "eagle-import:R_P2INCH")
      (libsource (lib "eagle-import") (part "R_P2INCH"))
    )
    (comp (ref "R49")
      (value "10k")
      (footprint "eagle-import:R_P2INCH")
      (libsource (lib "eagle-import") (part "R_P2INCH"))
    )
    (comp (ref "R50")
      (value "470")
      (footprint "eagle-import:R_P2INCH")
      (libsource (lib "eagle-import") (part "R_P2INCH"))
    )
    (comp (ref "R51")
      (value "10k")
      (footprint "eagle-import:R_P2INCH")
      (libsource (lib "eagle-import") (part "R_P2INCH"))
    )
    (comp (ref "R52")
      (value "470")
      (footprint "eagle-import:R_P2INCH")
      (libsource (lib "eagle-import") (part "R_P2INCH"))
    )
    (comp (ref "R197")
      (value "10k")
      (footprint "eagle-import:R_P2INCH")
      (libsource (lib "eagle-import") (part "R_P2INCH"))
    )
    (comp (ref "R198")
      (value "10k")
      (footprint "eagle-import:R_P2INCH")
      (libsource (lib "eagle-import") (part "R_P2INCH"))
    )
    (comp (ref "R199")
      (value "10k")
      (footprint "eagle-import:R_P2INCH")
      (libsource (lib "eagle-import") (part "R_P2INCH"))
    )
    (comp (ref "R200")
      (value "10k")
      (footprint "eagle-import:R_P2INCH")
      (libsource (lib "eagle-import") (part "R_P2INCH"))
    )
    (comp (ref "R201")
      (value "10k")
      (footprint "eagle-import:R_P2INCH")
      (libsource (lib "eagle-import") (part "R_P2INCH"))
    )
    (comp (ref "R202")
      (value "10k")
      (footprint "eagle-import:R_P2INCH")
      (libsource (lib "eagle-import") (part "R_P2INCH"))
    )
    (comp (ref "R203")
      (value "10k")
      (footprint "eagle-import:R_P2INCH")
      (libsource (lib "eagle-import") (part "R_P2INCH"))
    )
    (comp (ref "R204")
      (value "10k")
      (footprint "eagle-import:R_P2INCH")
      (libsource (lib "eagle-import") (part "R_P2INCH"))
    )
    (comp (ref "R205")
      (value "10k")
      (footprint "eagle-import:R_P2INCH")
      (libsource (lib "eagle-import") (part "R_P2INCH"))
    )
    (comp (ref "R206")
      (value "10k")
      (footprint "eagle-import:R_P2INCH")
      (libsource (lib "eagle-import") (part "R_P2INCH"))
    )
    (comp (ref "D59")
      (value "L-1334SRT")
      (footprint "eagle-import:LED3MM")
      (libsource (lib "eagle-import") (part "L-1334SRT"))
    )
    (comp (ref "D60")
      (value "L-1334SRT")
      (footprint "eagle-import:LED3MM")
      (libsource (lib "eagle-import") (part "L-1334SRT"))
    )
    (comp (ref "D61")
      (value "L-1334SRT")
      (footprint "eagle-import:LED3MM")
      (libsource (lib "eagle-import") (part "L-1334SRT"))
    )
    (comp (ref "D62")
      (value "L-1334SRT")
      (footprint "eagle-import:LED3MM")
      (libsource (lib "eagle-import") (part "L-1334SRT"))
    )
    (comp (ref "D63")
      (value "L-1334SRT")
      (footprint "eagle-import:LED3MM")
      (libsource (lib "eagle-import") (part "L-1334SRT"))
    )
    (comp (ref "D64")
      (value "L-1334SRT")
      (footprint "eagle-import:LED3MM")
      (libsource (lib "eagle-import") (part "L-1334SRT"))
    )
    (comp (ref "D68")
      (value "L-1334SRT")
      (footprint "eagle-import:LED3MM")
      (libsource (lib "eagle-import") (part "L-1334SRT"))
    )
    (comp (ref "D88")
      (value "L-1334SRT")
      (footprint "eagle-import:LED3MM")
      (libsource (lib "eagle-import") (part "L-1334SRT"))
    )
    (comp (ref "D92")
      (value "L-1334SRT")
      (footprint "eagle-import:LED3MM")
      (libsource (lib "eagle-import") (part "L-1334SRT"))
    )
    (comp (ref "J4")
      (value "20_HDR_LOCKING_RA")
      (footprint "eagle-import:20_HDR_LOCKING_RA")
      (libsource (lib "eagle-import") (part "20_HDR_LOCKING_RA"))
    )
    (comp (ref "Q117")
      (value "2N7000")
      (footprint "eagle-import:TO92-DGS")
      (libsource (lib "eagle-import") (part "2N7000"))
    )
    (comp (ref "Q118")
      (value "2N7000")
      (footprint "eagle-import:TO92-DGS")
      (libsource (lib "eagle-import") (part "2N7000"))
    )
    (comp (ref "Q119")
      (value "2N7000")
      (footprint "eagle-import:TO92-DGS")
      (libsource (lib "eagle-import") (part "2N7000"))
    )
    (comp (ref "Q120")
      (value "2N7000")
      (footprint "eagle-import:TO92-DGS")
      (libsource (lib "eagle-import") (part "2N7000"))
    )
    (comp (ref "Q121")
      (value "2N7000")
      (footprint "eagle-import:TO92-DGS")
      (libsource (lib "eagle-import") (part "2N7000"))
    )
    (comp (ref "Q122")
      (value "2N7000")
      (footprint "eagle-import:TO92-DGS")
      (libsource (lib "eagle-import") (part "2N7000"))
    )
    (comp (ref "Q123")
      (value "2N7000")
      (footprint "eagle-import:TO92-DGS")
      (libsource (lib "eagle-import") (part "2N7000"))
    )
    (comp (ref "Q124")
      (value "2N7000")
      (footprint "eagle-import:TO92-DGS")
      (libsource (lib "eagle-import") (part "2N7000"))
    )
    (comp (ref "Q125")
      (value "2N7000")
      (footprint "eagle-import:TO92-DGS")
      (libsource (lib "eagle-import") (part "2N7000"))
    )
    (comp (ref "Q126")
      (value "2N7000")
      (footprint "eagle-import:TO92-DGS")
      (libsource (lib "eagle-import") (part "2N7000"))
    )
    (comp (ref "Q127")
      (value "2N7000")
      (footprint "eagle-import:TO92-DGS")
      (libsource (lib "eagle-import") (part "2N7000"))
    )
    (comp (ref "Q128")
      (value "2N7000")
      (footprint "eagle-import:TO92-DGS")
      (libsource (lib "eagle-import") (part "2N7000"))
    )
    (comp (ref "Q138")
      (value "2N7000")
      (footprint "eagle-import:TO92-DGS")
      (libsource (lib "eagle-import") (part "2N7000"))
    )
    (comp (ref "Q139")
      (value "2N7000")
      (footprint "eagle-import:TO92-DGS")
      (libsource (lib "eagle-import") (part "2N7000"))
    )
    (comp (ref "Q140")
      (value "2N7000")
      (footprint "eagle-import:TO92-DGS")
      (libsource (lib "eagle-import") (part "2N7000"))
    )
    (comp (ref "R117")
      (value "10k")
      (footprint "eagle-import:R_P2INCH")
      (libsource (lib "eagle-import") (part "R_P2INCH"))
    )
    (comp (ref "R118")
      (value "470")
      (footprint "eagle-import:R_P2INCH")
      (libsource (lib "eagle-import") (part "R_P2INCH"))
    )
    (comp (ref "R119")
      (value "10k")
      (footprint "eagle-import:R_P2INCH")
      (libsource (lib "eagle-import") (part "R_P2INCH"))
    )
    (comp (ref "R120")
      (value "470")
      (footprint "eagle-import:R_P2INCH")
      (libsource (lib "eagle-import") (part "R_P2INCH"))
    )
    (comp (ref "R121")
      (value "10k")
      (footprint "eagle-import:R_P2INCH")
      (libsource (lib "eagle-import") (part "R_P2INCH"))
    )
    (comp (ref "R122")
      (value "470")
      (footprint "eagle-import:R_P2INCH")
      (libsource (lib "eagle-import") (part "R_P2INCH"))
    )
    (comp (ref "R123")
      (value "10k")
      (footprint "eagle-import:R_P2INCH")
      (libsource (lib "eagle-import") (part "R_P2INCH"))
    )
    (comp (ref "R124")
      (value "470")
      (footprint "eagle-import:R_P2INCH")
      (libsource (lib "eagle-import") (part "R_P2INCH"))
    )
    (comp (ref "R125")
      (value "10k")
      (footprint "eagle-import:R_P2INCH")
      (libsource (lib "eagle-import") (part "R_P2INCH"))
    )
    (comp (ref "R126")
      (value "470")
      (footprint "eagle-import:R_P2INCH")
      (libsource (lib "eagle-import") (part "R_P2INCH"))
    )
    (comp (ref "R127")
      (value "10k")
      (footprint "eagle-import:R_P2INCH")
      (libsource (lib "eagle-import") (part "R_P2INCH"))
    )
    (comp (ref "R128")
      (value "470")
      (footprint "eagle-import:R_P2INCH")
      (libsource (lib "eagle-import") (part "R_P2INCH"))
    )
    (comp (ref "R141")
      (value "10k")
      (footprint "eagle-import:R_P2INCH")
      (libsource (lib "eagle-import") (part "R_P2INCH"))
    )
    (comp (ref "R142")
      (value "470")
      (footprint "eagle-import:R_P2INCH")
      (libsource (lib "eagle-import") (part "R_P2INCH"))
    )
    (comp (ref "R143")
      (value "10k")
      (footprint "eagle-import:R_P2INCH")
      (libsource (lib "eagle-import") (part "R_P2INCH"))
    )
    (comp (ref "R144")
      (value "10k")
      (footprint "eagle-import:R_P2INCH")
      (libsource (lib "eagle-import") (part "R_P2INCH"))
    )
    (comp (ref "R180")
      (value "470")
      (footprint "eagle-import:R_P2INCH")
      (libsource (lib "eagle-import") (part "R_P2INCH"))
    )
    (comp (ref "R239")
      (value "10k")
      (footprint "eagle-import:R_P2INCH")
      (libsource (lib "eagle-import") (part "R_P2INCH"))
    )
    (comp (ref "R240")
      (value "10k")
      (footprint "eagle-import:R_P2INCH")
      (libsource (lib "eagle-import") (part "R_P2INCH"))
    )
    (comp (ref "R241")
      (value "10k")
      (footprint "eagle-import:R_P2INCH")
      (libsource (lib "eagle-import") (part "R_P2INCH"))
    )
    (comp (ref "R242")
      (value "10k")
      (footprint "eagle-import:R_P2INCH")
      (libsource (lib "eagle-import") (part "R_P2INCH"))
    )
    (comp (ref "R243")
      (value "10k")
      (footprint "eagle-import:R_P2INCH")
      (libsource (lib "eagle-import") (part "R_P2INCH"))
    )
    (comp (ref "R244")
      (value "10k")
      (footprint "eagle-import:R_P2INCH")
      (libsource (lib "eagle-import") (part "R_P2INCH"))
    )
    (comp (ref "R249")
      (value "470")
      (footprint "eagle-import:R_P2INCH")
      (libsource (lib "eagle-import") (part "R_P2INCH"))
    )
    (comp (ref "TP4")
      (value "TEST_LOOP")
      (footprint "eagle-import:TEST_LOOP")
      (libsource (lib "eagle-import") (part "TEST_LOOP"))
    )
    (comp (ref "D33")
      (value "L-1334SRT")
      (footprint "eagle-import:LED3MM")
      (libsource (lib "eagle-import") (part "L-1334SRT"))
    )
    (comp (ref "D34")
      (value "L-1334SRT")
      (footprint "eagle-import:LED3MM")
      (libsource (lib "eagle-import") (part "L-1334SRT"))
    )
    (comp (ref "D35")
      (value "L-1334SRT")
      (footprint "eagle-import:LED3MM")
      (libsource (lib "eagle-import") (part "L-1334SRT"))
    )
    (comp (ref "D36")
      (value "L-1334SRT")
      (footprint "eagle-import:LED3MM")
      (libsource (lib "eagle-import") (part "L-1334SRT"))
    )
    (comp (ref "D37")
      (value "L-1334SRT")
      (footprint "eagle-import:LED3MM")
      (libsource (lib "eagle-import") (part "L-1334SRT"))
    )
    (comp (ref "D38")
      (value "L-1334SRT")
      (footprint "eagle-import:LED3MM")
      (libsource (lib "eagle-import") (part "L-1334SRT"))
    )
    (comp (ref "D39")
      (value "L-1334SRT")
      (footprint "eagle-import:LED3MM")
      (libsource (lib "eagle-import") (part "L-1334SRT"))
    )
    (comp (ref "D40")
      (value "L-1334SRT")
      (footprint "eagle-import:LED3MM")
      (libsource (lib "eagle-import") (part "L-1334SRT"))
    )
    (comp (ref "D41")
      (value "L-1334SRT")
      (footprint "eagle-import:LED3MM")
      (libsource (lib "eagle-import") (part "L-1334SRT"))
    )
    (comp (ref "D42")
      (value "L-1334SRT")
      (footprint "eagle-import:LED3MM")
      (libsource (lib "eagle-import") (part "L-1334SRT"))
    )
    (comp (ref "Q65")
      (value "2N7000")
      (footprint "eagle-import:TO92-DGS")
      (libsource (lib "eagle-import") (part "2N7000"))
    )
    (comp (ref "Q66")
      (value "2N7000")
      (footprint "eagle-import:TO92-DGS")
      (libsource (lib "eagle-import") (part "2N7000"))
    )
    (comp (ref "Q67")
      (value "2N7000")
      (footprint "eagle-import:TO92-DGS")
      (libsource (lib "eagle-import") (part "2N7000"))
    )
    (comp (ref "Q68")
      (value "2N7000")
      (footprint "eagle-import:TO92-DGS")
      (libsource (lib "eagle-import") (part "2N7000"))
    )
    (comp (ref "Q69")
      (value "2N7000")
      (footprint "eagle-import:TO92-DGS")
      (libsource (lib "eagle-import") (part "2N7000"))
    )
    (comp (ref "Q70")
      (value "2N7000")
      (footprint "eagle-import:TO92-DGS")
      (libsource (lib "eagle-import") (part "2N7000"))
    )
    (comp (ref "Q71")
      (value "2N7000")
      (footprint "eagle-import:TO92-DGS")
      (libsource (lib "eagle-import") (part "2N7000"))
    )
    (comp (ref "Q72")
      (value "2N7000")
      (footprint "eagle-import:TO92-DGS")
      (libsource (lib "eagle-import") (part "2N7000"))
    )
    (comp (ref "Q73")
      (value "2N7000")
      (footprint "eagle-import:TO92-DGS")
      (libsource (lib "eagle-import") (part "2N7000"))
    )
    (comp (ref "Q74")
      (value "2N7000")
      (footprint "eagle-import:TO92-DGS")
      (libsource (lib "eagle-import") (part "2N7000"))
    )
    (comp (ref "Q75")
      (value "2N7000")
      (footprint "eagle-import:TO92-DGS")
      (libsource (lib "eagle-import") (part "2N7000"))
    )
    (comp (ref "Q76")
      (value "2N7000")
      (footprint "eagle-import:TO92-DGS")
      (libsource (lib "eagle-import") (part "2N7000"))
    )
    (comp (ref "Q77")
      (value "2N7000")
      (footprint "eagle-import:TO92-DGS")
      (libsource (lib "eagle-import") (part "2N7000"))
    )
    (comp (ref "Q78")
      (value "2N7000")
      (footprint "eagle-import:TO92-DGS")
      (libsource (lib "eagle-import") (part "2N7000"))
    )
    (comp (ref "Q79")
      (value "2N7000")
      (footprint "eagle-import:TO92-DGS")
      (libsource (lib "eagle-import") (part "2N7000"))
    )
    (comp (ref "Q80")
      (value "2N7000")
      (footprint "eagle-import:TO92-DGS")
      (libsource (lib "eagle-import") (part "2N7000"))
    )
    (comp (ref "Q81")
      (value "2N7000")
      (footprint "eagle-import:TO92-DGS")
      (libsource (lib "eagle-import") (part "2N7000"))
    )
    (comp (ref "Q82")
      (value "2N7000")
      (footprint "eagle-import:TO92-DGS")
      (libsource (lib "eagle-import") (part "2N7000"))
    )
    (comp (ref "Q83")
      (value "2N7000")
      (footprint "eagle-import:TO92-DGS")
      (libsource (lib "eagle-import") (part "2N7000"))
    )
    (comp (ref "Q84")
      (value "2N7000")
      (footprint "eagle-import:TO92-DGS")
      (libsource (lib "eagle-import") (part "2N7000"))
    )
    (comp (ref "R65")
      (value "10k")
      (footprint "eagle-import:R_P2INCH")
      (libsource (lib "eagle-import") (part "R_P2INCH"))
    )
    (comp (ref "R66")
      (value "470")
      (footprint "eagle-import:R_P2INCH")
      (libsource (lib "eagle-import") (part "R_P2INCH"))
    )
    (comp (ref "R67")
      (value "10k")
      (footprint "eagle-import:R_P2INCH")
      (libsource (lib "eagle-import") (part "R_P2INCH"))
    )
    (comp (ref "R68")
      (value "470")
      (footprint "eagle-import:R_P2INCH")
      (libsource (lib "eagle-import") (part "R_P2INCH"))
    )
    (comp (ref "R69")
      (value "10k")
      (footprint "eagle-import:R_P2INCH")
      (libsource (lib "eagle-import") (part "R_P2INCH"))
    )
    (comp (ref "R70")
      (value "470")
      (footprint "eagle-import:R_P2INCH")
      (libsource (lib "eagle-import") (part "R_P2INCH"))
    )
    (comp (ref "R71")
      (value "10k")
      (footprint "eagle-import:R_P2INCH")
      (libsource (lib "eagle-import") (part "R_P2INCH"))
    )
    (comp (ref "R72")
      (value "470")
      (footprint "eagle-import:R_P2INCH")
      (libsource (lib "eagle-import") (part "R_P2INCH"))
    )
    (comp (ref "R73")
      (value "10k")
      (footprint "eagle-import:R_P2INCH")
      (libsource (lib "eagle-import") (part "R_P2INCH"))
    )
    (comp (ref "R74")
      (value "470")
      (footprint "eagle-import:R_P2INCH")
      (libsource (lib "eagle-import") (part "R_P2INCH"))
    )
    (comp (ref "R75")
      (value "10k")
      (footprint "eagle-import:R_P2INCH")
      (libsource (lib "eagle-import") (part "R_P2INCH"))
    )
    (comp (ref "R76")
      (value "470")
      (footprint "eagle-import:R_P2INCH")
      (libsource (lib "eagle-import") (part "R_P2INCH"))
    )
    (comp (ref "R77")
      (value "10k")
      (footprint "eagle-import:R_P2INCH")
      (libsource (lib "eagle-import") (part "R_P2INCH"))
    )
    (comp (ref "R78")
      (value "470")
      (footprint "eagle-import:R_P2INCH")
      (libsource (lib "eagle-import") (part "R_P2INCH"))
    )
    (comp (ref "R79")
      (value "10k")
      (footprint "eagle-import:R_P2INCH")
      (libsource (lib "eagle-import") (part "R_P2INCH"))
    )
    (comp (ref "R80")
      (value "470")
      (footprint "eagle-import:R_P2INCH")
      (libsource (lib "eagle-import") (part "R_P2INCH"))
    )
    (comp (ref "R81")
      (value "10k")
      (footprint "eagle-import:R_P2INCH")
      (libsource (lib "eagle-import") (part "R_P2INCH"))
    )
    (comp (ref "R82")
      (value "470")
      (footprint "eagle-import:R_P2INCH")
      (libsource (lib "eagle-import") (part "R_P2INCH"))
    )
    (comp (ref "R83")
      (value "10k")
      (footprint "eagle-import:R_P2INCH")
      (libsource (lib "eagle-import") (part "R_P2INCH"))
    )
    (comp (ref "R84")
      (value "470")
      (footprint "eagle-import:R_P2INCH")
      (libsource (lib "eagle-import") (part "R_P2INCH"))
    )
    (comp (ref "R213")
      (value "10k")
      (footprint "eagle-import:R_P2INCH")
      (libsource (lib "eagle-import") (part "R_P2INCH"))
    )
    (comp (ref "R214")
      (value "10k")
      (footprint "eagle-import:R_P2INCH")
      (libsource (lib "eagle-import") (part "R_P2INCH"))
    )
    (comp (ref "R215")
      (value "10k")
      (footprint "eagle-import:R_P2INCH")
      (libsource (lib "eagle-import") (part "R_P2INCH"))
    )
    (comp (ref "R216")
      (value "10k")
      (footprint "eagle-import:R_P2INCH")
      (libsource (lib "eagle-import") (part "R_P2INCH"))
    )
    (comp (ref "R217")
      (value "10k")
      (footprint "eagle-import:R_P2INCH")
      (libsource (lib "eagle-import") (part "R_P2INCH"))
    )
    (comp (ref "R218")
      (value "10k")
      (footprint "eagle-import:R_P2INCH")
      (libsource (lib "eagle-import") (part "R_P2INCH"))
    )
    (comp (ref "R219")
      (value "10k")
      (footprint "eagle-import:R_P2INCH")
      (libsource (lib "eagle-import") (part "R_P2INCH"))
    )
    (comp (ref "R220")
      (value "10k")
      (footprint "eagle-import:R_P2INCH")
      (libsource (lib "eagle-import") (part "R_P2INCH"))
    )
    (comp (ref "R221")
      (value "10k")
      (footprint "eagle-import:R_P2INCH")
      (libsource (lib "eagle-import") (part "R_P2INCH"))
    )
    (comp (ref "R222")
      (value "10k")
      (footprint "eagle-import:R_P2INCH")
      (libsource (lib "eagle-import") (part "R_P2INCH"))
    )
    (comp (ref "D93")
      (value "L-1334SRT")
      (footprint "eagle-import:LED3MM")
      (libsource (lib "eagle-import") (part "L-1334SRT"))
    )
    (comp (ref "J5")
      (value "20_HDR_LOCKING_RA")
      (footprint "eagle-import:20_HDR_LOCKING_RA")
      (libsource (lib "eagle-import") (part "20_HDR_LOCKING_RA"))
    )
    (comp (ref "Q237")
      (value "2N7000")
      (footprint "eagle-import:TO92-DGS")
      (libsource (lib "eagle-import") (part "2N7000"))
    )
    (comp (ref "Q238")
      (value "2N7000")
      (footprint "eagle-import:TO92-DGS")
      (libsource (lib "eagle-import") (part "2N7000"))
    )
    (comp (ref "Q239")
      (value "2N7000")
      (footprint "eagle-import:TO92-DGS")
      (libsource (lib "eagle-import") (part "2N7000"))
    )
    (comp (ref "Q240")
      (value "2N7000")
      (footprint "eagle-import:TO92-DGS")
      (libsource (lib "eagle-import") (part "2N7000"))
    )
    (comp (ref "Q241")
      (value "2N7000")
      (footprint "eagle-import:TO92-DGS")
      (libsource (lib "eagle-import") (part "2N7000"))
    )
    (comp (ref "Q242")
      (value "2N7000")
      (footprint "eagle-import:TO92-DGS")
      (libsource (lib "eagle-import") (part "2N7000"))
    )
    (comp (ref "R245")
      (value "10k")
      (footprint "eagle-import:R_P2INCH")
      (libsource (lib "eagle-import") (part "R_P2INCH"))
    )
    (comp (ref "R251")
      (value "470")
      (footprint "eagle-import:R_P2INCH")
      (libsource (lib "eagle-import") (part "R_P2INCH"))
    )
    (comp (ref "R252")
      (value "10k")
      (footprint "eagle-import:R_P2INCH")
      (libsource (lib "eagle-import") (part "R_P2INCH"))
    )
    (comp (ref "R268")
      (value "10k")
      (footprint "eagle-import:R_P2INCH")
      (libsource (lib "eagle-import") (part "R_P2INCH"))
    )
    (comp (ref "D81")
      (value "L-1334SRT")
      (footprint "eagle-import:LED3MM")
      (libsource (lib "eagle-import") (part "L-1334SRT"))
    )
    (comp (ref "D82")
      (value "L-1334SRT")
      (footprint "eagle-import:LED3MM")
      (libsource (lib "eagle-import") (part "L-1334SRT"))
    )
    (comp (ref "D83")
      (value "L-1334SRT")
      (footprint "eagle-import:LED3MM")
      (libsource (lib "eagle-import") (part "L-1334SRT"))
    )
    (comp (ref "D84")
      (value "L-1334SRT")
      (footprint "eagle-import:LED3MM")
      (libsource (lib "eagle-import") (part "L-1334SRT"))
    )
    (comp (ref "Q201")
      (value "2N7000")
      (footprint "eagle-import:TO92-DGS")
      (libsource (lib "eagle-import") (part "2N7000"))
    )
    (comp (ref "Q202")
      (value "2N7000")
      (footprint "eagle-import:TO92-DGS")
      (libsource (lib "eagle-import") (part "2N7000"))
    )
    (comp (ref "Q203")
      (value "2N7000")
      (footprint "eagle-import:TO92-DGS")
      (libsource (lib "eagle-import") (part "2N7000"))
    )
    (comp (ref "Q204")
      (value "2N7000")
      (footprint "eagle-import:TO92-DGS")
      (libsource (lib "eagle-import") (part "2N7000"))
    )
    (comp (ref "Q205")
      (value "2N7000")
      (footprint "eagle-import:TO92-DGS")
      (libsource (lib "eagle-import") (part "2N7000"))
    )
    (comp (ref "Q206")
      (value "2N7000")
      (footprint "eagle-import:TO92-DGS")
      (libsource (lib "eagle-import") (part "2N7000"))
    )
    (comp (ref "Q207")
      (value "2N7000")
      (footprint "eagle-import:TO92-DGS")
      (libsource (lib "eagle-import") (part "2N7000"))
    )
    (comp (ref "Q208")
      (value "2N7000")
      (footprint "eagle-import:TO92-DGS")
      (libsource (lib "eagle-import") (part "2N7000"))
    )
    (comp (ref "Q209")
      (value "2N7000")
      (footprint "eagle-import:TO92-DGS")
      (libsource (lib "eagle-import") (part "2N7000"))
    )
    (comp (ref "Q210")
      (value "2N7000")
      (footprint "eagle-import:TO92-DGS")
      (libsource (lib "eagle-import") (part "2N7000"))
    )
    (comp (ref "Q211")
      (value "2N7000")
      (footprint "eagle-import:TO92-DGS")
      (libsource (lib "eagle-import") (part "2N7000"))
    )
    (comp (ref "Q212")
      (value "2N7000")
      (footprint "eagle-import:TO92-DGS")
      (libsource (lib "eagle-import") (part "2N7000"))
    )
    (comp (ref "Q213")
      (value "2N7000")
      (footprint "eagle-import:TO92-DGS")
      (libsource (lib "eagle-import") (part "2N7000"))
    )
    (comp (ref "Q214")
      (value "2N7000")
      (footprint "eagle-import:TO92-DGS")
      (libsource (lib "eagle-import") (part "2N7000"))
    )
    (comp (ref "Q215")
      (value "2N7000")
      (footprint "eagle-import:TO92-DGS")
      (libsource (lib "eagle-import") (part "2N7000"))
    )
    (comp (ref "Q216")
      (value "2N7000")
      (footprint "eagle-import:TO92-DGS")
      (libsource (lib "eagle-import") (part "2N7000"))
    )
    (comp (ref "Q217")
      (value "2N7000")
      (footprint "eagle-import:TO92-DGS")
      (libsource (lib "eagle-import") (part "2N7000"))
    )
    (comp (ref "Q218")
      (value "2N7000")
      (footprint "eagle-import:TO92-DGS")
      (libsource (lib "eagle-import") (part "2N7000"))
    )
    (comp (ref "Q219")
      (value "2N7000")
      (footprint "eagle-import:TO92-DGS")
      (libsource (lib "eagle-import") (part "2N7000"))
    )
    (comp (ref "Q220")
      (value "2N7000")
      (footprint "eagle-import:TO92-DGS")
      (libsource (lib "eagle-import") (part "2N7000"))
    )
    (comp (ref "Q233")
      (value "2N7000")
      (footprint "eagle-import:TO92-DGS")
      (libsource (lib "eagle-import") (part "2N7000"))
    )
    (comp (ref "Q234")
      (value "2N7000")
      (footprint "eagle-import:TO92-DGS")
      (libsource (lib "eagle-import") (part "2N7000"))
    )
    (comp (ref "Q235")
      (value "2N7000")
      (footprint "eagle-import:TO92-DGS")
      (libsource (lib "eagle-import") (part "2N7000"))
    )
    (comp (ref "Q236")
      (value "2N7000")
      (footprint "eagle-import:TO92-DGS")
      (libsource (lib "eagle-import") (part "2N7000"))
    )
    (comp (ref "R169")
      (value "10k")
      (footprint "eagle-import:R_P2INCH")
      (libsource (lib "eagle-import") (part "R_P2INCH"))
    )
    (comp (ref "R170")
      (value "470")
      (footprint "eagle-import:R_P2INCH")
      (libsource (lib "eagle-import") (part "R_P2INCH"))
    )
    (comp (ref "R171")
      (value "10k")
      (footprint "eagle-import:R_P2INCH")
      (libsource (lib "eagle-import") (part "R_P2INCH"))
    )
    (comp (ref "R172")
      (value "470")
      (footprint "eagle-import:R_P2INCH")
      (libsource (lib "eagle-import") (part "R_P2INCH"))
    )
    (comp (ref "R173")
      (value "10k")
      (footprint "eagle-import:R_P2INCH")
      (libsource (lib "eagle-import") (part "R_P2INCH"))
    )
    (comp (ref "R174")
      (value "470")
      (footprint "eagle-import:R_P2INCH")
      (libsource (lib "eagle-import") (part "R_P2INCH"))
    )
    (comp (ref "R175")
      (value "10k")
      (footprint "eagle-import:R_P2INCH")
      (libsource (lib "eagle-import") (part "R_P2INCH"))
    )
    (comp (ref "R176")
      (value "470")
      (footprint "eagle-import:R_P2INCH")
      (libsource (lib "eagle-import") (part "R_P2INCH"))
    )
    (comp (ref "R264")
      (value "10k")
      (footprint "eagle-import:R_P2INCH")
      (libsource (lib "eagle-import") (part "R_P2INCH"))
    )
    (comp (ref "R265")
      (value "10k")
      (footprint "eagle-import:R_P2INCH")
      (libsource (lib "eagle-import") (part "R_P2INCH"))
    )
    (comp (ref "R266")
      (value "10k")
      (footprint "eagle-import:R_P2INCH")
      (libsource (lib "eagle-import") (part "R_P2INCH"))
    )
    (comp (ref "R267")
      (value "10k")
      (footprint "eagle-import:R_P2INCH")
      (libsource (lib "eagle-import") (part "R_P2INCH"))
    )
  )
  (nets
    (net (code "1") (name "+5V") (class "Default")
      (node (ref "C1") (pin "1") (pinfunction "1_1") (pintype "passive"))
      (node (ref "C2") (pin "1") (pinfunction "1_1") (pintype "passive"))
      (node (ref "C3") (pin "1") (pinfunction "1_1") (pintype "passive"))
      (node (ref "C4") (pin "1") (pinfunction "1_1") (pintype "passive"))
      (node (ref "C5") (pin "1") (pinfunction "1_1") (pintype "passive"))
      (node (ref "C6") (pin "1") (pinfunction "1_1") (pintype "passive"))
      (node (ref "C7") (pin "A") (pinfunction "A_A") (pintype "passive"))
      (node (ref "C8") (pin "1") (pinfunction "1_1") (pintype "passive"))
      (node (ref "D1") (pin "A") (pinfunction "A_A") (pintype "passive"))
      (node (ref "D10") (pin "A") (pinfunction "A_A") (pintype "passive"))
      (node (ref "D11") (pin "A") (pinfunction "A_A") (pintype "passive"))
      (node (ref "D12") (pin "A") (pinfunction "A_A") (pintype "passive"))
      (node (ref "D13") (pin "A") (pinfunction "A_A") (pintype "passive"))
      (node (ref "D14") (pin "A") (pinfunction "A_A") (pintype "passive"))
      (node (ref "D15") (pin "A") (pinfunction "A_A") (pintype "passive"))
      (node (ref "D16") (pin "A") (pinfunction "A_A") (pintype "passive"))
      (node (ref "D17") (pin "A") (pinfunction "A_A") (pintype "passive"))
      (node (ref "D18") (pin "A") (pinfunction "A_A") (pintype "passive"))
      (node (ref "D19") (pin "A") (pinfunction "A_A") (pintype "passive"))
      (node (ref "D2") (pin "A") (pinfunction "A_A") (pintype "passive"))
      (node (ref "D20") (pin "A") (pinfunction "A_A") (pintype "passive"))
      (node (ref "D21") (pin "A") (pinfunction "A_A") (pintype "passive"))
      (node (ref "D22") (pin "A") (pinfunction "A_A") (pintype "passive"))
      (node (ref "D23") (pin "A") (pinfunction "A_A") (pintype "passive"))
      (node (ref "D24") (pin "A") (pinfunction "A_A") (pintype "passive"))
      (node (ref "D25") (pin "A") (pinfunction "A_A") (pintype "passive"))
      (node (ref "D26") (pin "A") (pinfunction "A_A") (pintype "passive"))
      (node (ref "D27") (pin "A") (pinfunction "A_A") (pintype "passive"))
      (node (ref "D28") (pin "A") (pinfunction "A_A") (pintype "passive"))
      (node (ref "D29") (pin "A") (pinfunction "A_A") (pintype "passive"))
      (node (ref "D3") (pin "A") (pinfunction "A_A") (pintype "passive"))
      (node (ref "D30") (pin "A") (pinfunction "A_A") (pintype "passive"))
      (node (ref "D31") (pin "A") (pinfunction "A_A") (pintype "passive"))
      (node (ref "D32") (pin "A") (pinfunction "A_A") (pintype "passive"))
      (node (ref "D33") (pin "A") (pinfunction "A_A") (pintype "passive"))
      (node (ref "D34") (pin "A") (pinfunction "A_A") (pintype "passive"))
      (node (ref "D35") (pin "A") (pinfunction "A_A") (pintype "passive"))
      (node (ref "D36") (pin "A") (pinfunction "A_A") (pintype "passive"))
      (node (ref "D37") (pin "A") (pinfunction "A_A") (pintype "passive"))
      (node (ref "D38") (pin "A") (pinfunction "A_A") (pintype "passive"))
      (node (ref "D39") (pin "A") (pinfunction "A_A") (pintype "passive"))
      (node (ref "D4") (pin "A") (pinfunction "A_A") (pintype "passive"))
      (node (ref "D40") (pin "A") (pinfunction "A_A") (pintype "passive"))
      (node (ref "D41") (pin "A") (pinfunction "A_A") (pintype "passive"))
      (node (ref "D42") (pin "A") (pinfunction "A_A") (pintype "passive"))
      (node (ref "D43") (pin "A") (pinfunction "A_A") (pintype "passive"))
      (node (ref "D44") (pin "A") (pinfunction "A_A") (pintype "passive"))
      (node (ref "D45") (pin "A") (pinfunction "A_A") (pintype "passive"))
      (node (ref "D46") (pin "A") (pinfunction "A_A") (pintype "passive"))
      (node (ref "D47") (pin "A") (pinfunction "A_A") (pintype "passive"))
      (node (ref "D48") (pin "A") (pinfunction "A_A") (pintype "passive"))
      (node (ref "D49") (pin "A") (pinfunction "A_A") (pintype "passive"))
      (node (ref "D5") (pin "A") (pinfunction "A_A") (pintype "passive"))
      (node (ref "D50") (pin "A") (pinfunction "A_A") (pintype "passive"))
      (node (ref "D51") (pin "A") (pinfunction "A_A") (pintype "passive"))
      (node (ref "D52") (pin "A") (pinfunction "A_A") (pintype "passive"))
      (node (ref "D53") (pin "A") (pinfunction "A_A") (pintype "passive"))
      (node (ref "D54") (pin "A") (pinfunction "A_A") (pintype "passive"))
      (node (ref "D55") (pin "A") (pinfunction "A_A") (pintype "passive"))
      (node (ref "D56") (pin "A") (pinfunction "A_A") (pintype "passive"))
      (node (ref "D57") (pin "A") (pinfunction "A_A") (pintype "passive"))
      (node (ref "D58") (pin "A") (pinfunction "A_A") (pintype "passive"))
      (node (ref "D59") (pin "A") (pinfunction "A_A") (pintype "passive"))
      (node (ref "D6") (pin "A") (pinfunction "A_A") (pintype "passive"))
      (node (ref "D60") (pin "A") (pinfunction "A_A") (pintype "passive"))
      (node (ref "D61") (pin "A") (pinfunction "A_A") (pintype "passive"))
      (node (ref "D62") (pin "A") (pinfunction "A_A") (pintype "passive"))
      (node (ref "D63") (pin "A") (pinfunction "A_A") (pintype "passive"))
      (node (ref "D64") (pin "A") (pinfunction "A_A") (pintype "passive"))
      (node (ref "D65") (pin "A") (pinfunction "A_A") (pintype "passive"))
      (node (ref "D66") (pin "A") (pinfunction "A_A") (pintype "passive"))
      (node (ref "D67") (pin "A") (pinfunction "A_A") (pintype "passive"))
      (node (ref "D68") (pin "A") (pinfunction "A_A") (pintype "passive"))
      (node (ref "D69") (pin "A") (pinfunction "A_A") (pintype "passive"))
      (node (ref "D7") (pin "A") (pinfunction "A_A") (pintype "passive"))
      (node (ref "D70") (pin "A") (pinfunction "A_A") (pintype "passive"))
      (node (ref "D71") (pin "A") (pinfunction "A_A") (pintype "passive"))
      (node (ref "D72") (pin "A") (pinfunction "A_A") (pintype "passive"))
      (node (ref "D73") (pin "A") (pinfunction "A_A") (pintype "passive"))
      (node (ref "D74") (pin "A") (pinfunction "A_A") (pintype "passive"))
      (node (ref "D75") (pin "A") (pinfunction "A_A") (pintype "passive"))
      (node (ref "D76") (pin "A") (pinfunction "A_A") (pintype "passive"))
      (node (ref "D77") (pin "A") (pinfunction "A_A") (pintype "passive"))
      (node (ref "D78") (pin "A") (pinfunction "A_A") (pintype "passive"))
      (node (ref "D79") (pin "A") (pinfunction "A_A") (pintype "passive"))
      (node (ref "D8") (pin "A") (pinfunction "A_A") (pintype "passive"))
      (node (ref "D80") (pin "A") (pinfunction "A_A") (pintype "passive"))
      (node (ref "D81") (pin "A") (pinfunction "A_A") (pintype "passive"))
      (node (ref "D82") (pin "A") (pinfunction "A_A") (pintype "passive"))
      (node (ref "D83") (pin "A") (pinfunction "A_A") (pintype "passive"))
      (node (ref "D84") (pin "A") (pinfunction "A_A") (pintype "passive"))
      (node (ref "D85") (pin "A") (pinfunction "A_A") (pintype "passive"))
      (node (ref "D86") (pin "A") (pinfunction "A_A") (pintype "passive"))
      (node (ref "D87") (pin "A") (pinfunction "A_A") (pintype "passive"))
      (node (ref "D88") (pin "A") (pinfunction "A_A") (pintype "passive"))
      (node (ref "D89") (pin "A") (pinfunction "A_A") (pintype "passive"))
      (node (ref "D9") (pin "A") (pinfunction "A_A") (pintype "passive"))
      (node (ref "D90") (pin "A") (pinfunction "A_A") (pintype "passive"))
      (node (ref "D91") (pin "A") (pinfunction "A_A") (pintype "passive"))
      (node (ref "D92") (pin "A") (pinfunction "A_A") (pintype "passive"))
      (node (ref "R1") (pin "2") (pinfunction "2_2") (pintype "passive"))
      (node (ref "R101") (pin "2") (pinfunction "2_2") (pintype "passive"))
      (node (ref "R103") (pin "2") (pinfunction "2_2") (pintype "passive"))
      (node (ref "R105") (pin "2") (pinfunction "2_2") (pintype "passive"))
      (node (ref "R107") (pin "2") (pinfunction "2_2") (pintype "passive"))
      (node (ref "R109") (pin "2") (pinfunction "2_2") (pintype "passive"))
      (node (ref "R11") (pin "2") (pinfunction "2_2") (pintype "passive"))
      (node (ref "R111") (pin "2") (pinfunction "2_2") (pintype "passive"))
      (node (ref "R113") (pin "2") (pinfunction "2_2") (pintype "passive"))
      (node (ref "R115") (pin "2") (pinfunction "2_2") (pintype "passive"))
      (node (ref "R117") (pin "2") (pinfunction "2_2") (pintype "passive"))
      (node (ref "R119") (pin "2") (pinfunction "2_2") (pintype "passive"))
      (node (ref "R121") (pin "2") (pinfunction "2_2") (pintype "passive"))
      (node (ref "R123") (pin "2") (pinfunction "2_2") (pintype "passive"))
      (node (ref "R125") (pin "2") (pinfunction "2_2") (pintype "passive"))
      (node (ref "R127") (pin "2") (pinfunction "2_2") (pintype "passive"))
      (node (ref "R129") (pin "2") (pinfunction "2_2") (pintype "passive"))
      (node (ref "R13") (pin "2") (pinfunction "2_2") (pintype "passive"))
      (node (ref "R131") (pin "2") (pinfunction "2_2") (pintype "passive"))
      (node (ref "R132") (pin "2") (pinfunction "2_2") (pintype "passive"))
      (node (ref "R133") (pin "2") (pinfunction "2_2") (pintype "passive"))
      (node (ref "R135") (pin "2") (pinfunction "2_2") (pintype "passive"))
      (node (ref "R136") (pin "2") (pinfunction "2_2") (pintype "passive"))
      (node (ref "R137") (pin "2") (pinfunction "2_2") (pintype "passive"))
      (node (ref "R139") (pin "2") (pinfunction "2_2") (pintype "passive"))
      (node (ref "R140") (pin "2") (pinfunction "2_2") (pintype "passive"))
      (node (ref "R141") (pin "2") (pinfunction "2_2") (pintype "passive"))
      (node (ref "R143") (pin "2") (pinfunction "2_2") (pintype "passive"))
      (node (ref "R144") (pin "2") (pinfunction "2_2") (pintype "passive"))
      (node (ref "R145") (pin "2") (pinfunction "2_2") (pintype "passive"))
      (node (ref "R147") (pin "2") (pinfunction "2_2") (pintype "passive"))
      (node (ref "R149") (pin "2") (pinfunction "2_2") (pintype "passive"))
      (node (ref "R15") (pin "2") (pinfunction "2_2") (pintype "passive"))
      (node (ref "R151") (pin "2") (pinfunction "2_2") (pintype "passive"))
      (node (ref "R153") (pin "2") (pinfunction "2_2") (pintype "passive"))
      (node (ref "R155") (pin "2") (pinfunction "2_2") (pintype "passive"))
      (node (ref "R157") (pin "2") (pinfunction "2_2") (pintype "passive"))
      (node (ref "R159") (pin "2") (pinfunction "2_2") (pintype "passive"))
      (node (ref "R161") (pin "2") (pinfunction "2_2") (pintype "passive"))
      (node (ref "R163") (pin "2") (pinfunction "2_2") (pintype "passive"))
      (node (ref "R165") (pin "2") (pinfunction "2_2") (pintype "passive"))
      (node (ref "R167") (pin "2") (pinfunction "2_2") (pintype "passive"))
      (node (ref "R169") (pin "2") (pinfunction "2_2") (pintype "passive"))
      (node (ref "R17") (pin "2") (pinfunction "2_2") (pintype "passive"))
      (node (ref "R171") (pin "2") (pinfunction "2_2") (pintype "passive"))
      (node (ref "R173") (pin "2") (pinfunction "2_2") (pintype "passive"))
      (node (ref "R175") (pin "2") (pinfunction "2_2") (pintype "passive"))
      (node (ref "R181") (pin "2") (pinfunction "2_2") (pintype "passive"))
      (node (ref "R182") (pin "2") (pinfunction "2_2") (pintype "passive"))
      (node (ref "R183") (pin "2") (pinfunction "2_2") (pintype "passive"))
      (node (ref "R184") (pin "2") (pinfunction "2_2") (pintype "passive"))
      (node (ref "R185") (pin "2") (pinfunction "2_2") (pintype "passive"))
      (node (ref "R186") (pin "2") (pinfunction "2_2") (pintype "passive"))
      (node (ref "R187") (pin "2") (pinfunction "2_2") (pintype "passive"))
      (node (ref "R188") (pin "2") (pinfunction "2_2") (pintype "passive"))
      (node (ref "R189") (pin "2") (pinfunction "2_2") (pintype "passive"))
      (node (ref "R19") (pin "2") (pinfunction "2_2") (pintype "passive"))
      (node (ref "R190") (pin "2") (pinfunction "2_2") (pintype "passive"))
      (node (ref "R191") (pin "2") (pinfunction "2_2") (pintype "passive"))
      (node (ref "R192") (pin "2") (pinfunction "2_2") (pintype "passive"))
      (node (ref "R193") (pin "2") (pinfunction "2_2") (pintype "passive"))
      (node (ref "R194") (pin "2") (pinfunction "2_2") (pintype "passive"))
      (node (ref "R195") (pin "2") (pinfunction "2_2") (pintype "passive"))
      (node (ref "R196") (pin "2") (pinfunction "2_2") (pintype "passive"))
      (node (ref "R197") (pin "2") (pinfunction "2_2") (pintype "passive"))
      (node (ref "R198") (pin "2") (pinfunction "2_2") (pintype "passive"))
      (node (ref "R199") (pin "2") (pinfunction "2_2") (pintype "passive"))
      (node (ref "R200") (pin "2") (pinfunction "2_2") (pintype "passive"))
      (node (ref "R201") (pin "2") (pinfunction "2_2") (pintype "passive"))
      (node (ref "R202") (pin "2") (pinfunction "2_2") (pintype "passive"))
      (node (ref "R203") (pin "2") (pinfunction "2_2") (pintype "passive"))
      (node (ref "R204") (pin "2") (pinfunction "2_2") (pintype "passive"))
      (node (ref "R205") (pin "2") (pinfunction "2_2") (pintype "passive"))
      (node (ref "R206") (pin "2") (pinfunction "2_2") (pintype "passive"))
      (node (ref "R207") (pin "2") (pinfunction "2_2") (pintype "passive"))
      (node (ref "R208") (pin "2") (pinfunction "2_2") (pintype "passive"))
      (node (ref "R209") (pin "2") (pinfunction "2_2") (pintype "passive"))
      (node (ref "R21") (pin "2") (pinfunction "2_2") (pintype "passive"))
      (node (ref "R210") (pin "2") (pinfunction "2_2") (pintype "passive"))
      (node (ref "R211") (pin "2") (pinfunction "2_2") (pintype "passive"))
      (node (ref "R212") (pin "2") (pinfunction "2_2") (pintype "passive"))
      (node (ref "R213") (pin "2") (pinfunction "2_2") (pintype "passive"))
      (node (ref "R214") (pin "2") (pinfunction "2_2") (pintype "passive"))
      (node (ref "R215") (pin "2") (pinfunction "2_2") (pintype "passive"))
      (node (ref "R216") (pin "2") (pinfunction "2_2") (pintype "passive"))
      (node (ref "R217") (pin "2") (pinfunction "2_2") (pintype "passive"))
      (node (ref "R218") (pin "2") (pinfunction "2_2") (pintype "passive"))
      (node (ref "R219") (pin "2") (pinfunction "2_2") (pintype "passive"))
      (node (ref "R220") (pin "2") (pinfunction "2_2") (pintype "passive"))
      (node (ref "R221") (pin "2") (pinfunction "2_2") (pintype "passive"))
      (node (ref "R222") (pin "2") (pinfunction "2_2") (pintype "passive"))
      (node (ref "R223") (pin "2") (pinfunction "2_2") (pintype "passive"))
      (node (ref "R224") (pin "2") (pinfunction "2_2") (pintype "passive"))
      (node (ref "R225") (pin "2") (pinfunction "2_2") (pintype "passive"))
      (node (ref "R226") (pin "2") (pinfunction "2_2") (pintype "passive"))
      (node (ref "R227") (pin "2") (pinfunction "2_2") (pintype "passive"))
      (node (ref "R228") (pin "2") (pinfunction "2_2") (pintype "passive"))
      (node (ref "R229") (pin "2") (pinfunction "2_2") (pintype "passive"))
      (node (ref "R23") (pin "2") (pinfunction "2_2") (pintype "passive"))
      (node (ref "R230") (pin "2") (pinfunction "2_2") (pintype "passive"))
      (node (ref "R231") (pin "2") (pinfunction "2_2") (pintype "passive"))
      (node (ref "R232") (pin "2") (pinfunction "2_2") (pintype "passive"))
      (node (ref "R233") (pin "2") (pinfunction "2_2") (pintype "passive"))
      (node (ref "R234") (pin "2") (pinfunction "2_2") (pintype "passive"))
      (node (ref "R235") (pin "2") (pinfunction "2_2") (pintype "passive"))
      (node (ref "R236") (pin "2") (pinfunction "2_2") (pintype "passive"))
      (node (ref "R237") (pin "2") (pinfunction "2_2") (pintype "passive"))
      (node (ref "R238") (pin "2") (pinfunction "2_2") (pintype "passive"))
      (node (ref "R239") (pin "2") (pinfunction "2_2") (pintype "passive"))
      (node (ref "R240") (pin "2") (pinfunction "2_2") (pintype "passive"))
      (node (ref "R241") (pin "2") (pinfunction "2_2") (pintype "passive"))
      (node (ref "R242") (pin "2") (pinfunction "2_2") (pintype "passive"))
      (node (ref "R243") (pin "2") (pinfunction "2_2") (pintype "passive"))
      (node (ref "R244") (pin "2") (pinfunction "2_2") (pintype "passive"))
      (node (ref "R245") (pin "2") (pinfunction "2_2") (pintype "passive"))
      (node (ref "R25") (pin "2") (pinfunction "2_2") (pintype "passive"))
      (node (ref "R250") (pin "2") (pinfunction "2_2") (pintype "passive"))
      (node (ref "R251") (pin "2") (pinfunction "2_2") (pintype "passive"))
      (node (ref "R252") (pin "2") (pinfunction "2_2") (pintype "passive"))
      (node (ref "R253") (pin "2") (pinfunction "2_2") (pintype "passive"))
      (node (ref "R254") (pin "2") (pinfunction "2_2") (pintype "passive"))
      (node (ref "R255") (pin "2") (pinfunction "2_2") (pintype "passive"))
      (node (ref "R256") (pin "2") (pinfunction "2_2") (pintype "passive"))
      (node (ref "R257") (pin "2") (pinfunction "2_2") (pintype "passive"))
      (node (ref "R258") (pin "2") (pinfunction "2_2") (pintype "passive"))
      (node (ref "R259") (pin "2") (pinfunction "2_2") (pintype "passive"))
      (node (ref "R260") (pin "2") (pinfunction "2_2") (pintype "passive"))
      (node (ref "R261") (pin "2") (pinfunction "2_2") (pintype "passive"))
      (node (ref "R262") (pin "2") (pinfunction "2_2") (pintype "passive"))
      (node (ref "R263") (pin "2") (pinfunction "2_2") (pintype "passive"))
      (node (ref "R264") (pin "2") (pinfunction "2_2") (pintype "passive"))
      (node (ref "R265") (pin "2") (pinfunction "2_2") (pintype "passive"))
      (node (ref "R266") (pin "2") (pinfunction "2_2") (pintype "passive"))
      (node (ref "R267") (pin "2") (pinfunction "2_2") (pintype "passive"))
      (node (ref "R268") (pin "2") (pinfunction "2_2") (pintype "passive"))
      (node (ref "R27") (pin "2") (pinfunction "2_2") (pintype "passive"))
      (node (ref "R29") (pin "2") (pinfunction "2_2") (pintype "passive"))
      (node (ref "R3") (pin "2") (pinfunction "2_2") (pintype "passive"))
      (node (ref "R31") (pin "2") (pinfunction "2_2") (pintype "passive"))
      (node (ref "R33") (pin "2") (pinfunction "2_2") (pintype "passive"))
      (node (ref "R35") (pin "2") (pinfunction "2_2") (pintype "passive"))
      (node (ref "R37") (pin "2") (pinfunction "2_2") (pintype "passive"))
      (node (ref "R39") (pin "2") (pinfunction "2_2") (pintype "passive"))
      (node (ref "R41") (pin "2") (pinfunction "2_2") (pintype "passive"))
      (node (ref "R43") (pin "2") (pinfunction "2_2") (pintype "passive"))
      (node (ref "R45") (pin "2") (pinfunction "2_2") (pintype "passive"))
      (node (ref "R47") (pin "2") (pinfunction "2_2") (pintype "passive"))
      (node (ref "R49") (pin "2") (pinfunction "2_2") (pintype "passive"))
      (node (ref "R5") (pin "2") (pinfunction "2_2") (pintype "passive"))
      (node (ref "R51") (pin "2") (pinfunction "2_2") (pintype "passive"))
      (node (ref "R53") (pin "2") (pinfunction "2_2") (pintype "passive"))
      (node (ref "R55") (pin "2") (pinfunction "2_2") (pintype "passive"))
      (node (ref "R57") (pin "2") (pinfunction "2_2") (pintype "passive"))
      (node (ref "R59") (pin "2") (pinfunction "2_2") (pintype "passive"))
      (node (ref "R61") (pin "2") (pinfunction "2_2") (pintype "passive"))
      (node (ref "R63") (pin "2") (pinfunction "2_2") (pintype "passive"))
      (node (ref "R65") (pin "2") (pinfunction "2_2") (pintype "passive"))
      (node (ref "R67") (pin "2") (pinfunction "2_2") (pintype "passive"))
      (node (ref "R69") (pin "2") (pinfunction "2_2") (pintype "passive"))
      (node (ref "R7") (pin "2") (pinfunction "2_2") (pintype "passive"))
      (node (ref "R71") (pin "2") (pinfunction "2_2") (pintype "passive"))
      (node (ref "R73") (pin "2") (pinfunction "2_2") (pintype "passive"))
      (node (ref "R75") (pin "2") (pinfunction "2_2") (pintype "passive"))
      (node (ref "R77") (pin "2") (pinfunction "2_2") (pintype "passive"))
      (node (ref "R79") (pin "2") (pinfunction "2_2") (pintype "passive"))
      (node (ref "R81") (pin "2") (pinfunction "2_2") (pintype "passive"))
      (node (ref "R83") (pin "2") (pinfunction "2_2") (pintype "passive"))
      (node (ref "R85") (pin "2") (pinfunction "2_2") (pintype "passive"))
      (node (ref "R87") (pin "2") (pinfunction "2_2") (pintype "passive"))
      (node (ref "R89") (pin "2") (pinfunction "2_2") (pintype "passive"))
      (node (ref "R9") (pin "2") (pinfunction "2_2") (pintype "passive"))
      (node (ref "R91") (pin "2") (pinfunction "2_2") (pintype "passive"))
      (node (ref "R93") (pin "2") (pinfunction "2_2") (pintype "passive"))
      (node (ref "R95") (pin "2") (pinfunction "2_2") (pintype "passive"))
      (node (ref "R97") (pin "2") (pinfunction "2_2") (pintype "passive"))
      (node (ref "R99") (pin "2") (pinfunction "2_2") (pintype "passive"))
      (node (ref "TP5") (pin "P$1") (pinfunction "P$1_P$1") (pintype "bidirectional"))
    )
    (net (code "2") (name "DOUT0") (class "Default")
      (node (ref "J5") (pin "2") (pinfunction "2_2") (pintype "bidirectional"))
      (node (ref "Q142") (pin "D") (pinfunction "D_D") (pintype "passive"))
      (node (ref "R250") (pin "1") (pinfunction "1_1") (pintype "passive"))
    )
    (net (code "3") (name "DOUT1") (class "Default")
      (node (ref "J5") (pin "3") (pinfunction "3_3") (pintype "bidirectional"))
      (node (ref "Q147") (pin "D") (pinfunction "D_D") (pintype "passive"))
      (node (ref "R253") (pin "1") (pinfunction "1_1") (pintype "passive"))
    )
    (net (code "4") (name "DOUT2") (class "Default")
      (node (ref "J5") (pin "4") (pinfunction "4_4") (pintype "bidirectional"))
      (node (ref "Q152") (pin "D") (pinfunction "D_D") (pintype "passive"))
      (node (ref "R254") (pin "1") (pinfunction "1_1") (pintype "passive"))
    )
    (net (code "5") (name "DOUT3") (class "Default")
      (node (ref "J5") (pin "5") (pinfunction "5_5") (pintype "bidirectional"))
      (node (ref "Q157") (pin "D") (pinfunction "D_D") (pintype "passive"))
      (node (ref "R255") (pin "1") (pinfunction "1_1") (pintype "passive"))
    )
    (net (code "6") (name "DOUT4") (class "Default")
      (node (ref "J5") (pin "6") (pinfunction "6_6") (pintype "bidirectional"))
      (node (ref "Q162") (pin "D") (pinfunction "D_D") (pintype "passive"))
      (node (ref "R256") (pin "1") (pinfunction "1_1") (pintype "passive"))
    )
    (net (code "7") (name "DOUT5") (class "Default")
      (node (ref "J5") (pin "7") (pinfunction "7_7") (pintype "bidirectional"))
      (node (ref "Q167") (pin "D") (pinfunction "D_D") (pintype "passive"))
      (node (ref "R257") (pin "1") (pinfunction "1_1") (pintype "passive"))
    )
    (net (code "8") (name "DOUT6") (class "Default")
      (node (ref "J5") (pin "8") (pinfunction "8_8") (pintype "bidirectional"))
      (node (ref "Q172") (pin "D") (pinfunction "D_D") (pintype "passive"))
      (node (ref "R258") (pin "1") (pinfunction "1_1") (pintype "passive"))
    )
    (net (code "9") (name "DOUT7") (class "Default")
      (node (ref "J5") (pin "9") (pinfunction "9_9") (pintype "bidirectional"))
      (node (ref "Q177") (pin "D") (pinfunction "D_D") (pintype "passive"))
      (node (ref "R259") (pin "1") (pinfunction "1_1") (pintype "passive"))
    )
    (net (code "10") (name "DOUT8") (class "Default")
      (node (ref "J5") (pin "12") (pinfunction "12_12") (pintype "bidirectional"))
      (node (ref "Q182") (pin "D") (pinfunction "D_D") (pintype "passive"))
      (node (ref "R260") (pin "1") (pinfunction "1_1") (pintype "passive"))
    )
    (net (code "11") (name "DOUT9") (class "Default")
      (node (ref "J5") (pin "13") (pinfunction "13_13") (pintype "bidirectional"))
      (node (ref "Q187") (pin "D") (pinfunction "D_D") (pintype "passive"))
      (node (ref "R261") (pin "1") (pinfunction "1_1") (pintype "passive"))
    )
    (net (code "12") (name "DOUT10") (class "Default")
      (node (ref "J5") (pin "14") (pinfunction "14_14") (pintype "bidirectional"))
      (node (ref "Q192") (pin "D") (pinfunction "D_D") (pintype "passive"))
      (node (ref "R262") (pin "1") (pinfunction "1_1") (pintype "passive"))
    )
    (net (code "13") (name "DOUT11") (class "Default")
      (node (ref "J5") (pin "15") (pinfunction "15_15") (pintype "bidirectional"))
      (node (ref "Q197") (pin "D") (pinfunction "D_D") (pintype "passive"))
      (node (ref "R263") (pin "1") (pinfunction "1_1") (pintype "passive"))
    )
    (net (code "14") (name "DOUT12") (class "Default")
      (node (ref "J5") (pin "16") (pinfunction "16_16") (pintype "bidirectional"))
      (node (ref "Q202") (pin "D") (pinfunction "D_D") (pintype "passive"))
      (node (ref "R264") (pin "1") (pinfunction "1_1") (pintype "passive"))
    )
    (net (code "15") (name "DOUT13") (class "Default")
      (node (ref "J5") (pin "17") (pinfunction "17_17") (pintype "bidirectional"))
      (node (ref "Q207") (pin "D") (pinfunction "D_D") (pintype "passive"))
      (node (ref "R265") (pin "1") (pinfunction "1_1") (pintype "passive"))
    )
    (net (code "16") (name "DOUT14") (class "Default")
      (node (ref "J5") (pin "18") (pinfunction "18_18") (pintype "bidirectional"))
      (node (ref "Q212") (pin "D") (pinfunction "D_D") (pintype "passive"))
      (node (ref "R266") (pin "1") (pinfunction "1_1") (pintype "passive"))
    )
    (net (code "17") (name "DOUT15") (class "Default")
      (node (ref "J5") (pin "19") (pinfunction "19_19") (pintype "bidirectional"))
      (node (ref "Q217") (pin "D") (pinfunction "D_D") (pintype "passive"))
      (node (ref "R267") (pin "1") (pinfunction "1_1") (pintype "passive"))
    )
    (net (code "18") (name "E0") (class "Default")
      (node (ref "Q10") (pin "S") (pinfunction "S_S") (pintype "passive"))
      (node (ref "Q12") (pin "S") (pinfunction "S_S") (pintype "passive"))
      (node (ref "Q131") (pin "D") (pinfunction "D_D") (pintype "passive"))
      (node (ref "Q14") (pin "S") (pinfunction "S_S") (pintype "passive"))
      (node (ref "Q16") (pin "S") (pinfunction "S_S") (pintype "passive"))
      (node (ref "Q18") (pin "S") (pinfunction "S_S") (pintype "passive"))
      (node (ref "Q2") (pin "S") (pinfunction "S_S") (pintype "passive"))
      (node (ref "Q20") (pin "S") (pinfunction "S_S") (pintype "passive"))
      (node (ref "Q22") (pin "S") (pinfunction "S_S") (pintype "passive"))
      (node (ref "Q24") (pin "S") (pinfunction "S_S") (pintype "passive"))
      (node (ref "Q26") (pin "S") (pinfunction "S_S") (pintype "passive"))
      (node (ref "Q28") (pin "S") (pinfunction "S_S") (pintype "passive"))
      (node (ref "Q30") (pin "S") (pinfunction "S_S") (pintype "passive"))
      (node (ref "Q32") (pin "S") (pinfunction "S_S") (pintype "passive"))
      (node (ref "Q4") (pin "S") (pinfunction "S_S") (pintype "passive"))
      (node (ref "Q6") (pin "S") (pinfunction "S_S") (pintype "passive"))
      (node (ref "Q8") (pin "S") (pinfunction "S_S") (pintype "passive"))
      (node (ref "R132") (pin "1") (pinfunction "1_1") (pintype "passive"))
    )
    (net (code "19") (name "E1") (class "Default")
      (node (ref "Q134") (pin "D") (pinfunction "D_D") (pintype "passive"))
      (node (ref "Q34") (pin "S") (pinfunction "S_S") (pintype "passive"))
      (node (ref "Q36") (pin "S") (pinfunction "S_S") (pintype "passive"))
      (node (ref "Q38") (pin "S") (pinfunction "S_S") (pintype "passive"))
      (node (ref "Q40") (pin "S") (pinfunction "S_S") (pintype "passive"))
      (node (ref "Q42") (pin "S") (pinfunction "S_S") (pintype "passive"))
      (node (ref "Q44") (pin "S") (pinfunction "S_S") (pintype "passive"))
      (node (ref "Q46") (pin "S") (pinfunction "S_S") (pintype "passive"))
      (node (ref "Q48") (pin "S") (pinfunction "S_S") (pintype "passive"))
      (node (ref "Q50") (pin "S") (pinfunction "S_S") (pintype "passive"))
      (node (ref "Q52") (pin "S") (pinfunction "S_S") (pintype "passive"))
      (node (ref "Q54") (pin "S") (pinfunction "S_S") (pintype "passive"))
      (node (ref "Q56") (pin "S") (pinfunction "S_S") (pintype "passive"))
      (node (ref "Q58") (pin "S") (pinfunction "S_S") (pintype "passive"))
      (node (ref "Q60") (pin "S") (pinfunction "S_S") (pintype "passive"))
      (node (ref "Q62") (pin "S") (pinfunction "S_S") (pintype "passive"))
      (node (ref "Q64") (pin "S") (pinfunction "S_S") (pintype "passive"))
      (node (ref "R136") (pin "1") (pinfunction "1_1") (pintype "passive"))
    )
    (net (code "20") (name "E2") (class "Default")
      (node (ref "Q137") (pin "D") (pinfunction "D_D") (pintype "passive"))
      (node (ref "Q66") (pin "S") (pinfunction "S_S") (pintype "passive"))
      (node (ref "Q68") (pin "S") (pinfunction "S_S") (pintype "passive"))
      (node (ref "Q70") (pin "S") (pinfunction "S_S") (pintype "passive"))
      (node (ref "Q72") (pin "S") (pinfunction "S_S") (pintype "passive"))
      (node (ref "Q74") (pin "S") (pinfunction "S_S") (pintype "passive"))
      (node (ref "Q76") (pin "S") (pinfunction "S_S") (pintype "passive"))
      (node (ref "Q78") (pin "S") (pinfunction "S_S") (pintype "passive"))
      (node (ref "Q80") (pin "S") (pinfunction "S_S") (pintype "passive"))
      (node (ref "Q82") (pin "S") (pinfunction "S_S") (pintype "passive"))
      (node (ref "Q84") (pin "S") (pinfunction "S_S") (pintype "passive"))
      (node (ref "Q86") (pin "S") (pinfunction "S_S") (pintype "passive"))
      (node (ref "Q88") (pin "S") (pinfunction "S_S") (pintype "passive"))
      (node (ref "Q90") (pin "S") (pinfunction "S_S") (pintype "passive"))
      (node (ref "Q92") (pin "S") (pinfunction "S_S") (pintype "passive"))
      (node (ref "Q94") (pin "S") (pinfunction "S_S") (pintype "passive"))
      (node (ref "Q96") (pin "S") (pinfunction "S_S") (pintype "passive"))
      (node (ref "R140") (pin "1") (pinfunction "1_1") (pintype "passive"))
    )
    (net (code "21") (name "E3") (class "Default")
      (node (ref "Q100") (pin "S") (pinfunction "S_S") (pintype "passive"))
      (node (ref "Q102") (pin "S") (pinfunction "S_S") (pintype "passive"))
      (node (ref "Q104") (pin "S") (pinfunction "S_S") (pintype "passive"))
      (node (ref "Q106") (pin "S") (pinfunction "S_S") (pintype "passive"))
      (node (ref "Q108") (pin "S") (pinfunction "S_S") (pintype "passive"))
      (node (ref "Q110") (pin "S") (pinfunction "S_S") (pintype "passive"))
      (node (ref "Q112") (pin "S") (pinfunction "S_S") (pintype "passive"))
      (node (ref "Q114") (pin "S") (pinfunction "S_S") (pintype "passive"))
      (node (ref "Q116") (pin "S") (pinfunction "S_S") (pintype "passive"))
      (node (ref "Q118") (pin "S") (pinfunction "S_S") (pintype "passive"))
      (node (ref "Q120") (pin "S") (pinfunction "S_S") (pintype "passive"))
      (node (ref "Q122") (pin "S") (pinfunction "S_S") (pintype "passive"))
      (node (ref "Q124") (pin "S") (pinfunction "S_S") (pintype "passive"))
      (node (ref "Q126") (pin "S") (pinfunction "S_S") (pintype "passive"))
      (node (ref "Q128") (pin "S") (pinfunction "S_S") (pintype "passive"))
      (node (ref "Q140") (pin "D") (pinfunction "D_D") (pintype "passive"))
      (node (ref "Q98") (pin "S") (pinfunction "S_S") (pintype "passive"))
      (node (ref "R144") (pin "1") (pinfunction "1_1") (pintype "passive"))
    )
    (net (code "22") (name "EN0_N") (class "Default")
      (node (ref "Q129") (pin "D") (pinfunction "D_D") (pintype "passive"))
      (node (ref "Q130") (pin "G") (pinfunction "G_G") (pintype "passive"))
      (node (ref "Q238") (pin "G") (pinfunction "G_G") (pintype "passive"))
      (node (ref "R129") (pin "1") (pinfunction "1_1") (pintype "passive"))
      (node (ref "R130") (pin "1") (pinfunction "1_1") (pintype "passive"))
      (node (ref "R177") (pin "1") (pinfunction "1_1") (pintype "passive"))
      (node (ref "R246") (pin "1") (pinfunction "1_1") (pintype "passive"))
    )
    (net (code "23") (name "EN1_N") (class "Default")
      (node (ref "Q132") (pin "D") (pinfunction "D_D") (pintype "passive"))
      (node (ref "Q133") (pin "G") (pinfunction "G_G") (pintype "passive"))
      (node (ref "Q239") (pin "G") (pinfunction "G_G") (pintype "passive"))
      (node (ref "R133") (pin "1") (pinfunction "1_1") (pintype "passive"))
      (node (ref "R134") (pin "1") (pinfunction "1_1") (pintype "passive"))
      (node (ref "R178") (pin "1") (pinfunction "1_1") (pintype "passive"))
      (node (ref "R247") (pin "1") (pinfunction "1_1") (pintype "passive"))
    )
    (net (code "24") (name "EN2_N") (class "Default")
      (node (ref "Q135") (pin "D") (pinfunction "D_D") (pintype "passive"))
      (node (ref "Q136") (pin "G") (pinfunction "G_G") (pintype "passive"))
      (node (ref "Q240") (pin "G") (pinfunction "G_G") (pintype "passive"))
      (node (ref "R137") (pin "1") (pinfunction "1_1") (pintype "passive"))
      (node (ref "R138") (pin "1") (pinfunction "1_1") (pintype "passive"))
      (node (ref "R179") (pin "1") (pinfunction "1_1") (pintype "passive"))
      (node (ref "R248") (pin "1") (pinfunction "1_1") (pintype "passive"))
    )
    (net (code "25") (name "EN3_N") (class "Default")
      (node (ref "Q138") (pin "D") (pinfunction "D_D") (pintype "passive"))
      (node (ref "Q139") (pin "G") (pinfunction "G_G") (pintype "passive"))
      (node (ref "Q237") (pin "G") (pinfunction "G_G") (pintype "passive"))
      (node (ref "R141") (pin "1") (pinfunction "1_1") (pintype "passive"))
      (node (ref "R142") (pin "1") (pinfunction "1_1") (pintype "passive"))
      (node (ref "R180") (pin "1") (pinfunction "1_1") (pintype "passive"))
      (node (ref "R249") (pin "1") (pinfunction "1_1") (pintype "passive"))
    )
    (net (code "26") (name "EN_0") (class "Default")
      (node (ref "Q130") (pin "D") (pinfunction "D_D") (pintype "passive"))
      (node (ref "Q131") (pin "G") (pinfunction "G_G") (pintype "passive"))
      (node (ref "R131") (pin "1") (pinfunction "1_1") (pintype "passive"))
    )
    (net (code "27") (name "EN_1") (class "Default")
      (node (ref "Q133") (pin "D") (pinfunction "D_D") (pintype "passive"))
      (node (ref "Q134") (pin "G") (pinfunction "G_G") (pintype "passive"))
      (node (ref "R135") (pin "1") (pinfunction "1_1") (pintype "passive"))
    )
    (net (code "28") (name "EN_2") (class "Default")
      (node (ref "Q136") (pin "D") (pinfunction "D_D") (pintype "passive"))
      (node (ref "Q137") (pin "G") (pinfunction "G_G") (pintype "passive"))
      (node (ref "R139") (pin "1") (pinfunction "1_1") (pintype "passive"))
    )
    (net (code "29") (name "EN_3") (class "Default")
      (node (ref "Q139") (pin "D") (pinfunction "D_D") (pintype "passive"))
      (node (ref "Q140") (pin "G") (pinfunction "G_G") (pintype "passive"))
      (node (ref "R143") (pin "1") (pinfunction "1_1") (pintype "passive"))
    )
    (net (code "30") (name "FORCE_ZERO") (class "Default")
      (node (ref "Q241") (pin "D") (pinfunction "D_D") (pintype "passive"))
      (node (ref "Q242") (pin "G") (pinfunction "G_G") (pintype "passive"))
      (node (ref "R252") (pin "1") (pinfunction "1_1") (pintype "passive"))
    )
    (net (code "31") (name "FORCE_ZERO_N") (class "Default")
      (node (ref "Q221") (pin "G") (pinfunction "G_G") (pintype "passive"))
      (node (ref "Q222") (pin "G") (pinfunction "G_G") (pintype "passive"))
      (node (ref "Q223") (pin "G") (pinfunction "G_G") (pintype "passive"))
      (node (ref "Q224") (pin "G") (pinfunction "G_G") (pintype "passive"))
      (node (ref "Q225") (pin "G") (pinfunction "G_G") (pintype "passive"))
      (node (ref "Q226") (pin "G") (pinfunction "G_G") (pintype "passive"))
      (node (ref "Q227") (pin "G") (pinfunction "G_G") (pintype "passive"))
      (node (ref "Q228") (pin "G") (pinfunction "G_G") (pintype "passive"))
      (node (ref "Q229") (pin "G") (pinfunction "G_G") (pintype "passive"))
      (node (ref "Q230") (pin "G") (pinfunction "G_G") (pintype "passive"))
      (node (ref "Q231") (pin "G") (pinfunction "G_G") (pintype "passive"))
      (node (ref "Q232") (pin "G") (pinfunction "G_G") (pintype "passive"))
      (node (ref "Q233") (pin "G") (pinfunction "G_G") (pintype "passive"))
      (node (ref "Q234") (pin "G") (pinfunction "G_G") (pintype "passive"))
      (node (ref "Q235") (pin "G") (pinfunction "G_G") (pintype "passive"))
      (node (ref "Q236") (pin "G") (pinfunction "G_G") (pintype "passive"))
      (node (ref "Q242") (pin "D") (pinfunction "D_D") (pintype "passive"))
      (node (ref "R268") (pin "1") (pinfunction "1_1") (pintype "passive"))
    )
    (net (code "32") (name "GND") (class "Default")
      (node (ref "C1") (pin "2") (pinfunction "2_2") (pintype "passive"))
      (node (ref "C2") (pin "2") (pinfunction "2_2") (pintype "passive"))
      (node (ref "C3") (pin "2") (pinfunction "2_2") (pintype "passive"))
      (node (ref "C4") (pin "2") (pinfunction "2_2") (pintype "passive"))
      (node (ref "C5") (pin "2") (pinfunction "2_2") (pintype "passive"))
      (node (ref "C6") (pin "2") (pinfunction "2_2") (pintype "passive"))
      (node (ref "C7") (pin "K") (pinfunction "K_K") (pintype "passive"))
      (node (ref "C8") (pin "2") (pinfunction "2_2") (pintype "passive"))
      (node (ref "J1") (pin "1") (pinfunction "1_1") (pintype "bidirectional"))
      (node (ref "J1") (pin "10") (pinfunction "10_10") (pintype "bidirectional"))
      (node (ref "J1") (pin "11") (pinfunction "11_11") (pintype "bidirectional"))
      (node (ref "J1") (pin "20") (pinfunction "20_20") (pintype "bidirectional"))
      (node (ref "J2") (pin "1") (pinfunction "1_1") (pintype "bidirectional"))
      (node (ref "J2") (pin "10") (pinfunction "10_10") (pintype "bidirectional"))
      (node (ref "J2") (pin "11") (pinfunction "11_11") (pintype "bidirectional"))
      (node (ref "J2") (pin "20") (pinfunction "20_20") (pintype "bidirectional"))
      (node (ref "J3") (pin "1") (pinfunction "1_1") (pintype "bidirectional"))
      (node (ref "J3") (pin "10") (pinfunction "10_10") (pintype "bidirectional"))
      (node (ref "J3") (pin "11") (pinfunction "11_11") (pintype "bidirectional"))
      (node (ref "J3") (pin "20") (pinfunction "20_20") (pintype "bidirectional"))
      (node (ref "J4") (pin "1") (pinfunction "1_1") (pintype "bidirectional"))
      (node (ref "J4") (pin "10") (pinfunction "10_10") (pintype "bidirectional"))
      (node (ref "J4") (pin "11") (pinfunction "11_11") (pintype "bidirectional"))
      (node (ref "J4") (pin "20") (pinfunction "20_20") (pintype "bidirectional"))
      (node (ref "J5") (pin "1") (pinfunction "1_1") (pintype "bidirectional"))
      (node (ref "J5") (pin "10") (pinfunction "10_10") (pintype "bidirectional"))
      (node (ref "J5") (pin "11") (pinfunction "11_11") (pintype "bidirectional"))
      (node (ref "J5") (pin "20") (pinfunction "20_20") (pintype "bidirectional"))
      (node (ref "Q1") (pin "S") (pinfunction "S_S") (pintype "passive"))
      (node (ref "Q101") (pin "S") (pinfunction "S_S") (pintype "passive"))
      (node (ref "Q103") (pin "S") (pinfunction "S_S") (pintype "passive"))
      (node (ref "Q105") (pin "S") (pinfunction "S_S") (pintype "passive"))
      (node (ref "Q107") (pin "S") (pinfunction "S_S") (pintype "passive"))
      (node (ref "Q109") (pin "S") (pinfunction "S_S") (pintype "passive"))
      (node (ref "Q11") (pin "S") (pinfunction "S_S") (pintype "passive"))
      (node (ref "Q111") (pin "S") (pinfunction "S_S") (pintype "passive"))
      (node (ref "Q113") (pin "S") (pinfunction "S_S") (pintype "passive"))
      (node (ref "Q115") (pin "S") (pinfunction "S_S") (pintype "passive"))
      (node (ref "Q117") (pin "S") (pinfunction "S_S") (pintype "passive"))
      (node (ref "Q119") (pin "S") (pinfunction "S_S") (pintype "passive"))
      (node (ref "Q121") (pin "S") (pinfunction "S_S") (pintype "passive"))
      (node (ref "Q123") (pin "S") (pinfunction "S_S") (pintype "passive"))
      (node (ref "Q125") (pin "S") (pinfunction "S_S") (pintype "passive"))
      (node (ref "Q127") (pin "S") (pinfunction "S_S") (pintype "passive"))
      (node (ref "Q129") (pin "S") (pinfunction "S_S") (pintype "passive"))
      (node (ref "Q13") (pin "S") (pinfunction "S_S") (pintype "passive"))
      (node (ref "Q130") (pin "S") (pinfunction "S_S") (pintype "passive"))
      (node (ref "Q131") (pin "S") (pinfunction "S_S") (pintype "passive"))
      (node (ref "Q132") (pin "S") (pinfunction "S_S") (pintype "passive"))
      (node (ref "Q133") (pin "S") (pinfunction "S_S") (pintype "passive"))
      (node (ref "Q134") (pin "S") (pinfunction "S_S") (pintype "passive"))
      (node (ref "Q135") (pin "S") (pinfunction "S_S") (pintype "passive"))
      (node (ref "Q136") (pin "S") (pinfunction "S_S") (pintype "passive"))
      (node (ref "Q137") (pin "S") (pinfunction "S_S") (pintype "passive"))
      (node (ref "Q138") (pin "S") (pinfunction "S_S") (pintype "passive"))
      (node (ref "Q139") (pin "S") (pinfunction "S_S") (pintype "passive"))
      (node (ref "Q140") (pin "S") (pinfunction "S_S") (pintype "passive"))
      (node (ref "Q142") (pin "S") (pinfunction "S_S") (pintype "passive"))
      (node (ref "Q145") (pin "S") (pinfunction "S_S") (pintype "passive"))
      (node (ref "Q147") (pin "S") (pinfunction "S_S") (pintype "passive"))
      (node (ref "Q15") (pin "S") (pinfunction "S_S") (pintype "passive"))
      (node (ref "Q150") (pin "S") (pinfunction "S_S") (pintype "passive"))
      (node (ref "Q152") (pin "S") (pinfunction "S_S") (pintype "passive"))
      (node (ref "Q155") (pin "S") (pinfunction "S_S") (pintype "passive"))
      (node (ref "Q157") (pin "S") (pinfunction "S_S") (pintype "passive"))
      (node (ref "Q160") (pin "S") (pinfunction "S_S") (pintype "passive"))
      (node (ref "Q162") (pin "S") (pinfunction "S_S") (pintype "passive"))
      (node (ref "Q165") (pin "S") (pinfunction "S_S") (pintype "passive"))
      (node (ref "Q167") (pin "S") (pinfunction "S_S") (pintype "passive"))
      (node (ref "Q17") (pin "S") (pinfunction "S_S") (pintype "passive"))
      (node (ref "Q170") (pin "S") (pinfunction "S_S") (pintype "passive"))
      (node (ref "Q172") (pin "S") (pinfunction "S_S") (pintype "passive"))
      (node (ref "Q175") (pin "S") (pinfunction "S_S") (pintype "passive"))
      (node (ref "Q177") (pin "S") (pinfunction "S_S") (pintype "passive"))
      (node (ref "Q180") (pin "S") (pinfunction "S_S") (pintype "passive"))
      (node (ref "Q182") (pin "S") (pinfunction "S_S") (pintype "passive"))
      (node (ref "Q185") (pin "S") (pinfunction "S_S") (pintype "passive"))
      (node (ref "Q187") (pin "S") (pinfunction "S_S") (pintype "passive"))
      (node (ref "Q19") (pin "S") (pinfunction "S_S") (pintype "passive"))
      (node (ref "Q190") (pin "S") (pinfunction "S_S") (pintype "passive"))
      (node (ref "Q192") (pin "S") (pinfunction "S_S") (pintype "passive"))
      (node (ref "Q195") (pin "S") (pinfunction "S_S") (pintype "passive"))
      (node (ref "Q197") (pin "S") (pinfunction "S_S") (pintype "passive"))
      (node (ref "Q200") (pin "S") (pinfunction "S_S") (pintype "passive"))
      (node (ref "Q202") (pin "S") (pinfunction "S_S") (pintype "passive"))
      (node (ref "Q205") (pin "S") (pinfunction "S_S") (pintype "passive"))
      (node (ref "Q207") (pin "S") (pinfunction "S_S") (pintype "passive"))
      (node (ref "Q21") (pin "S") (pinfunction "S_S") (pintype "passive"))
      (node (ref "Q210") (pin "S") (pinfunction "S_S") (pintype "passive"))
      (node (ref "Q212") (pin "S") (pinfunction "S_S") (pintype "passive"))
      (node (ref "Q215") (pin "S") (pinfunction "S_S") (pintype "passive"))
      (node (ref "Q217") (pin "S") (pinfunction "S_S") (pintype "passive"))
      (node (ref "Q220") (pin "S") (pinfunction "S_S") (pintype "passive"))
      (node (ref "Q23") (pin "S") (pinfunction "S_S") (pintype "passive"))
      (node (ref "Q237") (pin "S") (pinfunction "S_S") (pintype "passive"))
      (node (ref "Q241") (pin "S") (pinfunction "S_S") (pintype "passive"))
      (node (ref "Q242") (pin "S") (pinfunction "S_S") (pintype "passive"))
      (node (ref "Q25") (pin "S") (pinfunction "S_S") (pintype "passive"))
      (node (ref "Q27") (pin "S") (pinfunction "S_S") (pintype "passive"))
      (node (ref "Q29") (pin "S") (pinfunction "S_S") (pintype "passive"))
      (node (ref "Q3") (pin "S") (pinfunction "S_S") (pintype "passive"))
      (node (ref "Q31") (pin "S") (pinfunction "S_S") (pintype "passive"))
      (node (ref "Q33") (pin "S") (pinfunction "S_S") (pintype "passive"))
      (node (ref "Q35") (pin "S") (pinfunction "S_S") (pintype "passive"))
      (node (ref "Q37") (pin "S") (pinfunction "S_S") (pintype "passive"))
      (node (ref "Q39") (pin "S") (pinfunction "S_S") (pintype "passive"))
      (node (ref "Q41") (pin "S") (pinfunction "S_S") (pintype "passive"))
      (node (ref "Q43") (pin "S") (pinfunction "S_S") (pintype "passive"))
      (node (ref "Q45") (pin "S") (pinfunction "S_S") (pintype "passive"))
      (node (ref "Q47") (pin "S") (pinfunction "S_S") (pintype "passive"))
      (node (ref "Q49") (pin "S") (pinfunction "S_S") (pintype "passive"))
      (node (ref "Q5") (pin "S") (pinfunction "S_S") (pintype "passive"))
      (node (ref "Q51") (pin "S") (pinfunction "S_S") (pintype "passive"))
      (node (ref "Q53") (pin "S") (pinfunction "S_S") (pintype "passive"))
      (node (ref "Q55") (pin "S") (pinfunction "S_S") (pintype "passive"))
      (node (ref "Q57") (pin "S") (pinfunction "S_S") (pintype "passive"))
      (node (ref "Q59") (pin "S") (pinfunction "S_S") (pintype "passive"))
      (node (ref "Q61") (pin "S") (pinfunction "S_S") (pintype "passive"))
      (node (ref "Q63") (pin "S") (pinfunction "S_S") (pintype "passive"))
      (node (ref "Q65") (pin "S") (pinfunction "S_S") (pintype "passive"))
      (node (ref "Q67") (pin "S") (pinfunction "S_S") (pintype "passive"))
      (node (ref "Q69") (pin "S") (pinfunction "S_S") (pintype "passive"))
      (node (ref "Q7") (pin "S") (pinfunction "S_S") (pintype "passive"))
      (node (ref "Q71") (pin "S") (pinfunction "S_S") (pintype "passive"))
      (node (ref "Q73") (pin "S") (pinfunction "S_S") (pintype "passive"))
      (node (ref "Q75") (pin "S") (pinfunction "S_S") (pintype "passive"))
      (node (ref "Q77") (pin "S") (pinfunction "S_S") (pintype "passive"))
      (node (ref "Q79") (pin "S") (pinfunction "S_S") (pintype "passive"))
      (node (ref "Q81") (pin "S") (pinfunction "S_S") (pintype "passive"))
      (node (ref "Q83") (pin "S") (pinfunction "S_S") (pintype "passive"))
      (node (ref "Q85") (pin "S") (pinfunction "S_S") (pintype "passive"))
      (node (ref "Q87") (pin "S") (pinfunction "S_S") (pintype "passive"))
      (node (ref "Q89") (pin "S") (pinfunction "S_S") (pintype "passive"))
      (node (ref "Q9") (pin "S") (pinfunction "S_S") (pintype "passive"))
      (node (ref "Q91") (pin "S") (pinfunction "S_S") (pintype "passive"))
      (node (ref "Q93") (pin "S") (pinfunction "S_S") (pintype "passive"))
      (node (ref "Q95") (pin "S") (pinfunction "S_S") (pintype "passive"))
      (node (ref "Q97") (pin "S") (pinfunction "S_S") (pintype "passive"))
      (node (ref "Q99") (pin "S") (pinfunction "S_S") (pintype "passive"))
      (node (ref "TP6") (pin "P$1") (pinfunction "P$1_P$1") (pintype "bidirectional"))
    )
    (net (code "33") (name "Net-(D1-C)") (class "Default")
      (node (ref "D1") (pin "K") (pinfunction "C_K") (pintype "passive"))
      (node (ref "R2") (pin "2") (pinfunction "2_2") (pintype "passive"))
    )
    (net (code "34") (name "Net-(D2-C)") (class "Default")
      (node (ref "D2") (pin "K") (pinfunction "C_K") (pintype "passive"))
      (node (ref "R4") (pin "2") (pinfunction "2_2") (pintype "passive"))
    )
    (net (code "35") (name "Net-(D3-C)") (class "Default")
      (node (ref "D3") (pin "K") (pinfunction "C_K") (pintype "passive"))
      (node (ref "R6") (pin "2") (pinfunction "2_2") (pintype "passive"))
    )
    (net (code "36") (name "Net-(D4-C)") (class "Default")
      (node (ref "D4") (pin "K") (pinfunction "C_K") (pintype "passive"))
      (node (ref "R8") (pin "2") (pinfunction "2_2") (pintype "passive"))
    )
    (net (code "37") (name "Net-(D5-C)") (class "Default")
      (node (ref "D5") (pin "K") (pinfunction "C_K") (pintype "passive"))
      (node (ref "R10") (pin "2") (pinfunction "2_2") (pintype "passive"))
    )
    (net (code "38") (name "Net-(D6-C)") (class "Default")
      (node (ref "D6") (pin "K") (pinfunction "C_K") (pintype "passive"))
      (node (ref "R12") (pin "2") (pinfunction "2_2") (pintype "passive"))
    )
    (net (code "39") (name "Net-(D7-C)") (class "Default")
      (node (ref "D7") (pin "K") (pinfunction "C_K") (pintype "passive"))
      (node (ref "R14") (pin "2") (pinfunction "2_2") (pintype "passive"))
    )
    (net (code "40") (name "Net-(D8-C)") (class "Default")
      (node (ref "D8") (pin "K") (pinfunction "C_K") (pintype "passive"))
      (node (ref "R16") (pin "2") (pinfunction "2_2") (pintype "passive"))
    )
    (net (code "41") (name "Net-(D9-C)") (class "Default")
      (node (ref "D9") (pin "K") (pinfunction "C_K") (pintype "passive"))
      (node (ref "R18") (pin "2") (pinfunction "2_2") (pintype "passive"))
    )
    (net (code "42") (name "Net-(D10-C)") (class "Default")
      (node (ref "D10") (pin "K") (pinfunction "C_K") (pintype "passive"))
      (node (ref "R20") (pin "2") (pinfunction "2_2") (pintype "passive"))
    )
    (net (code "43") (name "Net-(D11-C)") (class "Default")
      (node (ref "D11") (pin "K") (pinfunction "C_K") (pintype "passive"))
      (node (ref "R22") (pin "2") (pinfunction "2_2") (pintype "passive"))
    )
    (net (code "44") (name "Net-(D12-C)") (class "Default")
      (node (ref "D12") (pin "K") (pinfunction "C_K") (pintype "passive"))
      (node (ref "R24") (pin "2") (pinfunction "2_2") (pintype "passive"))
    )
    (net (code "45") (name "Net-(D13-C)") (class "Default")
      (node (ref "D13") (pin "K") (pinfunction "C_K") (pintype "passive"))
      (node (ref "R26") (pin "2") (pinfunction "2_2") (pintype "passive"))
    )
    (net (code "46") (name "Net-(D14-C)") (class "Default")
      (node (ref "D14") (pin "K") (pinfunction "C_K") (pintype "passive"))
      (node (ref "R28") (pin "2") (pinfunction "2_2") (pintype "passive"))
    )
    (net (code "47") (name "Net-(D15-C)") (class "Default")
      (node (ref "D15") (pin "K") (pinfunction "C_K") (pintype "passive"))
      (node (ref "R30") (pin "2") (pinfunction "2_2") (pintype "passive"))
    )
    (net (code "48") (name "Net-(D16-C)") (class "Default")
      (node (ref "D16") (pin "K") (pinfunction "C_K") (pintype "passive"))
      (node (ref "R32") (pin "2") (pinfunction "2_2") (pintype "passive"))
    )
    (net (code "49") (name "Net-(D17-C)") (class "Default")
      (node (ref "D17") (pin "K") (pinfunction "C_K") (pintype "passive"))
      (node (ref "R34") (pin "2") (pinfunction "2_2") (pintype "passive"))
    )
    (net (code "50") (name "Net-(D18-C)") (class "Default")
      (node (ref "D18") (pin "K") (pinfunction "C_K") (pintype "passive"))
      (node (ref "R36") (pin "2") (pinfunction "2_2") (pintype "passive"))
    )
    (net (code "51") (name "Net-(D19-C)") (class "Default")
      (node (ref "D19") (pin "K") (pinfunction "C_K") (pintype "passive"))
      (node (ref "R38") (pin "2") (pinfunction "2_2") (pintype "passive"))
    )
    (net (code "52") (name "Net-(D20-C)") (class "Default")
      (node (ref "D20") (pin "K") (pinfunction "C_K") (pintype "passive"))
      (node (ref "R40") (pin "2") (pinfunction "2_2") (pintype "passive"))
    )
    (net (code "53") (name "Net-(D21-C)") (class "Default")
      (node (ref "D21") (pin "K") (pinfunction "C_K") (pintype "passive"))
      (node (ref "R42") (pin "2") (pinfunction "2_2") (pintype "passive"))
    )
    (net (code "54") (name "Net-(D22-C)") (class "Default")
      (node (ref "D22") (pin "K") (pinfunction "C_K") (pintype "passive"))
      (node (ref "R44") (pin "2") (pinfunction "2_2") (pintype "passive"))
    )
    (net (code "55") (name "Net-(D23-C)") (class "Default")
      (node (ref "D23") (pin "K") (pinfunction "C_K") (pintype "passive"))
      (node (ref "R46") (pin "2") (pinfunction "2_2") (pintype "passive"))
    )
    (net (code "56") (name "Net-(D24-C)") (class "Default")
      (node (ref "D24") (pin "K") (pinfunction "C_K") (pintype "passive"))
      (node (ref "R48") (pin "2") (pinfunction "2_2") (pintype "passive"))
    )
    (net (code "57") (name "Net-(D25-C)") (class "Default")
      (node (ref "D25") (pin "K") (pinfunction "C_K") (pintype "passive"))
      (node (ref "R50") (pin "2") (pinfunction "2_2") (pintype "passive"))
    )
    (net (code "58") (name "Net-(D26-C)") (class "Default")
      (node (ref "D26") (pin "K") (pinfunction "C_K") (pintype "passive"))
      (node (ref "R52") (pin "2") (pinfunction "2_2") (pintype "passive"))
    )
    (net (code "59") (name "Net-(D27-C)") (class "Default")
      (node (ref "D27") (pin "K") (pinfunction "C_K") (pintype "passive"))
      (node (ref "R54") (pin "2") (pinfunction "2_2") (pintype "passive"))
    )
    (net (code "60") (name "Net-(D28-C)") (class "Default")
      (node (ref "D28") (pin "K") (pinfunction "C_K") (pintype "passive"))
      (node (ref "R56") (pin "2") (pinfunction "2_2") (pintype "passive"))
    )
    (net (code "61") (name "Net-(D29-C)") (class "Default")
      (node (ref "D29") (pin "K") (pinfunction "C_K") (pintype "passive"))
      (node (ref "R58") (pin "2") (pinfunction "2_2") (pintype "passive"))
    )
    (net (code "62") (name "Net-(D30-C)") (class "Default")
      (node (ref "D30") (pin "K") (pinfunction "C_K") (pintype "passive"))
      (node (ref "R60") (pin "2") (pinfunction "2_2") (pintype "passive"))
    )
    (net (code "63") (name "Net-(D31-C)") (class "Default")
      (node (ref "D31") (pin "K") (pinfunction "C_K") (pintype "passive"))
      (node (ref "R62") (pin "2") (pinfunction "2_2") (pintype "passive"))
    )
    (net (code "64") (name "Net-(D32-C)") (class "Default")
      (node (ref "D32") (pin "K") (pinfunction "C_K") (pintype "passive"))
      (node (ref "R64") (pin "2") (pinfunction "2_2") (pintype "passive"))
    )
    (net (code "65") (name "Net-(D33-C)") (class "Default")
      (node (ref "D33") (pin "K") (pinfunction "C_K") (pintype "passive"))
      (node (ref "R66") (pin "2") (pinfunction "2_2") (pintype "passive"))
    )
    (net (code "66") (name "Net-(D34-C)") (class "Default")
      (node (ref "D34") (pin "K") (pinfunction "C_K") (pintype "passive"))
      (node (ref "R68") (pin "2") (pinfunction "2_2") (pintype "passive"))
    )
    (net (code "67") (name "Net-(D35-C)") (class "Default")
      (node (ref "D35") (pin "K") (pinfunction "C_K") (pintype "passive"))
      (node (ref "R70") (pin "2") (pinfunction "2_2") (pintype "passive"))
    )
    (net (code "68") (name "Net-(D36-C)") (class "Default")
      (node (ref "D36") (pin "K") (pinfunction "C_K") (pintype "passive"))
      (node (ref "R72") (pin "2") (pinfunction "2_2") (pintype "passive"))
    )
    (net (code "69") (name "Net-(D37-C)") (class "Default")
      (node (ref "D37") (pin "K") (pinfunction "C_K") (pintype "passive"))
      (node (ref "R74") (pin "2") (pinfunction "2_2") (pintype "passive"))
    )
    (net (code "70") (name "Net-(D38-C)") (class "Default")
      (node (ref "D38") (pin "K") (pinfunction "C_K") (pintype "passive"))
      (node (ref "R76") (pin "2") (pinfunction "2_2") (pintype "passive"))
    )
    (net (code "71") (name "Net-(D39-C)") (class "Default")
      (node (ref "D39") (pin "K") (pinfunction "C_K") (pintype "passive"))
      (node (ref "R78") (pin "2") (pinfunction "2_2") (pintype "passive"))
    )
    (net (code "72") (name "Net-(D40-C)") (class "Default")
      (node (ref "D40") (pin "K") (pinfunction "C_K") (pintype "passive"))
      (node (ref "R80") (pin "2") (pinfunction "2_2") (pintype "passive"))
    )
    (net (code "73") (name "Net-(D41-C)") (class "Default")
      (node (ref "D41") (pin "K") (pinfunction "C_K") (pintype "passive"))
      (node (ref "R82") (pin "2") (pinfunction "2_2") (pintype "passive"))
    )
    (net (code "74") (name "Net-(D42-C)") (class "Default")
      (node (ref "D42") (pin "K") (pinfunction "C_K") (pintype "passive"))
      (node (ref "R84") (pin "2") (pinfunction "2_2") (pintype "passive"))
    )
    (net (code "75") (name "Net-(D43-C)") (class "Default")
      (node (ref "D43") (pin "K") (pinfunction "C_K") (pintype "passive"))
      (node (ref "R86") (pin "2") (pinfunction "2_2") (pintype "passive"))
    )
    (net (code "76") (name "Net-(D44-C)") (class "Default")
      (node (ref "D44") (pin "K") (pinfunction "C_K") (pintype "passive"))
      (node (ref "R88") (pin "2") (pinfunction "2_2") (pintype "passive"))
    )
    (net (code "77") (name "Net-(D45-C)") (class "Default")
      (node (ref "D45") (pin "K") (pinfunction "C_K") (pintype "passive"))
      (node (ref "R90") (pin "2") (pinfunction "2_2") (pintype "passive"))
    )
    (net (code "78") (name "Net-(D46-C)") (class "Default")
      (node (ref "D46") (pin "K") (pinfunction "C_K") (pintype "passive"))
      (node (ref "R92") (pin "2") (pinfunction "2_2") (pintype "passive"))
    )
    (net (code "79") (name "Net-(D47-C)") (class "Default")
      (node (ref "D47") (pin "K") (pinfunction "C_K") (pintype "passive"))
      (node (ref "R94") (pin "2") (pinfunction "2_2") (pintype "passive"))
    )
    (net (code "80") (name "Net-(D48-C)") (class "Default")
      (node (ref "D48") (pin "K") (pinfunction "C_K") (pintype "passive"))
      (node (ref "R96") (pin "2") (pinfunction "2_2") (pintype "passive"))
    )
    (net (code "81") (name "Net-(D49-C)") (class "Default")
      (node (ref "D49") (pin "K") (pinfunction "C_K") (pintype "passive"))
      (node (ref "R98") (pin "2") (pinfunction "2_2") (pintype "passive"))
    )
    (net (code "82") (name "Net-(D50-C)") (class "Default")
      (node (ref "D50") (pin "K") (pinfunction "C_K") (pintype "passive"))
      (node (ref "R100") (pin "2") (pinfunction "2_2") (pintype "passive"))
    )
    (net (code "83") (name "Net-(D51-C)") (class "Default")
      (node (ref "D51") (pin "K") (pinfunction "C_K") (pintype "passive"))
      (node (ref "R102") (pin "2") (pinfunction "2_2") (pintype "passive"))
    )
    (net (code "84") (name "Net-(D52-C)") (class "Default")
      (node (ref "D52") (pin "K") (pinfunction "C_K") (pintype "passive"))
      (node (ref "R104") (pin "2") (pinfunction "2_2") (pintype "passive"))
    )
    (net (code "85") (name "Net-(D53-C)") (class "Default")
      (node (ref "D53") (pin "K") (pinfunction "C_K") (pintype "passive"))
      (node (ref "R106") (pin "2") (pinfunction "2_2") (pintype "passive"))
    )
    (net (code "86") (name "Net-(D54-C)") (class "Default")
      (node (ref "D54") (pin "K") (pinfunction "C_K") (pintype "passive"))
      (node (ref "R108") (pin "2") (pinfunction "2_2") (pintype "passive"))
    )
    (net (code "87") (name "Net-(D55-C)") (class "Default")
      (node (ref "D55") (pin "K") (pinfunction "C_K") (pintype "passive"))
      (node (ref "R110") (pin "2") (pinfunction "2_2") (pintype "passive"))
    )
    (net (code "88") (name "Net-(D56-C)") (class "Default")
      (node (ref "D56") (pin "K") (pinfunction "C_K") (pintype "passive"))
      (node (ref "R112") (pin "2") (pinfunction "2_2") (pintype "passive"))
    )
    (net (code "89") (name "Net-(D57-C)") (class "Default")
      (node (ref "D57") (pin "K") (pinfunction "C_K") (pintype "passive"))
      (node (ref "R114") (pin "2") (pinfunction "2_2") (pintype "passive"))
    )
    (net (code "90") (name "Net-(D58-C)") (class "Default")
      (node (ref "D58") (pin "K") (pinfunction "C_K") (pintype "passive"))
      (node (ref "R116") (pin "2") (pinfunction "2_2") (pintype "passive"))
    )
    (net (code "91") (name "Net-(D59-C)") (class "Default")
      (node (ref "D59") (pin "K") (pinfunction "C_K") (pintype "passive"))
      (node (ref "R118") (pin "2") (pinfunction "2_2") (pintype "passive"))
    )
    (net (code "92") (name "Net-(D60-C)") (class "Default")
      (node (ref "D60") (pin "K") (pinfunction "C_K") (pintype "passive"))
      (node (ref "R120") (pin "2") (pinfunction "2_2") (pintype "passive"))
    )
    (net (code "93") (name "Net-(D61-C)") (class "Default")
      (node (ref "D61") (pin "K") (pinfunction "C_K") (pintype "passive"))
      (node (ref "R122") (pin "2") (pinfunction "2_2") (pintype "passive"))
    )
    (net (code "94") (name "Net-(D62-C)") (class "Default")
      (node (ref "D62") (pin "K") (pinfunction "C_K") (pintype "passive"))
      (node (ref "R124") (pin "2") (pinfunction "2_2") (pintype "passive"))
    )
    (net (code "95") (name "Net-(D63-C)") (class "Default")
      (node (ref "D63") (pin "K") (pinfunction "C_K") (pintype "passive"))
      (node (ref "R126") (pin "2") (pinfunction "2_2") (pintype "passive"))
    )
    (net (code "96") (name "Net-(D64-C)") (class "Default")
      (node (ref "D64") (pin "K") (pinfunction "C_K") (pintype "passive"))
      (node (ref "R128") (pin "2") (pinfunction "2_2") (pintype "passive"))
    )
    (net (code "97") (name "Net-(D65-C)") (class "Default")
      (node (ref "D65") (pin "K") (pinfunction "C_K") (pintype "passive"))
      (node (ref "R130") (pin "2") (pinfunction "2_2") (pintype "passive"))
    )
    (net (code "98") (name "Net-(D66-C)") (class "Default")
      (node (ref "D66") (pin "K") (pinfunction "C_K") (pintype "passive"))
      (node (ref "R134") (pin "2") (pinfunction "2_2") (pintype "passive"))
    )
    (net (code "99") (name "Net-(D67-C)") (class "Default")
      (node (ref "D67") (pin "K") (pinfunction "C_K") (pintype "passive"))
      (node (ref "R138") (pin "2") (pinfunction "2_2") (pintype "passive"))
    )
    (net (code "100") (name "Net-(D68-C)") (class "Default")
      (node (ref "D68") (pin "K") (pinfunction "C_K") (pintype "passive"))
      (node (ref "R142") (pin "2") (pinfunction "2_2") (pintype "passive"))
    )
    (net (code "101") (name "Net-(D69-C)") (class "Default")
      (node (ref "D69") (pin "K") (pinfunction "C_K") (pintype "passive"))
      (node (ref "R146") (pin "2") (pinfunction "2_2") (pintype "passive"))
    )
    (net (code "102") (name "Net-(D70-C)") (class "Default")
      (node (ref "D70") (pin "K") (pinfunction "C_K") (pintype "passive"))
      (node (ref "R148") (pin "2") (pinfunction "2_2") (pintype "passive"))
    )
    (net (code "103") (name "Net-(D71-C)") (class "Default")
      (node (ref "D71") (pin "K") (pinfunction "C_K") (pintype "passive"))
      (node (ref "R150") (pin "2") (pinfunction "2_2") (pintype "passive"))
    )
    (net (code "104") (name "Net-(D72-C)") (class "Default")
      (node (ref "D72") (pin "K") (pinfunction "C_K") (pintype "passive"))
      (node (ref "R152") (pin "2") (pinfunction "2_2") (pintype "passive"))
    )
    (net (code "105") (name "Net-(D73-C)") (class "Default")
      (node (ref "D73") (pin "K") (pinfunction "C_K") (pintype "passive"))
      (node (ref "R154") (pin "2") (pinfunction "2_2") (pintype "passive"))
    )
    (net (code "106") (name "Net-(D74-C)") (class "Default")
      (node (ref "D74") (pin "K") (pinfunction "C_K") (pintype "passive"))
      (node (ref "R156") (pin "2") (pinfunction "2_2") (pintype "passive"))
    )
    (net (code "107") (name "Net-(D75-C)") (class "Default")
      (node (ref "D75") (pin "K") (pinfunction "C_K") (pintype "passive"))
      (node (ref "R158") (pin "2") (pinfunction "2_2") (pintype "passive"))
    )
    (net (code "108") (name "Net-(D76-C)") (class "Default")
      (node (ref "D76") (pin "K") (pinfunction "C_K") (pintype "passive"))
      (node (ref "R160") (pin "2") (pinfunction "2_2") (pintype "passive"))
    )
    (net (code "109") (name "Net-(D77-C)") (class "Default")
      (node (ref "D77") (pin "K") (pinfunction "C_K") (pintype "passive"))
      (node (ref "R162") (pin "2") (pinfunction "2_2") (pintype "passive"))
    )
    (net (code "110") (name "Net-(D78-C)") (class "Default")
      (node (ref "D78") (pin "K") (pinfunction "C_K") (pintype "passive"))
      (node (ref "R164") (pin "2") (pinfunction "2_2") (pintype "passive"))
    )
    (net (code "111") (name "Net-(D79-C)") (class "Default")
      (node (ref "D79") (pin "K") (pinfunction "C_K") (pintype "passive"))
      (node (ref "R166") (pin "2") (pinfunction "2_2") (pintype "passive"))
    )
    (net (code "112") (name "Net-(D80-C)") (class "Default")
      (node (ref "D80") (pin "K") (pinfunction "C_K") (pintype "passive"))
      (node (ref "R168") (pin "2") (pinfunction "2_2") (pintype "passive"))
    )
    (net (code "113") (name "Net-(D81-C)") (class "Default")
      (node (ref "D81") (pin "K") (pinfunction "C_K") (pintype "passive"))
      (node (ref "R170") (pin "2") (pinfunction "2_2") (pintype "passive"))
    )
    (net (code "114") (name "Net-(D82-C)") (class "Default")
      (node (ref "D82") (pin "K") (pinfunction "C_K") (pintype "passive"))
      (node (ref "R172") (pin "2") (pinfunction "2_2") (pintype "passive"))
    )
    (net (code "115") (name "Net-(D83-C)") (class "Default")
      (node (ref "D83") (pin "K") (pinfunction "C_K") (pintype "passive"))
      (node (ref "R174") (pin "2") (pinfunction "2_2") (pintype "passive"))
    )
    (net (code "116") (name "Net-(D84-C)") (class "Default")
      (node (ref "D84") (pin "K") (pinfunction "C_K") (pintype "passive"))
      (node (ref "R176") (pin "2") (pinfunction "2_2") (pintype "passive"))
    )
    (net (code "117") (name "Net-(D85-C)") (class "Default")
      (node (ref "D85") (pin "K") (pinfunction "C_K") (pintype "passive"))
      (node (ref "R177") (pin "2") (pinfunction "2_2") (pintype "passive"))
    )
    (net (code "118") (name "Net-(D86-C)") (class "Default")
      (node (ref "D86") (pin "K") (pinfunction "C_K") (pintype "passive"))
      (node (ref "R178") (pin "2") (pinfunction "2_2") (pintype "passive"))
    )
    (net (code "119") (name "Net-(D87-C)") (class "Default")
      (node (ref "D87") (pin "K") (pinfunction "C_K") (pintype "passive"))
      (node (ref "R179") (pin "2") (pinfunction "2_2") (pintype "passive"))
    )
    (net (code "120") (name "Net-(D88-C)") (class "Default")
      (node (ref "D88") (pin "K") (pinfunction "C_K") (pintype "passive"))
      (node (ref "R180") (pin "2") (pinfunction "2_2") (pintype "passive"))
    )
    (net (code "121") (name "Net-(D89-C)") (class "Default")
      (node (ref "D89") (pin "K") (pinfunction "C_K") (pintype "passive"))
      (node (ref "R246") (pin "2") (pinfunction "2_2") (pintype "passive"))
    )
    (net (code "122") (name "Net-(D90-C)") (class "Default")
      (node (ref "D90") (pin "K") (pinfunction "C_K") (pintype "passive"))
      (node (ref "R247") (pin "2") (pinfunction "2_2") (pintype "passive"))
    )
    (net (code "123") (name "Net-(D91-C)") (class "Default")
      (node (ref "D91") (pin "K") (pinfunction "C_K") (pintype "passive"))
      (node (ref "R248") (pin "2") (pinfunction "2_2") (pintype "passive"))
    )
    (net (code "124") (name "Net-(D92-C)") (class "Default")
      (node (ref "D92") (pin "K") (pinfunction "C_K") (pintype "passive"))
      (node (ref "R249") (pin "2") (pinfunction "2_2") (pintype "passive"))
    )
    (net (code "125") (name "Net-(D93-C)") (class "Default")
      (node (ref "D93") (pin "K") (pinfunction "C_K") (pintype "passive"))
      (node (ref "Q238") (pin "D") (pinfunction "D_D") (pintype "passive"))
      (node (ref "Q241") (pin "G") (pinfunction "G_G") (pintype "passive"))
      (node (ref "R245") (pin "1") (pinfunction "1_1") (pintype "passive"))
    )
    (net (code "126") (name "Net-(D93-PadA)") (class "Default")
      (node (ref "D93") (pin "A") (pinfunction "A_A") (pintype "passive"))
      (node (ref "R251") (pin "1") (pinfunction "1_1") (pintype "passive"))
    )
    (net (code "127") (name "Net-(Q1-PadD)") (class "Default")
      (node (ref "Q1") (pin "D") (pinfunction "D_D") (pintype "passive"))
      (node (ref "Q2") (pin "G") (pinfunction "G_G") (pintype "passive"))
      (node (ref "R1") (pin "1") (pinfunction "1_1") (pintype "passive"))
      (node (ref "R2") (pin "1") (pinfunction "1_1") (pintype "passive"))
    )
    (net (code "128") (name "Net-(Q3-PadD)") (class "Default")
      (node (ref "Q3") (pin "D") (pinfunction "D_D") (pintype "passive"))
      (node (ref "Q4") (pin "G") (pinfunction "G_G") (pintype "passive"))
      (node (ref "R3") (pin "1") (pinfunction "1_1") (pintype "passive"))
      (node (ref "R4") (pin "1") (pinfunction "1_1") (pintype "passive"))
    )
    (net (code "129") (name "Net-(Q5-PadD)") (class "Default")
      (node (ref "Q5") (pin "D") (pinfunction "D_D") (pintype "passive"))
      (node (ref "Q6") (pin "G") (pinfunction "G_G") (pintype "passive"))
      (node (ref "R5") (pin "1") (pinfunction "1_1") (pintype "passive"))
      (node (ref "R6") (pin "1") (pinfunction "1_1") (pintype "passive"))
    )
    (net (code "130") (name "Net-(Q7-PadD)") (class "Default")
      (node (ref "Q7") (pin "D") (pinfunction "D_D") (pintype "passive"))
      (node (ref "Q8") (pin "G") (pinfunction "G_G") (pintype "passive"))
      (node (ref "R7") (pin "1") (pinfunction "1_1") (pintype "passive"))
      (node (ref "R8") (pin "1") (pinfunction "1_1") (pintype "passive"))
    )
    (net (code "131") (name "Net-(Q10-PadG)") (class "Default")
      (node (ref "Q10") (pin "G") (pinfunction "G_G") (pintype "passive"))
      (node (ref "Q9") (pin "D") (pinfunction "D_D") (pintype "passive"))
      (node (ref "R10") (pin "1") (pinfunction "1_1") (pintype "passive"))
      (node (ref "R9") (pin "1") (pinfunction "1_1") (pintype "passive"))
    )
    (net (code "132") (name "Net-(Q11-PadD)") (class "Default")
      (node (ref "Q11") (pin "D") (pinfunction "D_D") (pintype "passive"))
      (node (ref "Q12") (pin "G") (pinfunction "G_G") (pintype "passive"))
      (node (ref "R11") (pin "1") (pinfunction "1_1") (pintype "passive"))
      (node (ref "R12") (pin "1") (pinfunction "1_1") (pintype "passive"))
    )
    (net (code "133") (name "Net-(Q13-PadD)") (class "Default")
      (node (ref "Q13") (pin "D") (pinfunction "D_D") (pintype "passive"))
      (node (ref "Q14") (pin "G") (pinfunction "G_G") (pintype "passive"))
      (node (ref "R13") (pin "1") (pinfunction "1_1") (pintype "passive"))
      (node (ref "R14") (pin "1") (pinfunction "1_1") (pintype "passive"))
    )
    (net (code "134") (name "Net-(Q15-PadD)") (class "Default")
      (node (ref "Q15") (pin "D") (pinfunction "D_D") (pintype "passive"))
      (node (ref "Q16") (pin "G") (pinfunction "G_G") (pintype "passive"))
      (node (ref "R15") (pin "1") (pinfunction "1_1") (pintype "passive"))
      (node (ref "R16") (pin "1") (pinfunction "1_1") (pintype "passive"))
    )
    (net (code "135") (name "Net-(Q17-PadD)") (class "Default")
      (node (ref "Q17") (pin "D") (pinfunction "D_D") (pintype "passive"))
      (node (ref "Q18") (pin "G") (pinfunction "G_G") (pintype "passive"))
      (node (ref "R17") (pin "1") (pinfunction "1_1") (pintype "passive"))
      (node (ref "R18") (pin "1") (pinfunction "1_1") (pintype "passive"))
    )
    (net (code "136") (name "Net-(Q19-PadD)") (class "Default")
      (node (ref "Q19") (pin "D") (pinfunction "D_D") (pintype "passive"))
      (node (ref "Q20") (pin "G") (pinfunction "G_G") (pintype "passive"))
      (node (ref "R19") (pin "1") (pinfunction "1_1") (pintype "passive"))
      (node (ref "R20") (pin "1") (pinfunction "1_1") (pintype "passive"))
    )
    (net (code "137") (name "Net-(Q21-PadD)") (class "Default")
      (node (ref "Q21") (pin "D") (pinfunction "D_D") (pintype "passive"))
      (node (ref "Q22") (pin "G") (pinfunction "G_G") (pintype "passive"))
      (node (ref "R21") (pin "1") (pinfunction "1_1") (pintype "passive"))
      (node (ref "R22") (pin "1") (pinfunction "1_1") (pintype "passive"))
    )
    (net (code "138") (name "Net-(Q23-PadD)") (class "Default")
      (node (ref "Q23") (pin "D") (pinfunction "D_D") (pintype "passive"))
      (node (ref "Q24") (pin "G") (pinfunction "G_G") (pintype "passive"))
      (node (ref "R23") (pin "1") (pinfunction "1_1") (pintype "passive"))
      (node (ref "R24") (pin "1") (pinfunction "1_1") (pintype "passive"))
    )
    (net (code "139") (name "Net-(Q25-PadD)") (class "Default")
      (node (ref "Q25") (pin "D") (pinfunction "D_D") (pintype "passive"))
      (node (ref "Q26") (pin "G") (pinfunction "G_G") (pintype "passive"))
      (node (ref "R25") (pin "1") (pinfunction "1_1") (pintype "passive"))
      (node (ref "R26") (pin "1") (pinfunction "1_1") (pintype "passive"))
    )
    (net (code "140") (name "Net-(Q27-PadD)") (class "Default")
      (node (ref "Q27") (pin "D") (pinfunction "D_D") (pintype "passive"))
      (node (ref "Q28") (pin "G") (pinfunction "G_G") (pintype "passive"))
      (node (ref "R27") (pin "1") (pinfunction "1_1") (pintype "passive"))
      (node (ref "R28") (pin "1") (pinfunction "1_1") (pintype "passive"))
    )
    (net (code "141") (name "Net-(Q29-PadD)") (class "Default")
      (node (ref "Q29") (pin "D") (pinfunction "D_D") (pintype "passive"))
      (node (ref "Q30") (pin "G") (pinfunction "G_G") (pintype "passive"))
      (node (ref "R29") (pin "1") (pinfunction "1_1") (pintype "passive"))
      (node (ref "R30") (pin "1") (pinfunction "1_1") (pintype "passive"))
    )
    (net (code "142") (name "Net-(Q31-PadD)") (class "Default")
      (node (ref "Q31") (pin "D") (pinfunction "D_D") (pintype "passive"))
      (node (ref "Q32") (pin "G") (pinfunction "G_G") (pintype "passive"))
      (node (ref "R31") (pin "1") (pinfunction "1_1") (pintype "passive"))
      (node (ref "R32") (pin "1") (pinfunction "1_1") (pintype "passive"))
    )
    (net (code "143") (name "Net-(Q33-PadD)") (class "Default")
      (node (ref "Q33") (pin "D") (pinfunction "D_D") (pintype "passive"))
      (node (ref "Q34") (pin "G") (pinfunction "G_G") (pintype "passive"))
      (node (ref "R33") (pin "1") (pinfunction "1_1") (pintype "passive"))
      (node (ref "R34") (pin "1") (pinfunction "1_1") (pintype "passive"))
    )
    (net (code "144") (name "Net-(Q35-PadD)") (class "Default")
      (node (ref "Q35") (pin "D") (pinfunction "D_D") (pintype "passive"))
      (node (ref "Q36") (pin "G") (pinfunction "G_G") (pintype "passive"))
      (node (ref "R35") (pin "1") (pinfunction "1_1") (pintype "passive"))
      (node (ref "R36") (pin "1") (pinfunction "1_1") (pintype "passive"))
    )
    (net (code "145") (name "Net-(Q37-PadD)") (class "Default")
      (node (ref "Q37") (pin "D") (pinfunction "D_D") (pintype "passive"))
      (node (ref "Q38") (pin "G") (pinfunction "G_G") (pintype "passive"))
      (node (ref "R37") (pin "1") (pinfunction "1_1") (pintype "passive"))
      (node (ref "R38") (pin "1") (pinfunction "1_1") (pintype "passive"))
    )
    (net (code "146") (name "Net-(Q39-PadD)") (class "Default")
      (node (ref "Q39") (pin "D") (pinfunction "D_D") (pintype "passive"))
      (node (ref "Q40") (pin "G") (pinfunction "G_G") (pintype "passive"))
      (node (ref "R39") (pin "1") (pinfunction "1_1") (pintype "passive"))
      (node (ref "R40") (pin "1") (pinfunction "1_1") (pintype "passive"))
    )
    (net (code "147") (name "Net-(Q41-PadD)") (class "Default")
      (node (ref "Q41") (pin "D") (pinfunction "D_D") (pintype "passive"))
      (node (ref "Q42") (pin "G") (pinfunction "G_G") (pintype "passive"))
      (node (ref "R41") (pin "1") (pinfunction "1_1") (pintype "passive"))
      (node (ref "R42") (pin "1") (pinfunction "1_1") (pintype "passive"))
    )
    (net (code "148") (name "Net-(Q43-PadD)") (class "Default")
      (node (ref "Q43") (pin "D") (pinfunction "D_D") (pintype "passive"))
      (node (ref "Q44") (pin "G") (pinfunction "G_G") (pintype "passive"))
      (node (ref "R43") (pin "1") (pinfunction "1_1") (pintype "passive"))
      (node (ref "R44") (pin "1") (pinfunction "1_1") (pintype "passive"))
    )
    (net (code "149") (name "Net-(Q45-PadD)") (class "Default")
      (node (ref "Q45") (pin "D") (pinfunction "D_D") (pintype "passive"))
      (node (ref "Q46") (pin "G") (pinfunction "G_G") (pintype "passive"))
      (node (ref "R45") (pin "1") (pinfunction "1_1") (pintype "passive"))
      (node (ref "R46") (pin "1") (pinfunction "1_1") (pintype "passive"))
    )
    (net (code "150") (name "Net-(Q47-PadD)") (class "Default")
      (node (ref "Q47") (pin "D") (pinfunction "D_D") (pintype "passive"))
      (node (ref "Q48") (pin "G") (pinfunction "G_G") (pintype "passive"))
      (node (ref "R47") (pin "1") (pinfunction "1_1") (pintype "passive"))
      (node (ref "R48") (pin "1") (pinfunction "1_1") (pintype "passive"))
    )
    (net (code "151") (name "Net-(Q49-PadD)") (class "Default")
      (node (ref "Q49") (pin "D") (pinfunction "D_D") (pintype "passive"))
      (node (ref "Q50") (pin "G") (pinfunction "G_G") (pintype "passive"))
      (node (ref "R49") (pin "1") (pinfunction "1_1") (pintype "passive"))
      (node (ref "R50") (pin "1") (pinfunction "1_1") (pintype "passive"))
    )
    (net (code "152") (name "Net-(Q51-PadD)") (class "Default")
      (node (ref "Q51") (pin "D") (pinfunction "D_D") (pintype "passive"))
      (node (ref "Q52") (pin "G") (pinfunction "G_G") (pintype "passive"))
      (node (ref "R51") (pin "1") (pinfunction "1_1") (pintype "passive"))
      (node (ref "R52") (pin "1") (pinfunction "1_1") (pintype "passive"))
    )
    (net (code "153") (name "Net-(Q53-PadD)") (class "Default")
      (node (ref "Q53") (pin "D") (pinfunction "D_D") (pintype "passive"))
      (node (ref "Q54") (pin "G") (pinfunction "G_G") (pintype "passive"))
      (node (ref "R53") (pin "1") (pinfunction "1_1") (pintype "passive"))
      (node (ref "R54") (pin "1") (pinfunction "1_1") (pintype "passive"))
    )
    (net (code "154") (name "Net-(Q55-PadD)") (class "Default")
      (node (ref "Q55") (pin "D") (pinfunction "D_D") (pintype "passive"))
      (node (ref "Q56") (pin "G") (pinfunction "G_G") (pintype "passive"))
      (node (ref "R55") (pin "1") (pinfunction "1_1") (pintype "passive"))
      (node (ref "R56") (pin "1") (pinfunction "1_1") (pintype "passive"))
    )
    (net (code "155") (name "Net-(Q57-PadD)") (class "Default")
      (node (ref "Q57") (pin "D") (pinfunction "D_D") (pintype "passive"))
      (node (ref "Q58") (pin "G") (pinfunction "G_G") (pintype "passive"))
      (node (ref "R57") (pin "1") (pinfunction "1_1") (pintype "passive"))
      (node (ref "R58") (pin "1") (pinfunction "1_1") (pintype "passive"))
    )
    (net (code "156") (name "Net-(Q59-PadD)") (class "Default")
      (node (ref "Q59") (pin "D") (pinfunction "D_D") (pintype "passive"))
      (node (ref "Q60") (pin "G") (pinfunction "G_G") (pintype "passive"))
      (node (ref "R59") (pin "1") (pinfunction "1_1") (pintype "passive"))
      (node (ref "R60") (pin "1") (pinfunction "1_1") (pintype "passive"))
    )
    (net (code "157") (name "Net-(Q61-PadD)") (class "Default")
      (node (ref "Q61") (pin "D") (pinfunction "D_D") (pintype "passive"))
      (node (ref "Q62") (pin "G") (pinfunction "G_G") (pintype "passive"))
      (node (ref "R61") (pin "1") (pinfunction "1_1") (pintype "passive"))
      (node (ref "R62") (pin "1") (pinfunction "1_1") (pintype "passive"))
    )
    (net (code "158") (name "Net-(Q63-PadD)") (class "Default")
      (node (ref "Q63") (pin "D") (pinfunction "D_D") (pintype "passive"))
      (node (ref "Q64") (pin "G") (pinfunction "G_G") (pintype "passive"))
      (node (ref "R63") (pin "1") (pinfunction "1_1") (pintype "passive"))
      (node (ref "R64") (pin "1") (pinfunction "1_1") (pintype "passive"))
    )
    (net (code "159") (name "Net-(Q65-PadD)") (class "Default")
      (node (ref "Q65") (pin "D") (pinfunction "D_D") (pintype "passive"))
      (node (ref "Q66") (pin "G") (pinfunction "G_G") (pintype "passive"))
      (node (ref "R65") (pin "1") (pinfunction "1_1") (pintype "passive"))
      (node (ref "R66") (pin "1") (pinfunction "1_1") (pintype "passive"))
    )
    (net (code "160") (name "Net-(Q67-PadD)") (class "Default")
      (node (ref "Q67") (pin "D") (pinfunction "D_D") (pintype "passive"))
      (node (ref "Q68") (pin "G") (pinfunction "G_G") (pintype "passive"))
      (node (ref "R67") (pin "1") (pinfunction "1_1") (pintype "passive"))
      (node (ref "R68") (pin "1") (pinfunction "1_1") (pintype "passive"))
    )
    (net (code "161") (name "Net-(Q69-PadD)") (class "Default")
      (node (ref "Q69") (pin "D") (pinfunction "D_D") (pintype "passive"))
      (node (ref "Q70") (pin "G") (pinfunction "G_G") (pintype "passive"))
      (node (ref "R69") (pin "1") (pinfunction "1_1") (pintype "passive"))
      (node (ref "R70") (pin "1") (pinfunction "1_1") (pintype "passive"))
    )
    (net (code "162") (name "Net-(Q71-PadD)") (class "Default")
      (node (ref "Q71") (pin "D") (pinfunction "D_D") (pintype "passive"))
      (node (ref "Q72") (pin "G") (pinfunction "G_G") (pintype "passive"))
      (node (ref "R71") (pin "1") (pinfunction "1_1") (pintype "passive"))
      (node (ref "R72") (pin "1") (pinfunction "1_1") (pintype "passive"))
    )
    (net (code "163") (name "Net-(Q73-PadD)") (class "Default")
      (node (ref "Q73") (pin "D") (pinfunction "D_D") (pintype "passive"))
      (node (ref "Q74") (pin "G") (pinfunction "G_G") (pintype "passive"))
      (node (ref "R73") (pin "1") (pinfunction "1_1") (pintype "passive"))
      (node (ref "R74") (pin "1") (pinfunction "1_1") (pintype "passive"))
    )
    (net (code "164") (name "Net-(Q75-PadD)") (class "Default")
      (node (ref "Q75") (pin "D") (pinfunction "D_D") (pintype "passive"))
      (node (ref "Q76") (pin "G") (pinfunction "G_G") (pintype "passive"))
      (node (ref "R75") (pin "1") (pinfunction "1_1") (pintype "passive"))
      (node (ref "R76") (pin "1") (pinfunction "1_1") (pintype "passive"))
    )
    (net (code "165") (name "Net-(Q77-PadD)") (class "Default")
      (node (ref "Q77") (pin "D") (pinfunction "D_D") (pintype "passive"))
      (node (ref "Q78") (pin "G") (pinfunction "G_G") (pintype "passive"))
      (node (ref "R77") (pin "1") (pinfunction "1_1") (pintype "passive"))
      (node (ref "R78") (pin "1") (pinfunction "1_1") (pintype "passive"))
    )
    (net (code "166") (name "Net-(Q79-PadD)") (class "Default")
      (node (ref "Q79") (pin "D") (pinfunction "D_D") (pintype "passive"))
      (node (ref "Q80") (pin "G") (pinfunction "G_G") (pintype "passive"))
      (node (ref "R79") (pin "1") (pinfunction "1_1") (pintype "passive"))
      (node (ref "R80") (pin "1") (pinfunction "1_1") (pintype "passive"))
    )
    (net (code "167") (name "Net-(Q81-PadD)") (class "Default")
      (node (ref "Q81") (pin "D") (pinfunction "D_D") (pintype "passive"))
      (node (ref "Q82") (pin "G") (pinfunction "G_G") (pintype "passive"))
      (node (ref "R81") (pin "1") (pinfunction "1_1") (pintype "passive"))
      (node (ref "R82") (pin "1") (pinfunction "1_1") (pintype "passive"))
    )
    (net (code "168") (name "Net-(Q83-PadD)") (class "Default")
      (node (ref "Q83") (pin "D") (pinfunction "D_D") (pintype "passive"))
      (node (ref "Q84") (pin "G") (pinfunction "G_G") (pintype "passive"))
      (node (ref "R83") (pin "1") (pinfunction "1_1") (pintype "passive"))
      (node (ref "R84") (pin "1") (pinfunction "1_1") (pintype "passive"))
    )
    (net (code "169") (name "Net-(Q85-PadD)") (class "Default")
      (node (ref "Q85") (pin "D") (pinfunction "D_D") (pintype "passive"))
      (node (ref "Q86") (pin "G") (pinfunction "G_G") (pintype "passive"))
      (node (ref "R85") (pin "1") (pinfunction "1_1") (pintype "passive"))
      (node (ref "R86") (pin "1") (pinfunction "1_1") (pintype "passive"))
    )
    (net (code "170") (name "Net-(Q87-PadD)") (class "Default")
      (node (ref "Q87") (pin "D") (pinfunction "D_D") (pintype "passive"))
      (node (ref "Q88") (pin "G") (pinfunction "G_G") (pintype "passive"))
      (node (ref "R87") (pin "1") (pinfunction "1_1") (pintype "passive"))
      (node (ref "R88") (pin "1") (pinfunction "1_1") (pintype "passive"))
    )
    (net (code "171") (name "Net-(Q89-PadD)") (class "Default")
      (node (ref "Q89") (pin "D") (pinfunction "D_D") (pintype "passive"))
      (node (ref "Q90") (pin "G") (pinfunction "G_G") (pintype "passive"))
      (node (ref "R89") (pin "1") (pinfunction "1_1") (pintype "passive"))
      (node (ref "R90") (pin "1") (pinfunction "1_1") (pintype "passive"))
    )
    (net (code "172") (name "Net-(Q91-PadD)") (class "Default")
      (node (ref "Q91") (pin "D") (pinfunction "D_D") (pintype "passive"))
      (node (ref "Q92") (pin "G") (pinfunction "G_G") (pintype "passive"))
      (node (ref "R91") (pin "1") (pinfunction "1_1") (pintype "passive"))
      (node (ref "R92") (pin "1") (pinfunction "1_1") (pintype "passive"))
    )
    (net (code "173") (name "Net-(Q93-PadD)") (class "Default")
      (node (ref "Q93") (pin "D") (pinfunction "D_D") (pintype "passive"))
      (node (ref "Q94") (pin "G") (pinfunction "G_G") (pintype "passive"))
      (node (ref "R93") (pin "1") (pinfunction "1_1") (pintype "passive"))
      (node (ref "R94") (pin "1") (pinfunction "1_1") (pintype "passive"))
    )
    (net (code "174") (name "Net-(Q95-PadD)") (class "Default")
      (node (ref "Q95") (pin "D") (pinfunction "D_D") (pintype "passive"))
      (node (ref "Q96") (pin "G") (pinfunction "G_G") (pintype "passive"))
      (node (ref "R95") (pin "1") (pinfunction "1_1") (pintype "passive"))
      (node (ref "R96") (pin "1") (pinfunction "1_1") (pintype "passive"))
    )
    (net (code "175") (name "Net-(Q97-PadD)") (class "Default")
      (node (ref "Q97") (pin "D") (pinfunction "D_D") (pintype "passive"))
      (node (ref "Q98") (pin "G") (pinfunction "G_G") (pintype "passive"))
      (node (ref "R97") (pin "1") (pinfunction "1_1") (pintype "passive"))
      (node (ref "R98") (pin "1") (pinfunction "1_1") (pintype "passive"))
    )
    (net (code "176") (name "Net-(Q100-PadG)") (class "Default")
      (node (ref "Q100") (pin "G") (pinfunction "G_G") (pintype "passive"))
      (node (ref "Q99") (pin "D") (pinfunction "D_D") (pintype "passive"))
      (node (ref "R100") (pin "1") (pinfunction "1_1") (pintype "passive"))
      (node (ref "R99") (pin "1") (pinfunction "1_1") (pintype "passive"))
    )
    (net (code "177") (name "Net-(Q101-PadD)") (class "Default")
      (node (ref "Q101") (pin "D") (pinfunction "D_D") (pintype "passive"))
      (node (ref "Q102") (pin "G") (pinfunction "G_G") (pintype "passive"))
      (node (ref "R101") (pin "1") (pinfunction "1_1") (pintype "passive"))
      (node (ref "R102") (pin "1") (pinfunction "1_1") (pintype "passive"))
    )
    (net (code "178") (name "Net-(Q103-PadD)") (class "Default")
      (node (ref "Q103") (pin "D") (pinfunction "D_D") (pintype "passive"))
      (node (ref "Q104") (pin "G") (pinfunction "G_G") (pintype "passive"))
      (node (ref "R103") (pin "1") (pinfunction "1_1") (pintype "passive"))
      (node (ref "R104") (pin "1") (pinfunction "1_1") (pintype "passive"))
    )
    (net (code "179") (name "Net-(Q105-PadD)") (class "Default")
      (node (ref "Q105") (pin "D") (pinfunction "D_D") (pintype "passive"))
      (node (ref "Q106") (pin "G") (pinfunction "G_G") (pintype "passive"))
      (node (ref "R105") (pin "1") (pinfunction "1_1") (pintype "passive"))
      (node (ref "R106") (pin "1") (pinfunction "1_1") (pintype "passive"))
    )
    (net (code "180") (name "Net-(Q107-PadD)") (class "Default")
      (node (ref "Q107") (pin "D") (pinfunction "D_D") (pintype "passive"))
      (node (ref "Q108") (pin "G") (pinfunction "G_G") (pintype "passive"))
      (node (ref "R107") (pin "1") (pinfunction "1_1") (pintype "passive"))
      (node (ref "R108") (pin "1") (pinfunction "1_1") (pintype "passive"))
    )
    (net (code "181") (name "Net-(Q109-PadD)") (class "Default")
      (node (ref "Q109") (pin "D") (pinfunction "D_D") (pintype "passive"))
      (node (ref "Q110") (pin "G") (pinfunction "G_G") (pintype "passive"))
      (node (ref "R109") (pin "1") (pinfunction "1_1") (pintype "passive"))
      (node (ref "R110") (pin "1") (pinfunction "1_1") (pintype "passive"))
    )
    (net (code "182") (name "Net-(Q111-PadD)") (class "Default")
      (node (ref "Q111") (pin "D") (pinfunction "D_D") (pintype "passive"))
      (node (ref "Q112") (pin "G") (pinfunction "G_G") (pintype "passive"))
      (node (ref "R111") (pin "1") (pinfunction "1_1") (pintype "passive"))
      (node (ref "R112") (pin "1") (pinfunction "1_1") (pintype "passive"))
    )
    (net (code "183") (name "Net-(Q113-PadD)") (class "Default")
      (node (ref "Q113") (pin "D") (pinfunction "D_D") (pintype "passive"))
      (node (ref "Q114") (pin "G") (pinfunction "G_G") (pintype "passive"))
      (node (ref "R113") (pin "1") (pinfunction "1_1") (pintype "passive"))
      (node (ref "R114") (pin "1") (pinfunction "1_1") (pintype "passive"))
    )
    (net (code "184") (name "Net-(Q115-PadD)") (class "Default")
      (node (ref "Q115") (pin "D") (pinfunction "D_D") (pintype "passive"))
      (node (ref "Q116") (pin "G") (pinfunction "G_G") (pintype "passive"))
      (node (ref "R115") (pin "1") (pinfunction "1_1") (pintype "passive"))
      (node (ref "R116") (pin "1") (pinfunction "1_1") (pintype "passive"))
    )
    (net (code "185") (name "Net-(Q117-PadD)") (class "Default")
      (node (ref "Q117") (pin "D") (pinfunction "D_D") (pintype "passive"))
      (node (ref "Q118") (pin "G") (pinfunction "G_G") (pintype "passive"))
      (node (ref "R117") (pin "1") (pinfunction "1_1") (pintype "passive"))
      (node (ref "R118") (pin "1") (pinfunction "1_1") (pintype "passive"))
    )
    (net (code "186") (name "Net-(Q119-PadD)") (class "Default")
      (node (ref "Q119") (pin "D") (pinfunction "D_D") (pintype "passive"))
      (node (ref "Q120") (pin "G") (pinfunction "G_G") (pintype "passive"))
      (node (ref "R119") (pin "1") (pinfunction "1_1") (pintype "passive"))
      (node (ref "R120") (pin "1") (pinfunction "1_1") (pintype "passive"))
    )
    (net (code "187") (name "Net-(Q121-PadD)") (class "Default")
      (node (ref "Q121") (pin "D") (pinfunction "D_D") (pintype "passive"))
      (node (ref "Q122") (pin "G") (pinfunction "G_G") (pintype "passive"))
      (node (ref "R121") (pin "1") (pinfunction "1_1") (pintype "passive"))
      (node (ref "R122") (pin "1") (pinfunction "1_1") (pintype "passive"))
    )
    (net (code "188") (name "Net-(Q123-PadD)") (class "Default")
      (node (ref "Q123") (pin "D") (pinfunction "D_D") (pintype "passive"))
      (node (ref "Q124") (pin "G") (pinfunction "G_G") (pintype "passive"))
      (node (ref "R123") (pin "1") (pinfunction "1_1") (pintype "passive"))
      (node (ref "R124") (pin "1") (pinfunction "1_1") (pintype "passive"))
    )
    (net (code "189") (name "Net-(Q125-PadD)") (class "Default")
      (node (ref "Q125") (pin "D") (pinfunction "D_D") (pintype "passive"))
      (node (ref "Q126") (pin "G") (pinfunction "G_G") (pintype "passive"))
      (node (ref "R125") (pin "1") (pinfunction "1_1") (pintype "passive"))
      (node (ref "R126") (pin "1") (pinfunction "1_1") (pintype "passive"))
    )
    (net (code "190") (name "Net-(Q127-PadD)") (class "Default")
      (node (ref "Q127") (pin "D") (pinfunction "D_D") (pintype "passive"))
      (node (ref "Q128") (pin "G") (pinfunction "G_G") (pintype "passive"))
      (node (ref "R127") (pin "1") (pinfunction "1_1") (pintype "passive"))
      (node (ref "R128") (pin "1") (pinfunction "1_1") (pintype "passive"))
    )
    (net (code "191") (name "Net-(Q141-PadD)") (class "Default")
      (node (ref "Q141") (pin "D") (pinfunction "D_D") (pintype "passive"))
      (node (ref "Q221") (pin "S") (pinfunction "S_S") (pintype "passive"))
    )
    (net (code "192") (name "Net-(Q141-PadS)") (class "Default")
      (node (ref "Q141") (pin "S") (pinfunction "S_S") (pintype "passive"))
      (node (ref "Q143") (pin "D") (pinfunction "D_D") (pintype "passive"))
    )
    (net (code "193") (name "Net-(Q142-PadG)") (class "Default")
      (node (ref "Q142") (pin "G") (pinfunction "G_G") (pintype "passive"))
      (node (ref "Q221") (pin "D") (pinfunction "D_D") (pintype "passive"))
      (node (ref "R145") (pin "1") (pinfunction "1_1") (pintype "passive"))
      (node (ref "R146") (pin "1") (pinfunction "1_1") (pintype "passive"))
    )
    (net (code "194") (name "Net-(Q143-PadS)") (class "Default")
      (node (ref "Q143") (pin "S") (pinfunction "S_S") (pintype "passive"))
      (node (ref "Q144") (pin "D") (pinfunction "D_D") (pintype "passive"))
    )
    (net (code "195") (name "Net-(Q144-PadS)") (class "Default")
      (node (ref "Q144") (pin "S") (pinfunction "S_S") (pintype "passive"))
      (node (ref "Q145") (pin "D") (pinfunction "D_D") (pintype "passive"))
    )
    (net (code "196") (name "Net-(Q146-PadD)") (class "Default")
      (node (ref "Q146") (pin "D") (pinfunction "D_D") (pintype "passive"))
      (node (ref "Q222") (pin "S") (pinfunction "S_S") (pintype "passive"))
    )
    (net (code "197") (name "Net-(Q146-PadS)") (class "Default")
      (node (ref "Q146") (pin "S") (pinfunction "S_S") (pintype "passive"))
      (node (ref "Q148") (pin "D") (pinfunction "D_D") (pintype "passive"))
    )
    (net (code "198") (name "Net-(Q147-PadG)") (class "Default")
      (node (ref "Q147") (pin "G") (pinfunction "G_G") (pintype "passive"))
      (node (ref "Q222") (pin "D") (pinfunction "D_D") (pintype "passive"))
      (node (ref "R147") (pin "1") (pinfunction "1_1") (pintype "passive"))
      (node (ref "R148") (pin "1") (pinfunction "1_1") (pintype "passive"))
    )
    (net (code "199") (name "Net-(Q148-PadS)") (class "Default")
      (node (ref "Q148") (pin "S") (pinfunction "S_S") (pintype "passive"))
      (node (ref "Q149") (pin "D") (pinfunction "D_D") (pintype "passive"))
    )
    (net (code "200") (name "Net-(Q149-PadS)") (class "Default")
      (node (ref "Q149") (pin "S") (pinfunction "S_S") (pintype "passive"))
      (node (ref "Q150") (pin "D") (pinfunction "D_D") (pintype "passive"))
    )
    (net (code "201") (name "Net-(Q151-PadD)") (class "Default")
      (node (ref "Q151") (pin "D") (pinfunction "D_D") (pintype "passive"))
      (node (ref "Q223") (pin "S") (pinfunction "S_S") (pintype "passive"))
    )
    (net (code "202") (name "Net-(Q151-PadS)") (class "Default")
      (node (ref "Q151") (pin "S") (pinfunction "S_S") (pintype "passive"))
      (node (ref "Q153") (pin "D") (pinfunction "D_D") (pintype "passive"))
    )
    (net (code "203") (name "Net-(Q152-PadG)") (class "Default")
      (node (ref "Q152") (pin "G") (pinfunction "G_G") (pintype "passive"))
      (node (ref "Q223") (pin "D") (pinfunction "D_D") (pintype "passive"))
      (node (ref "R149") (pin "1") (pinfunction "1_1") (pintype "passive"))
      (node (ref "R150") (pin "1") (pinfunction "1_1") (pintype "passive"))
    )
    (net (code "204") (name "Net-(Q153-PadS)") (class "Default")
      (node (ref "Q153") (pin "S") (pinfunction "S_S") (pintype "passive"))
      (node (ref "Q154") (pin "D") (pinfunction "D_D") (pintype "passive"))
    )
    (net (code "205") (name "Net-(Q154-PadS)") (class "Default")
      (node (ref "Q154") (pin "S") (pinfunction "S_S") (pintype "passive"))
      (node (ref "Q155") (pin "D") (pinfunction "D_D") (pintype "passive"))
    )
    (net (code "206") (name "Net-(Q156-PadD)") (class "Default")
      (node (ref "Q156") (pin "D") (pinfunction "D_D") (pintype "passive"))
      (node (ref "Q224") (pin "S") (pinfunction "S_S") (pintype "passive"))
    )
    (net (code "207") (name "Net-(Q156-PadS)") (class "Default")
      (node (ref "Q156") (pin "S") (pinfunction "S_S") (pintype "passive"))
      (node (ref "Q158") (pin "D") (pinfunction "D_D") (pintype "passive"))
    )
    (net (code "208") (name "Net-(Q157-PadG)") (class "Default")
      (node (ref "Q157") (pin "G") (pinfunction "G_G") (pintype "passive"))
      (node (ref "Q224") (pin "D") (pinfunction "D_D") (pintype "passive"))
      (node (ref "R151") (pin "1") (pinfunction "1_1") (pintype "passive"))
      (node (ref "R152") (pin "1") (pinfunction "1_1") (pintype "passive"))
    )
    (net (code "209") (name "Net-(Q158-PadS)") (class "Default")
      (node (ref "Q158") (pin "S") (pinfunction "S_S") (pintype "passive"))
      (node (ref "Q159") (pin "D") (pinfunction "D_D") (pintype "passive"))
    )
    (net (code "210") (name "Net-(Q159-PadS)") (class "Default")
      (node (ref "Q159") (pin "S") (pinfunction "S_S") (pintype "passive"))
      (node (ref "Q160") (pin "D") (pinfunction "D_D") (pintype "passive"))
    )
    (net (code "211") (name "Net-(Q161-PadD)") (class "Default")
      (node (ref "Q161") (pin "D") (pinfunction "D_D") (pintype "passive"))
      (node (ref "Q225") (pin "S") (pinfunction "S_S") (pintype "passive"))
    )
    (net (code "212") (name "Net-(Q161-PadS)") (class "Default")
      (node (ref "Q161") (pin "S") (pinfunction "S_S") (pintype "passive"))
      (node (ref "Q163") (pin "D") (pinfunction "D_D") (pintype "passive"))
    )
    (net (code "213") (name "Net-(Q162-PadG)") (class "Default")
      (node (ref "Q162") (pin "G") (pinfunction "G_G") (pintype "passive"))
      (node (ref "Q225") (pin "D") (pinfunction "D_D") (pintype "passive"))
      (node (ref "R153") (pin "1") (pinfunction "1_1") (pintype "passive"))
      (node (ref "R154") (pin "1") (pinfunction "1_1") (pintype "passive"))
    )
    (net (code "214") (name "Net-(Q163-PadS)") (class "Default")
      (node (ref "Q163") (pin "S") (pinfunction "S_S") (pintype "passive"))
      (node (ref "Q164") (pin "D") (pinfunction "D_D") (pintype "passive"))
    )
    (net (code "215") (name "Net-(Q164-PadS)") (class "Default")
      (node (ref "Q164") (pin "S") (pinfunction "S_S") (pintype "passive"))
      (node (ref "Q165") (pin "D") (pinfunction "D_D") (pintype "passive"))
    )
    (net (code "216") (name "Net-(Q166-PadD)") (class "Default")
      (node (ref "Q166") (pin "D") (pinfunction "D_D") (pintype "passive"))
      (node (ref "Q226") (pin "S") (pinfunction "S_S") (pintype "passive"))
    )
    (net (code "217") (name "Net-(Q166-PadS)") (class "Default")
      (node (ref "Q166") (pin "S") (pinfunction "S_S") (pintype "passive"))
      (node (ref "Q168") (pin "D") (pinfunction "D_D") (pintype "passive"))
    )
    (net (code "218") (name "Net-(Q167-PadG)") (class "Default")
      (node (ref "Q167") (pin "G") (pinfunction "G_G") (pintype "passive"))
      (node (ref "Q226") (pin "D") (pinfunction "D_D") (pintype "passive"))
      (node (ref "R155") (pin "1") (pinfunction "1_1") (pintype "passive"))
      (node (ref "R156") (pin "1") (pinfunction "1_1") (pintype "passive"))
    )
    (net (code "219") (name "Net-(Q168-PadS)") (class "Default")
      (node (ref "Q168") (pin "S") (pinfunction "S_S") (pintype "passive"))
      (node (ref "Q169") (pin "D") (pinfunction "D_D") (pintype "passive"))
    )
    (net (code "220") (name "Net-(Q169-PadS)") (class "Default")
      (node (ref "Q169") (pin "S") (pinfunction "S_S") (pintype "passive"))
      (node (ref "Q170") (pin "D") (pinfunction "D_D") (pintype "passive"))
    )
    (net (code "221") (name "Net-(Q171-PadD)") (class "Default")
      (node (ref "Q171") (pin "D") (pinfunction "D_D") (pintype "passive"))
      (node (ref "Q227") (pin "S") (pinfunction "S_S") (pintype "passive"))
    )
    (net (code "222") (name "Net-(Q171-PadS)") (class "Default")
      (node (ref "Q171") (pin "S") (pinfunction "S_S") (pintype "passive"))
      (node (ref "Q173") (pin "D") (pinfunction "D_D") (pintype "passive"))
    )
    (net (code "223") (name "Net-(Q172-PadG)") (class "Default")
      (node (ref "Q172") (pin "G") (pinfunction "G_G") (pintype "passive"))
      (node (ref "Q227") (pin "D") (pinfunction "D_D") (pintype "passive"))
      (node (ref "R157") (pin "1") (pinfunction "1_1") (pintype "passive"))
      (node (ref "R158") (pin "1") (pinfunction "1_1") (pintype "passive"))
    )
    (net (code "224") (name "Net-(Q173-PadS)") (class "Default")
      (node (ref "Q173") (pin "S") (pinfunction "S_S") (pintype "passive"))
      (node (ref "Q174") (pin "D") (pinfunction "D_D") (pintype "passive"))
    )
    (net (code "225") (name "Net-(Q174-PadS)") (class "Default")
      (node (ref "Q174") (pin "S") (pinfunction "S_S") (pintype "passive"))
      (node (ref "Q175") (pin "D") (pinfunction "D_D") (pintype "passive"))
    )
    (net (code "226") (name "Net-(Q176-PadD)") (class "Default")
      (node (ref "Q176") (pin "D") (pinfunction "D_D") (pintype "passive"))
      (node (ref "Q228") (pin "S") (pinfunction "S_S") (pintype "passive"))
    )
    (net (code "227") (name "Net-(Q176-PadS)") (class "Default")
      (node (ref "Q176") (pin "S") (pinfunction "S_S") (pintype "passive"))
      (node (ref "Q178") (pin "D") (pinfunction "D_D") (pintype "passive"))
    )
    (net (code "228") (name "Net-(Q177-PadG)") (class "Default")
      (node (ref "Q177") (pin "G") (pinfunction "G_G") (pintype "passive"))
      (node (ref "Q228") (pin "D") (pinfunction "D_D") (pintype "passive"))
      (node (ref "R159") (pin "1") (pinfunction "1_1") (pintype "passive"))
      (node (ref "R160") (pin "1") (pinfunction "1_1") (pintype "passive"))
    )
    (net (code "229") (name "Net-(Q178-PadS)") (class "Default")
      (node (ref "Q178") (pin "S") (pinfunction "S_S") (pintype "passive"))
      (node (ref "Q179") (pin "D") (pinfunction "D_D") (pintype "passive"))
    )
    (net (code "230") (name "Net-(Q179-PadS)") (class "Default")
      (node (ref "Q179") (pin "S") (pinfunction "S_S") (pintype "passive"))
      (node (ref "Q180") (pin "D") (pinfunction "D_D") (pintype "passive"))
    )
    (net (code "231") (name "Net-(Q181-PadD)") (class "Default")
      (node (ref "Q181") (pin "D") (pinfunction "D_D") (pintype "passive"))
      (node (ref "Q229") (pin "S") (pinfunction "S_S") (pintype "passive"))
    )
    (net (code "232") (name "Net-(Q181-PadS)") (class "Default")
      (node (ref "Q181") (pin "S") (pinfunction "S_S") (pintype "passive"))
      (node (ref "Q183") (pin "D") (pinfunction "D_D") (pintype "passive"))
    )
    (net (code "233") (name "Net-(Q182-PadG)") (class "Default")
      (node (ref "Q182") (pin "G") (pinfunction "G_G") (pintype "passive"))
      (node (ref "Q229") (pin "D") (pinfunction "D_D") (pintype "passive"))
      (node (ref "R161") (pin "1") (pinfunction "1_1") (pintype "passive"))
      (node (ref "R162") (pin "1") (pinfunction "1_1") (pintype "passive"))
    )
    (net (code "234") (name "Net-(Q183-PadS)") (class "Default")
      (node (ref "Q183") (pin "S") (pinfunction "S_S") (pintype "passive"))
      (node (ref "Q184") (pin "D") (pinfunction "D_D") (pintype "passive"))
    )
    (net (code "235") (name "Net-(Q184-PadS)") (class "Default")
      (node (ref "Q184") (pin "S") (pinfunction "S_S") (pintype "passive"))
      (node (ref "Q185") (pin "D") (pinfunction "D_D") (pintype "passive"))
    )
    (net (code "236") (name "Net-(Q186-PadD)") (class "Default")
      (node (ref "Q186") (pin "D") (pinfunction "D_D") (pintype "passive"))
      (node (ref "Q230") (pin "S") (pinfunction "S_S") (pintype "passive"))
    )
    (net (code "237") (name "Net-(Q186-PadS)") (class "Default")
      (node (ref "Q186") (pin "S") (pinfunction "S_S") (pintype "passive"))
      (node (ref "Q188") (pin "D") (pinfunction "D_D") (pintype "passive"))
    )
    (net (code "238") (name "Net-(Q187-PadG)") (class "Default")
      (node (ref "Q187") (pin "G") (pinfunction "G_G") (pintype "passive"))
      (node (ref "Q230") (pin "D") (pinfunction "D_D") (pintype "passive"))
      (node (ref "R163") (pin "1") (pinfunction "1_1") (pintype "passive"))
      (node (ref "R164") (pin "1") (pinfunction "1_1") (pintype "passive"))
    )
    (net (code "239") (name "Net-(Q188-PadS)") (class "Default")
      (node (ref "Q188") (pin "S") (pinfunction "S_S") (pintype "passive"))
      (node (ref "Q189") (pin "D") (pinfunction "D_D") (pintype "passive"))
    )
    (net (code "240") (name "Net-(Q189-PadS)") (class "Default")
      (node (ref "Q189") (pin "S") (pinfunction "S_S") (pintype "passive"))
      (node (ref "Q190") (pin "D") (pinfunction "D_D") (pintype "passive"))
    )
    (net (code "241") (name "Net-(Q191-PadD)") (class "Default")
      (node (ref "Q191") (pin "D") (pinfunction "D_D") (pintype "passive"))
      (node (ref "Q231") (pin "S") (pinfunction "S_S") (pintype "passive"))
    )
    (net (code "242") (name "Net-(Q191-PadS)") (class "Default")
      (node (ref "Q191") (pin "S") (pinfunction "S_S") (pintype "passive"))
      (node (ref "Q193") (pin "D") (pinfunction "D_D") (pintype "passive"))
    )
    (net (code "243") (name "Net-(Q192-PadG)") (class "Default")
      (node (ref "Q192") (pin "G") (pinfunction "G_G") (pintype "passive"))
      (node (ref "Q231") (pin "D") (pinfunction "D_D") (pintype "passive"))
      (node (ref "R165") (pin "1") (pinfunction "1_1") (pintype "passive"))
      (node (ref "R166") (pin "1") (pinfunction "1_1") (pintype "passive"))
    )
    (net (code "244") (name "Net-(Q193-PadS)") (class "Default")
      (node (ref "Q193") (pin "S") (pinfunction "S_S") (pintype "passive"))
      (node (ref "Q194") (pin "D") (pinfunction "D_D") (pintype "passive"))
    )
    (net (code "245") (name "Net-(Q194-PadS)") (class "Default")
      (node (ref "Q194") (pin "S") (pinfunction "S_S") (pintype "passive"))
      (node (ref "Q195") (pin "D") (pinfunction "D_D") (pintype "passive"))
    )
    (net (code "246") (name "Net-(Q196-PadD)") (class "Default")
      (node (ref "Q196") (pin "D") (pinfunction "D_D") (pintype "passive"))
      (node (ref "Q232") (pin "S") (pinfunction "S_S") (pintype "passive"))
    )
    (net (code "247") (name "Net-(Q196-PadS)") (class "Default")
      (node (ref "Q196") (pin "S") (pinfunction "S_S") (pintype "passive"))
      (node (ref "Q198") (pin "D") (pinfunction "D_D") (pintype "passive"))
    )
    (net (code "248") (name "Net-(Q197-PadG)") (class "Default")
      (node (ref "Q197") (pin "G") (pinfunction "G_G") (pintype "passive"))
      (node (ref "Q232") (pin "D") (pinfunction "D_D") (pintype "passive"))
      (node (ref "R167") (pin "1") (pinfunction "1_1") (pintype "passive"))
      (node (ref "R168") (pin "1") (pinfunction "1_1") (pintype "passive"))
    )
    (net (code "249") (name "Net-(Q198-PadS)") (class "Default")
      (node (ref "Q198") (pin "S") (pinfunction "S_S") (pintype "passive"))
      (node (ref "Q199") (pin "D") (pinfunction "D_D") (pintype "passive"))
    )
    (net (code "250") (name "Net-(Q199-PadS)") (class "Default")
      (node (ref "Q199") (pin "S") (pinfunction "S_S") (pintype "passive"))
      (node (ref "Q200") (pin "D") (pinfunction "D_D") (pintype "passive"))
    )
    (net (code "251") (name "Net-(Q201-PadD)") (class "Default")
      (node (ref "Q201") (pin "D") (pinfunction "D_D") (pintype "passive"))
      (node (ref "Q233") (pin "S") (pinfunction "S_S") (pintype "passive"))
    )
    (net (code "252") (name "Net-(Q201-PadS)") (class "Default")
      (node (ref "Q201") (pin "S") (pinfunction "S_S") (pintype "passive"))
      (node (ref "Q203") (pin "D") (pinfunction "D_D") (pintype "passive"))
    )
    (net (code "253") (name "Net-(Q202-PadG)") (class "Default")
      (node (ref "Q202") (pin "G") (pinfunction "G_G") (pintype "passive"))
      (node (ref "Q233") (pin "D") (pinfunction "D_D") (pintype "passive"))
      (node (ref "R169") (pin "1") (pinfunction "1_1") (pintype "passive"))
      (node (ref "R170") (pin "1") (pinfunction "1_1") (pintype "passive"))
    )
    (net (code "254") (name "Net-(Q203-PadS)") (class "Default")
      (node (ref "Q203") (pin "S") (pinfunction "S_S") (pintype "passive"))
      (node (ref "Q204") (pin "D") (pinfunction "D_D") (pintype "passive"))
    )
    (net (code "255") (name "Net-(Q204-PadS)") (class "Default")
      (node (ref "Q204") (pin "S") (pinfunction "S_S") (pintype "passive"))
      (node (ref "Q205") (pin "D") (pinfunction "D_D") (pintype "passive"))
    )
    (net (code "256") (name "Net-(Q206-PadD)") (class "Default")
      (node (ref "Q206") (pin "D") (pinfunction "D_D") (pintype "passive"))
      (node (ref "Q234") (pin "S") (pinfunction "S_S") (pintype "passive"))
    )
    (net (code "257") (name "Net-(Q206-PadS)") (class "Default")
      (node (ref "Q206") (pin "S") (pinfunction "S_S") (pintype "passive"))
      (node (ref "Q208") (pin "D") (pinfunction "D_D") (pintype "passive"))
    )
    (net (code "258") (name "Net-(Q207-PadG)") (class "Default")
      (node (ref "Q207") (pin "G") (pinfunction "G_G") (pintype "passive"))
      (node (ref "Q234") (pin "D") (pinfunction "D_D") (pintype "passive"))
      (node (ref "R171") (pin "1") (pinfunction "1_1") (pintype "passive"))
      (node (ref "R172") (pin "1") (pinfunction "1_1") (pintype "passive"))
    )
    (net (code "259") (name "Net-(Q208-PadS)") (class "Default")
      (node (ref "Q208") (pin "S") (pinfunction "S_S") (pintype "passive"))
      (node (ref "Q209") (pin "D") (pinfunction "D_D") (pintype "passive"))
    )
    (net (code "260") (name "Net-(Q209-PadS)") (class "Default")
      (node (ref "Q209") (pin "S") (pinfunction "S_S") (pintype "passive"))
      (node (ref "Q210") (pin "D") (pinfunction "D_D") (pintype "passive"))
    )
    (net (code "261") (name "Net-(Q211-PadD)") (class "Default")
      (node (ref "Q211") (pin "D") (pinfunction "D_D") (pintype "passive"))
      (node (ref "Q235") (pin "S") (pinfunction "S_S") (pintype "passive"))
    )
    (net (code "262") (name "Net-(Q211-PadS)") (class "Default")
      (node (ref "Q211") (pin "S") (pinfunction "S_S") (pintype "passive"))
      (node (ref "Q213") (pin "D") (pinfunction "D_D") (pintype "passive"))
    )
    (net (code "263") (name "Net-(Q212-PadG)") (class "Default")
      (node (ref "Q212") (pin "G") (pinfunction "G_G") (pintype "passive"))
      (node (ref "Q235") (pin "D") (pinfunction "D_D") (pintype "passive"))
      (node (ref "R173") (pin "1") (pinfunction "1_1") (pintype "passive"))
      (node (ref "R174") (pin "1") (pinfunction "1_1") (pintype "passive"))
    )
    (net (code "264") (name "Net-(Q213-PadS)") (class "Default")
      (node (ref "Q213") (pin "S") (pinfunction "S_S") (pintype "passive"))
      (node (ref "Q214") (pin "D") (pinfunction "D_D") (pintype "passive"))
    )
    (net (code "265") (name "Net-(Q214-PadS)") (class "Default")
      (node (ref "Q214") (pin "S") (pinfunction "S_S") (pintype "passive"))
      (node (ref "Q215") (pin "D") (pinfunction "D_D") (pintype "passive"))
    )
    (net (code "266") (name "Net-(Q216-PadD)") (class "Default")
      (node (ref "Q216") (pin "D") (pinfunction "D_D") (pintype "passive"))
      (node (ref "Q236") (pin "S") (pinfunction "S_S") (pintype "passive"))
    )
    (net (code "267") (name "Net-(Q216-PadS)") (class "Default")
      (node (ref "Q216") (pin "S") (pinfunction "S_S") (pintype "passive"))
      (node (ref "Q218") (pin "D") (pinfunction "D_D") (pintype "passive"))
    )
    (net (code "268") (name "Net-(Q217-PadG)") (class "Default")
      (node (ref "Q217") (pin "G") (pinfunction "G_G") (pintype "passive"))
      (node (ref "Q236") (pin "D") (pinfunction "D_D") (pintype "passive"))
      (node (ref "R175") (pin "1") (pinfunction "1_1") (pintype "passive"))
      (node (ref "R176") (pin "1") (pinfunction "1_1") (pintype "passive"))
    )
    (net (code "269") (name "Net-(Q218-PadS)") (class "Default")
      (node (ref "Q218") (pin "S") (pinfunction "S_S") (pintype "passive"))
      (node (ref "Q219") (pin "D") (pinfunction "D_D") (pintype "passive"))
    )
    (net (code "270") (name "Net-(Q219-PadS)") (class "Default")
      (node (ref "Q219") (pin "S") (pinfunction "S_S") (pintype "passive"))
      (node (ref "Q220") (pin "D") (pinfunction "D_D") (pintype "passive"))
    )
    (net (code "271") (name "Net-(Q237-PadD)") (class "Default")
      (node (ref "Q237") (pin "D") (pinfunction "D_D") (pintype "passive"))
      (node (ref "Q240") (pin "S") (pinfunction "S_S") (pintype "passive"))
    )
    (net (code "272") (name "Net-(Q238-PadS)") (class "Default")
      (node (ref "Q238") (pin "S") (pinfunction "S_S") (pintype "passive"))
      (node (ref "Q239") (pin "D") (pinfunction "D_D") (pintype "passive"))
    )
    (net (code "273") (name "Net-(Q239-PadS)") (class "Default")
      (node (ref "Q239") (pin "S") (pinfunction "S_S") (pintype "passive"))
      (node (ref "Q240") (pin "D") (pinfunction "D_D") (pintype "passive"))
    )
    (net (code "274") (name "S0_D0") (class "Default")
      (node (ref "J1") (pin "2") (pinfunction "2_2") (pintype "bidirectional"))
      (node (ref "Q1") (pin "G") (pinfunction "G_G") (pintype "passive"))
    )
    (net (code "275") (name "S0_D1") (class "Default")
      (node (ref "J1") (pin "3") (pinfunction "3_3") (pintype "bidirectional"))
      (node (ref "Q3") (pin "G") (pinfunction "G_G") (pintype "passive"))
    )
    (net (code "276") (name "S0_D2") (class "Default")
      (node (ref "J1") (pin "4") (pinfunction "4_4") (pintype "bidirectional"))
      (node (ref "Q5") (pin "G") (pinfunction "G_G") (pintype "passive"))
    )
    (net (code "277") (name "S0_D3") (class "Default")
      (node (ref "J1") (pin "5") (pinfunction "5_5") (pintype "bidirectional"))
      (node (ref "Q7") (pin "G") (pinfunction "G_G") (pintype "passive"))
    )
    (net (code "278") (name "S0_D4") (class "Default")
      (node (ref "J1") (pin "6") (pinfunction "6_6") (pintype "bidirectional"))
      (node (ref "Q9") (pin "G") (pinfunction "G_G") (pintype "passive"))
    )
    (net (code "279") (name "S0_D5") (class "Default")
      (node (ref "J1") (pin "7") (pinfunction "7_7") (pintype "bidirectional"))
      (node (ref "Q11") (pin "G") (pinfunction "G_G") (pintype "passive"))
    )
    (net (code "280") (name "S0_D6") (class "Default")
      (node (ref "J1") (pin "8") (pinfunction "8_8") (pintype "bidirectional"))
      (node (ref "Q13") (pin "G") (pinfunction "G_G") (pintype "passive"))
    )
    (net (code "281") (name "S0_D7") (class "Default")
      (node (ref "J1") (pin "9") (pinfunction "9_9") (pintype "bidirectional"))
      (node (ref "Q15") (pin "G") (pinfunction "G_G") (pintype "passive"))
    )
    (net (code "282") (name "S0_D8") (class "Default")
      (node (ref "J1") (pin "12") (pinfunction "12_12") (pintype "bidirectional"))
      (node (ref "Q17") (pin "G") (pinfunction "G_G") (pintype "passive"))
    )
    (net (code "283") (name "S0_D9") (class "Default")
      (node (ref "J1") (pin "13") (pinfunction "13_13") (pintype "bidirectional"))
      (node (ref "Q19") (pin "G") (pinfunction "G_G") (pintype "passive"))
    )
    (net (code "284") (name "S0_D10") (class "Default")
      (node (ref "J1") (pin "14") (pinfunction "14_14") (pintype "bidirectional"))
      (node (ref "Q21") (pin "G") (pinfunction "G_G") (pintype "passive"))
    )
    (net (code "285") (name "S0_D11") (class "Default")
      (node (ref "J1") (pin "15") (pinfunction "15_15") (pintype "bidirectional"))
      (node (ref "Q23") (pin "G") (pinfunction "G_G") (pintype "passive"))
    )
    (net (code "286") (name "S0_D12") (class "Default")
      (node (ref "J1") (pin "16") (pinfunction "16_16") (pintype "bidirectional"))
      (node (ref "Q25") (pin "G") (pinfunction "G_G") (pintype "passive"))
    )
    (net (code "287") (name "S0_D13") (class "Default")
      (node (ref "J1") (pin "17") (pinfunction "17_17") (pintype "bidirectional"))
      (node (ref "Q27") (pin "G") (pinfunction "G_G") (pintype "passive"))
    )
    (net (code "288") (name "S0_D14") (class "Default")
      (node (ref "J1") (pin "18") (pinfunction "18_18") (pintype "bidirectional"))
      (node (ref "Q29") (pin "G") (pinfunction "G_G") (pintype "passive"))
    )
    (net (code "289") (name "S0_D15") (class "Default")
      (node (ref "J1") (pin "19") (pinfunction "19_19") (pintype "bidirectional"))
      (node (ref "Q31") (pin "G") (pinfunction "G_G") (pintype "passive"))
    )
    (net (code "290") (name "S1_D0") (class "Default")
      (node (ref "J2") (pin "2") (pinfunction "2_2") (pintype "bidirectional"))
      (node (ref "Q33") (pin "G") (pinfunction "G_G") (pintype "passive"))
    )
    (net (code "291") (name "S1_D1") (class "Default")
      (node (ref "J2") (pin "3") (pinfunction "3_3") (pintype "bidirectional"))
      (node (ref "Q35") (pin "G") (pinfunction "G_G") (pintype "passive"))
    )
    (net (code "292") (name "S1_D2") (class "Default")
      (node (ref "J2") (pin "4") (pinfunction "4_4") (pintype "bidirectional"))
      (node (ref "Q37") (pin "G") (pinfunction "G_G") (pintype "passive"))
    )
    (net (code "293") (name "S1_D3") (class "Default")
      (node (ref "J2") (pin "5") (pinfunction "5_5") (pintype "bidirectional"))
      (node (ref "Q39") (pin "G") (pinfunction "G_G") (pintype "passive"))
    )
    (net (code "294") (name "S1_D4") (class "Default")
      (node (ref "J2") (pin "6") (pinfunction "6_6") (pintype "bidirectional"))
      (node (ref "Q41") (pin "G") (pinfunction "G_G") (pintype "passive"))
    )
    (net (code "295") (name "S1_D5") (class "Default")
      (node (ref "J2") (pin "7") (pinfunction "7_7") (pintype "bidirectional"))
      (node (ref "Q43") (pin "G") (pinfunction "G_G") (pintype "passive"))
    )
    (net (code "296") (name "S1_D6") (class "Default")
      (node (ref "J2") (pin "8") (pinfunction "8_8") (pintype "bidirectional"))
      (node (ref "Q45") (pin "G") (pinfunction "G_G") (pintype "passive"))
    )
    (net (code "297") (name "S1_D7") (class "Default")
      (node (ref "J2") (pin "9") (pinfunction "9_9") (pintype "bidirectional"))
      (node (ref "Q47") (pin "G") (pinfunction "G_G") (pintype "passive"))
    )
    (net (code "298") (name "S1_D8") (class "Default")
      (node (ref "J2") (pin "12") (pinfunction "12_12") (pintype "bidirectional"))
      (node (ref "Q49") (pin "G") (pinfunction "G_G") (pintype "passive"))
    )
    (net (code "299") (name "S1_D9") (class "Default")
      (node (ref "J2") (pin "13") (pinfunction "13_13") (pintype "bidirectional"))
      (node (ref "Q51") (pin "G") (pinfunction "G_G") (pintype "passive"))
    )
    (net (code "300") (name "S1_D10") (class "Default")
      (node (ref "J2") (pin "14") (pinfunction "14_14") (pintype "bidirectional"))
      (node (ref "Q53") (pin "G") (pinfunction "G_G") (pintype "passive"))
    )
    (net (code "301") (name "S1_D11") (class "Default")
      (node (ref "J2") (pin "15") (pinfunction "15_15") (pintype "bidirectional"))
      (node (ref "Q55") (pin "G") (pinfunction "G_G") (pintype "passive"))
    )
    (net (code "302") (name "S1_D12") (class "Default")
      (node (ref "J2") (pin "16") (pinfunction "16_16") (pintype "bidirectional"))
      (node (ref "Q57") (pin "G") (pinfunction "G_G") (pintype "passive"))
    )
    (net (code "303") (name "S1_D13") (class "Default")
      (node (ref "J2") (pin "17") (pinfunction "17_17") (pintype "bidirectional"))
      (node (ref "Q59") (pin "G") (pinfunction "G_G") (pintype "passive"))
    )
    (net (code "304") (name "S1_D14") (class "Default")
      (node (ref "J2") (pin "18") (pinfunction "18_18") (pintype "bidirectional"))
      (node (ref "Q61") (pin "G") (pinfunction "G_G") (pintype "passive"))
    )
    (net (code "305") (name "S1_D15") (class "Default")
      (node (ref "J2") (pin "19") (pinfunction "19_19") (pintype "bidirectional"))
      (node (ref "Q63") (pin "G") (pinfunction "G_G") (pintype "passive"))
    )
    (net (code "306") (name "S2_D0") (class "Default")
      (node (ref "J3") (pin "2") (pinfunction "2_2") (pintype "bidirectional"))
      (node (ref "Q65") (pin "G") (pinfunction "G_G") (pintype "passive"))
    )
    (net (code "307") (name "S2_D1") (class "Default")
      (node (ref "J3") (pin "3") (pinfunction "3_3") (pintype "bidirectional"))
      (node (ref "Q67") (pin "G") (pinfunction "G_G") (pintype "passive"))
    )
    (net (code "308") (name "S2_D2") (class "Default")
      (node (ref "J3") (pin "4") (pinfunction "4_4") (pintype "bidirectional"))
      (node (ref "Q69") (pin "G") (pinfunction "G_G") (pintype "passive"))
    )
    (net (code "309") (name "S2_D3") (class "Default")
      (node (ref "J3") (pin "5") (pinfunction "5_5") (pintype "bidirectional"))
      (node (ref "Q71") (pin "G") (pinfunction "G_G") (pintype "passive"))
    )
    (net (code "310") (name "S2_D4") (class "Default")
      (node (ref "J3") (pin "6") (pinfunction "6_6") (pintype "bidirectional"))
      (node (ref "Q73") (pin "G") (pinfunction "G_G") (pintype "passive"))
    )
    (net (code "311") (name "S2_D5") (class "Default")
      (node (ref "J3") (pin "7") (pinfunction "7_7") (pintype "bidirectional"))
      (node (ref "Q75") (pin "G") (pinfunction "G_G") (pintype "passive"))
    )
    (net (code "312") (name "S2_D6") (class "Default")
      (node (ref "J3") (pin "8") (pinfunction "8_8") (pintype "bidirectional"))
      (node (ref "Q77") (pin "G") (pinfunction "G_G") (pintype "passive"))
    )
    (net (code "313") (name "S2_D7") (class "Default")
      (node (ref "J3") (pin "9") (pinfunction "9_9") (pintype "bidirectional"))
      (node (ref "Q79") (pin "G") (pinfunction "G_G") (pintype "passive"))
    )
    (net (code "314") (name "S2_D8") (class "Default")
      (node (ref "J3") (pin "12") (pinfunction "12_12") (pintype "bidirectional"))
      (node (ref "Q81") (pin "G") (pinfunction "G_G") (pintype "passive"))
    )
    (net (code "315") (name "S2_D9") (class "Default")
      (node (ref "J3") (pin "13") (pinfunction "13_13") (pintype "bidirectional"))
      (node (ref "Q83") (pin "G") (pinfunction "G_G") (pintype "passive"))
    )
    (net (code "316") (name "S2_D10") (class "Default")
      (node (ref "J3") (pin "14") (pinfunction "14_14") (pintype "bidirectional"))
      (node (ref "Q85") (pin "G") (pinfunction "G_G") (pintype "passive"))
    )
    (net (code "317") (name "S2_D11") (class "Default")
      (node (ref "J3") (pin "15") (pinfunction "15_15") (pintype "bidirectional"))
      (node (ref "Q87") (pin "G") (pinfunction "G_G") (pintype "passive"))
    )
    (net (code "318") (name "S2_D12") (class "Default")
      (node (ref "J3") (pin "16") (pinfunction "16_16") (pintype "bidirectional"))
      (node (ref "Q89") (pin "G") (pinfunction "G_G") (pintype "passive"))
    )
    (net (code "319") (name "S2_D13") (class "Default")
      (node (ref "J3") (pin "17") (pinfunction "17_17") (pintype "bidirectional"))
      (node (ref "Q91") (pin "G") (pinfunction "G_G") (pintype "passive"))
    )
    (net (code "320") (name "S2_D14") (class "Default")
      (node (ref "J3") (pin "18") (pinfunction "18_18") (pintype "bidirectional"))
      (node (ref "Q93") (pin "G") (pinfunction "G_G") (pintype "passive"))
    )
    (net (code "321") (name "S2_D15") (class "Default")
      (node (ref "J3") (pin "19") (pinfunction "19_19") (pintype "bidirectional"))
      (node (ref "Q95") (pin "G") (pinfunction "G_G") (pintype "passive"))
    )
    (net (code "322") (name "S3_D0") (class "Default")
      (node (ref "J4") (pin "2") (pinfunction "2_2") (pintype "bidirectional"))
      (node (ref "Q97") (pin "G") (pinfunction "G_G") (pintype "passive"))
    )
    (net (code "323") (name "S3_D1") (class "Default")
      (node (ref "J4") (pin "3") (pinfunction "3_3") (pintype "bidirectional"))
      (node (ref "Q99") (pin "G") (pinfunction "G_G") (pintype "passive"))
    )
    (net (code "324") (name "S3_D2") (class "Default")
      (node (ref "J4") (pin "4") (pinfunction "4_4") (pintype "bidirectional"))
      (node (ref "Q101") (pin "G") (pinfunction "G_G") (pintype "passive"))
    )
    (net (code "325") (name "S3_D3") (class "Default")
      (node (ref "J4") (pin "5") (pinfunction "5_5") (pintype "bidirectional"))
      (node (ref "Q103") (pin "G") (pinfunction "G_G") (pintype "passive"))
    )
    (net (code "326") (name "S3_D4") (class "Default")
      (node (ref "J4") (pin "6") (pinfunction "6_6") (pintype "bidirectional"))
      (node (ref "Q105") (pin "G") (pinfunction "G_G") (pintype "passive"))
    )
    (net (code "327") (name "S3_D5") (class "Default")
      (node (ref "J4") (pin "7") (pinfunction "7_7") (pintype "bidirectional"))
      (node (ref "Q107") (pin "G") (pinfunction "G_G") (pintype "passive"))
    )
    (net (code "328") (name "S3_D6") (class "Default")
      (node (ref "J4") (pin "8") (pinfunction "8_8") (pintype "bidirectional"))
      (node (ref "Q109") (pin "G") (pinfunction "G_G") (pintype "passive"))
    )
    (net (code "329") (name "S3_D7") (class "Default")
      (node (ref "J4") (pin "9") (pinfunction "9_9") (pintype "bidirectional"))
      (node (ref "Q111") (pin "G") (pinfunction "G_G") (pintype "passive"))
    )
    (net (code "330") (name "S3_D8") (class "Default")
      (node (ref "J4") (pin "12") (pinfunction "12_12") (pintype "bidirectional"))
      (node (ref "Q113") (pin "G") (pinfunction "G_G") (pintype "passive"))
    )
    (net (code "331") (name "S3_D9") (class "Default")
      (node (ref "J4") (pin "13") (pinfunction "13_13") (pintype "bidirectional"))
      (node (ref "Q115") (pin "G") (pinfunction "G_G") (pintype "passive"))
    )
    (net (code "332") (name "S3_D10") (class "Default")
      (node (ref "J4") (pin "14") (pinfunction "14_14") (pintype "bidirectional"))
      (node (ref "Q117") (pin "G") (pinfunction "G_G") (pintype "passive"))
    )
    (net (code "333") (name "S3_D11") (class "Default")
      (node (ref "J4") (pin "15") (pinfunction "15_15") (pintype "bidirectional"))
      (node (ref "Q119") (pin "G") (pinfunction "G_G") (pintype "passive"))
    )
    (net (code "334") (name "S3_D12") (class "Default")
      (node (ref "J4") (pin "16") (pinfunction "16_16") (pintype "bidirectional"))
      (node (ref "Q121") (pin "G") (pinfunction "G_G") (pintype "passive"))
    )
    (net (code "335") (name "S3_D13") (class "Default")
      (node (ref "J4") (pin "17") (pinfunction "17_17") (pintype "bidirectional"))
      (node (ref "Q123") (pin "G") (pinfunction "G_G") (pintype "passive"))
    )
    (net (code "336") (name "S3_D14") (class "Default")
      (node (ref "J4") (pin "18") (pinfunction "18_18") (pintype "bidirectional"))
      (node (ref "Q125") (pin "G") (pinfunction "G_G") (pintype "passive"))
    )
    (net (code "337") (name "S3_D15") (class "Default")
      (node (ref "J4") (pin "19") (pinfunction "19_19") (pintype "bidirectional"))
      (node (ref "Q127") (pin "G") (pinfunction "G_G") (pintype "passive"))
    )
    (net (code "338") (name "SEL0") (class "Default")
      (node (ref "Q129") (pin "G") (pinfunction "G_G") (pintype "passive"))
      (node (ref "TP1") (pin "P$1") (pinfunction "P$1_P$1") (pintype "bidirectional"))
    )
    (net (code "339") (name "SEL1") (class "Default")
      (node (ref "Q132") (pin "G") (pinfunction "G_G") (pintype "passive"))
      (node (ref "TP2") (pin "P$1") (pinfunction "P$1_P$1") (pintype "bidirectional"))
    )
    (net (code "340") (name "SEL2") (class "Default")
      (node (ref "Q135") (pin "G") (pinfunction "G_G") (pintype "passive"))
      (node (ref "TP3") (pin "P$1") (pinfunction "P$1_P$1") (pintype "bidirectional"))
    )
    (net (code "341") (name "SEL3") (class "Default")
      (node (ref "Q138") (pin "G") (pinfunction "G_G") (pintype "passive"))
      (node (ref "TP4") (pin "P$1") (pinfunction "P$1_P$1") (pintype "bidirectional"))
    )
    (net (code "342") (name "T0_D0") (class "Default")
      (node (ref "Q141") (pin "G") (pinfunction "G_G") (pintype "passive"))
      (node (ref "Q2") (pin "D") (pinfunction "D_D") (pintype "passive"))
      (node (ref "R181") (pin "1") (pinfunction "1_1") (pintype "passive"))
    )
    (net (code "343") (name "T0_D1") (class "Default")
      (node (ref "Q146") (pin "G") (pinfunction "G_G") (pintype "passive"))
      (node (ref "Q4") (pin "D") (pinfunction "D_D") (pintype "passive"))
      (node (ref "R182") (pin "1") (pinfunction "1_1") (pintype "passive"))
    )
    (net (code "344") (name "T0_D2") (class "Default")
      (node (ref "Q151") (pin "G") (pinfunction "G_G") (pintype "passive"))
      (node (ref "Q6") (pin "D") (pinfunction "D_D") (pintype "passive"))
      (node (ref "R183") (pin "1") (pinfunction "1_1") (pintype "passive"))
    )
    (net (code "345") (name "T0_D3") (class "Default")
      (node (ref "Q156") (pin "G") (pinfunction "G_G") (pintype "passive"))
      (node (ref "Q8") (pin "D") (pinfunction "D_D") (pintype "passive"))
      (node (ref "R184") (pin "1") (pinfunction "1_1") (pintype "passive"))
    )
    (net (code "346") (name "T0_D4") (class "Default")
      (node (ref "Q10") (pin "D") (pinfunction "D_D") (pintype "passive"))
      (node (ref "Q161") (pin "G") (pinfunction "G_G") (pintype "passive"))
      (node (ref "R185") (pin "1") (pinfunction "1_1") (pintype "passive"))
    )
    (net (code "347") (name "T0_D5") (class "Default")
      (node (ref "Q12") (pin "D") (pinfunction "D_D") (pintype "passive"))
      (node (ref "Q166") (pin "G") (pinfunction "G_G") (pintype "passive"))
      (node (ref "R186") (pin "1") (pinfunction "1_1") (pintype "passive"))
    )
    (net (code "348") (name "T0_D6") (class "Default")
      (node (ref "Q14") (pin "D") (pinfunction "D_D") (pintype "passive"))
      (node (ref "Q171") (pin "G") (pinfunction "G_G") (pintype "passive"))
      (node (ref "R187") (pin "1") (pinfunction "1_1") (pintype "passive"))
    )
    (net (code "349") (name "T0_D7") (class "Default")
      (node (ref "Q16") (pin "D") (pinfunction "D_D") (pintype "passive"))
      (node (ref "Q176") (pin "G") (pinfunction "G_G") (pintype "passive"))
      (node (ref "R188") (pin "1") (pinfunction "1_1") (pintype "passive"))
    )
    (net (code "350") (name "T0_D8") (class "Default")
      (node (ref "Q18") (pin "D") (pinfunction "D_D") (pintype "passive"))
      (node (ref "Q181") (pin "G") (pinfunction "G_G") (pintype "passive"))
      (node (ref "R189") (pin "1") (pinfunction "1_1") (pintype "passive"))
    )
    (net (code "351") (name "T0_D9") (class "Default")
      (node (ref "Q186") (pin "G") (pinfunction "G_G") (pintype "passive"))
      (node (ref "Q20") (pin "D") (pinfunction "D_D") (pintype "passive"))
      (node (ref "R190") (pin "1") (pinfunction "1_1") (pintype "passive"))
    )
    (net (code "352") (name "T0_D10") (class "Default")
      (node (ref "Q191") (pin "G") (pinfunction "G_G") (pintype "passive"))
      (node (ref "Q22") (pin "D") (pinfunction "D_D") (pintype "passive"))
      (node (ref "R191") (pin "1") (pinfunction "1_1") (pintype "passive"))
    )
    (net (code "353") (name "T0_D11") (class "Default")
      (node (ref "Q196") (pin "G") (pinfunction "G_G") (pintype "passive"))
      (node (ref "Q24") (pin "D") (pinfunction "D_D") (pintype "passive"))
      (node (ref "R192") (pin "1") (pinfunction "1_1") (pintype "passive"))
    )
    (net (code "354") (name "T0_D12") (class "Default")
      (node (ref "Q201") (pin "G") (pinfunction "G_G") (pintype "passive"))
      (node (ref "Q26") (pin "D") (pinfunction "D_D") (pintype "passive"))
      (node (ref "R193") (pin "1") (pinfunction "1_1") (pintype "passive"))
    )
    (net (code "355") (name "T0_D13") (class "Default")
      (node (ref "Q206") (pin "G") (pinfunction "G_G") (pintype "passive"))
      (node (ref "Q28") (pin "D") (pinfunction "D_D") (pintype "passive"))
      (node (ref "R194") (pin "1") (pinfunction "1_1") (pintype "passive"))
    )
    (net (code "356") (name "T0_D14") (class "Default")
      (node (ref "Q211") (pin "G") (pinfunction "G_G") (pintype "passive"))
      (node (ref "Q30") (pin "D") (pinfunction "D_D") (pintype "passive"))
      (node (ref "R195") (pin "1") (pinfunction "1_1") (pintype "passive"))
    )
    (net (code "357") (name "T0_D15") (class "Default")
      (node (ref "Q216") (pin "G") (pinfunction "G_G") (pintype "passive"))
      (node (ref "Q32") (pin "D") (pinfunction "D_D") (pintype "passive"))
      (node (ref "R196") (pin "1") (pinfunction "1_1") (pintype "passive"))
    )
    (net (code "358") (name "T1_D0") (class "Default")
      (node (ref "Q143") (pin "G") (pinfunction "G_G") (pintype "passive"))
      (node (ref "Q34") (pin "D") (pinfunction "D_D") (pintype "passive"))
      (node (ref "R197") (pin "1") (pinfunction "1_1") (pintype "passive"))
    )
    (net (code "359") (name "T1_D1") (class "Default")
      (node (ref "Q148") (pin "G") (pinfunction "G_G") (pintype "passive"))
      (node (ref "Q36") (pin "D") (pinfunction "D_D") (pintype "passive"))
      (node (ref "R198") (pin "1") (pinfunction "1_1") (pintype "passive"))
    )
    (net (code "360") (name "T1_D2") (class "Default")
      (node (ref "Q153") (pin "G") (pinfunction "G_G") (pintype "passive"))
      (node (ref "Q38") (pin "D") (pinfunction "D_D") (pintype "passive"))
      (node (ref "R199") (pin "1") (pinfunction "1_1") (pintype "passive"))
    )
    (net (code "361") (name "T1_D3") (class "Default")
      (node (ref "Q158") (pin "G") (pinfunction "G_G") (pintype "passive"))
      (node (ref "Q40") (pin "D") (pinfunction "D_D") (pintype "passive"))
      (node (ref "R200") (pin "1") (pinfunction "1_1") (pintype "passive"))
    )
    (net (code "362") (name "T1_D4") (class "Default")
      (node (ref "Q163") (pin "G") (pinfunction "G_G") (pintype "passive"))
      (node (ref "Q42") (pin "D") (pinfunction "D_D") (pintype "passive"))
      (node (ref "R201") (pin "1") (pinfunction "1_1") (pintype "passive"))
    )
    (net (code "363") (name "T1_D5") (class "Default")
      (node (ref "Q168") (pin "G") (pinfunction "G_G") (pintype "passive"))
      (node (ref "Q44") (pin "D") (pinfunction "D_D") (pintype "passive"))
      (node (ref "R202") (pin "1") (pinfunction "1_1") (pintype "passive"))
    )
    (net (code "364") (name "T1_D6") (class "Default")
      (node (ref "Q173") (pin "G") (pinfunction "G_G") (pintype "passive"))
      (node (ref "Q46") (pin "D") (pinfunction "D_D") (pintype "passive"))
      (node (ref "R203") (pin "1") (pinfunction "1_1") (pintype "passive"))
    )
    (net (code "365") (name "T1_D7") (class "Default")
      (node (ref "Q178") (pin "G") (pinfunction "G_G") (pintype "passive"))
      (node (ref "Q48") (pin "D") (pinfunction "D_D") (pintype "passive"))
      (node (ref "R204") (pin "1") (pinfunction "1_1") (pintype "passive"))
    )
    (net (code "366") (name "T1_D8") (class "Default")
      (node (ref "Q183") (pin "G") (pinfunction "G_G") (pintype "passive"))
      (node (ref "Q50") (pin "D") (pinfunction "D_D") (pintype "passive"))
      (node (ref "R205") (pin "1") (pinfunction "1_1") (pintype "passive"))
    )
    (net (code "367") (name "T1_D9") (class "Default")
      (node (ref "Q188") (pin "G") (pinfunction "G_G") (pintype "passive"))
      (node (ref "Q52") (pin "D") (pinfunction "D_D") (pintype "passive"))
      (node (ref "R206") (pin "1") (pinfunction "1_1") (pintype "passive"))
    )
    (net (code "368") (name "T1_D10") (class "Default")
      (node (ref "Q193") (pin "G") (pinfunction "G_G") (pintype "passive"))
      (node (ref "Q54") (pin "D") (pinfunction "D_D") (pintype "passive"))
      (node (ref "R207") (pin "1") (pinfunction "1_1") (pintype "passive"))
    )
    (net (code "369") (name "T1_D11") (class "Default")
      (node (ref "Q198") (pin "G") (pinfunction "G_G") (pintype "passive"))
      (node (ref "Q56") (pin "D") (pinfunction "D_D") (pintype "passive"))
      (node (ref "R208") (pin "1") (pinfunction "1_1") (pintype "passive"))
    )
    (net (code "370") (name "T1_D12") (class "Default")
      (node (ref "Q203") (pin "G") (pinfunction "G_G") (pintype "passive"))
      (node (ref "Q58") (pin "D") (pinfunction "D_D") (pintype "passive"))
      (node (ref "R209") (pin "1") (pinfunction "1_1") (pintype "passive"))
    )
    (net (code "371") (name "T1_D13") (class "Default")
      (node (ref "Q208") (pin "G") (pinfunction "G_G") (pintype "passive"))
      (node (ref "Q60") (pin "D") (pinfunction "D_D") (pintype "passive"))
      (node (ref "R210") (pin "1") (pinfunction "1_1") (pintype "passive"))
    )
    (net (code "372") (name "T1_D14") (class "Default")
      (node (ref "Q213") (pin "G") (pinfunction "G_G") (pintype "passive"))
      (node (ref "Q62") (pin "D") (pinfunction "D_D") (pintype "passive"))
      (node (ref "R211") (pin "1") (pinfunction "1_1") (pintype "passive"))
    )
    (net (code "373") (name "T1_D15") (class "Default")
      (node (ref "Q218") (pin "G") (pinfunction "G_G") (pintype "passive"))
      (node (ref "Q64") (pin "D") (pinfunction "D_D") (pintype "passive"))
      (node (ref "R212") (pin "1") (pinfunction "1_1") (pintype "passive"))
    )
    (net (code "374") (name "T2_D0") (class "Default")
      (node (ref "Q144") (pin "G") (pinfunction "G_G") (pintype "passive"))
      (node (ref "Q66") (pin "D") (pinfunction "D_D") (pintype "passive"))
      (node (ref "R213") (pin "1") (pinfunction "1_1") (pintype "passive"))
    )
    (net (code "375") (name "T2_D1") (class "Default")
      (node (ref "Q149") (pin "G") (pinfunction "G_G") (pintype "passive"))
      (node (ref "Q68") (pin "D") (pinfunction "D_D") (pintype "passive"))
      (node (ref "R214") (pin "1") (pinfunction "1_1") (pintype "passive"))
    )
    (net (code "376") (name "T2_D2") (class "Default")
      (node (ref "Q154") (pin "G") (pinfunction "G_G") (pintype "passive"))
      (node (ref "Q70") (pin "D") (pinfunction "D_D") (pintype "passive"))
      (node (ref "R215") (pin "1") (pinfunction "1_1") (pintype "passive"))
    )
    (net (code "377") (name "T2_D3") (class "Default")
      (node (ref "Q159") (pin "G") (pinfunction "G_G") (pintype "passive"))
      (node (ref "Q72") (pin "D") (pinfunction "D_D") (pintype "passive"))
      (node (ref "R216") (pin "1") (pinfunction "1_1") (pintype "passive"))
    )
    (net (code "378") (name "T2_D4") (class "Default")
      (node (ref "Q164") (pin "G") (pinfunction "G_G") (pintype "passive"))
      (node (ref "Q74") (pin "D") (pinfunction "D_D") (pintype "passive"))
      (node (ref "R217") (pin "1") (pinfunction "1_1") (pintype "passive"))
    )
    (net (code "379") (name "T2_D5") (class "Default")
      (node (ref "Q169") (pin "G") (pinfunction "G_G") (pintype "passive"))
      (node (ref "Q76") (pin "D") (pinfunction "D_D") (pintype "passive"))
      (node (ref "R218") (pin "1") (pinfunction "1_1") (pintype "passive"))
    )
    (net (code "380") (name "T2_D6") (class "Default")
      (node (ref "Q174") (pin "G") (pinfunction "G_G") (pintype "passive"))
      (node (ref "Q78") (pin "D") (pinfunction "D_D") (pintype "passive"))
      (node (ref "R219") (pin "1") (pinfunction "1_1") (pintype "passive"))
    )
    (net (code "381") (name "T2_D7") (class "Default")
      (node (ref "Q179") (pin "G") (pinfunction "G_G") (pintype "passive"))
      (node (ref "Q80") (pin "D") (pinfunction "D_D") (pintype "passive"))
      (node (ref "R220") (pin "1") (pinfunction "1_1") (pintype "passive"))
    )
    (net (code "382") (name "T2_D8") (class "Default")
      (node (ref "Q184") (pin "G") (pinfunction "G_G") (pintype "passive"))
      (node (ref "Q82") (pin "D") (pinfunction "D_D") (pintype "passive"))
      (node (ref "R221") (pin "1") (pinfunction "1_1") (pintype "passive"))
    )
    (net (code "383") (name "T2_D9") (class "Default")
      (node (ref "Q189") (pin "G") (pinfunction "G_G") (pintype "passive"))
      (node (ref "Q84") (pin "D") (pinfunction "D_D") (pintype "passive"))
      (node (ref "R222") (pin "1") (pinfunction "1_1") (pintype "passive"))
    )
    (net (code "384") (name "T2_D10") (class "Default")
      (node (ref "Q194") (pin "G") (pinfunction "G_G") (pintype "passive"))
      (node (ref "Q86") (pin "D") (pinfunction "D_D") (pintype "passive"))
      (node (ref "R223") (pin "1") (pinfunction "1_1") (pintype "passive"))
    )
    (net (code "385") (name "T2_D11") (class "Default")
      (node (ref "Q199") (pin "G") (pinfunction "G_G") (pintype "passive"))
      (node (ref "Q88") (pin "D") (pinfunction "D_D") (pintype "passive"))
      (node (ref "R224") (pin "1") (pinfunction "1_1") (pintype "passive"))
    )
    (net (code "386") (name "T2_D12") (class "Default")
      (node (ref "Q204") (pin "G") (pinfunction "G_G") (pintype "passive"))
      (node (ref "Q90") (pin "D") (pinfunction "D_D") (pintype "passive"))
      (node (ref "R225") (pin "1") (pinfunction "1_1") (pintype "passive"))
    )
    (net (code "387") (name "T2_D13") (class "Default")
      (node (ref "Q209") (pin "G") (pinfunction "G_G") (pintype "passive"))
      (node (ref "Q92") (pin "D") (pinfunction "D_D") (pintype "passive"))
      (node (ref "R226") (pin "1") (pinfunction "1_1") (pintype "passive"))
    )
    (net (code "388") (name "T2_D14") (class "Default")
      (node (ref "Q214") (pin "G") (pinfunction "G_G") (pintype "passive"))
      (node (ref "Q94") (pin "D") (pinfunction "D_D") (pintype "passive"))
      (node (ref "R227") (pin "1") (pinfunction "1_1") (pintype "passive"))
    )
    (net (code "389") (name "T2_D15") (class "Default")
      (node (ref "Q219") (pin "G") (pinfunction "G_G") (pintype "passive"))
      (node (ref "Q96") (pin "D") (pinfunction "D_D") (pintype "passive"))
      (node (ref "R228") (pin "1") (pinfunction "1_1") (pintype "passive"))
    )
    (net (code "390") (name "T3_D0") (class "Default")
      (node (ref "Q145") (pin "G") (pinfunction "G_G") (pintype "passive"))
      (node (ref "Q98") (pin "D") (pinfunction "D_D") (pintype "passive"))
      (node (ref "R229") (pin "1") (pinfunction "1_1") (pintype "passive"))
    )
    (net (code "391") (name "T3_D1") (class "Default")
      (node (ref "Q100") (pin "D") (pinfunction "D_D") (pintype "passive"))
      (node (ref "Q150") (pin "G") (pinfunction "G_G") (pintype "passive"))
      (node (ref "R230") (pin "1") (pinfunction "1_1") (pintype "passive"))
    )
    (net (code "392") (name "T3_D2") (class "Default")
      (node (ref "Q102") (pin "D") (pinfunction "D_D") (pintype "passive"))
      (node (ref "Q155") (pin "G") (pinfunction "G_G") (pintype "passive"))
      (node (ref "R231") (pin "1") (pinfunction "1_1") (pintype "passive"))
    )
    (net (code "393") (name "T3_D3") (class "Default")
      (node (ref "Q104") (pin "D") (pinfunction "D_D") (pintype "passive"))
      (node (ref "Q160") (pin "G") (pinfunction "G_G") (pintype "passive"))
      (node (ref "R232") (pin "1") (pinfunction "1_1") (pintype "passive"))
    )
    (net (code "394") (name "T3_D4") (class "Default")
      (node (ref "Q106") (pin "D") (pinfunction "D_D") (pintype "passive"))
      (node (ref "Q165") (pin "G") (pinfunction "G_G") (pintype "passive"))
      (node (ref "R233") (pin "1") (pinfunction "1_1") (pintype "passive"))
    )
    (net (code "395") (name "T3_D5") (class "Default")
      (node (ref "Q108") (pin "D") (pinfunction "D_D") (pintype "passive"))
      (node (ref "Q170") (pin "G") (pinfunction "G_G") (pintype "passive"))
      (node (ref "R234") (pin "1") (pinfunction "1_1") (pintype "passive"))
    )
    (net (code "396") (name "T3_D6") (class "Default")
      (node (ref "Q110") (pin "D") (pinfunction "D_D") (pintype "passive"))
      (node (ref "Q175") (pin "G") (pinfunction "G_G") (pintype "passive"))
      (node (ref "R235") (pin "1") (pinfunction "1_1") (pintype "passive"))
    )
    (net (code "397") (name "T3_D7") (class "Default")
      (node (ref "Q112") (pin "D") (pinfunction "D_D") (pintype "passive"))
      (node (ref "Q180") (pin "G") (pinfunction "G_G") (pintype "passive"))
      (node (ref "R236") (pin "1") (pinfunction "1_1") (pintype "passive"))
    )
    (net (code "398") (name "T3_D8") (class "Default")
      (node (ref "Q114") (pin "D") (pinfunction "D_D") (pintype "passive"))
      (node (ref "Q185") (pin "G") (pinfunction "G_G") (pintype "passive"))
      (node (ref "R237") (pin "1") (pinfunction "1_1") (pintype "passive"))
    )
    (net (code "399") (name "T3_D9") (class "Default")
      (node (ref "Q116") (pin "D") (pinfunction "D_D") (pintype "passive"))
      (node (ref "Q190") (pin "G") (pinfunction "G_G") (pintype "passive"))
      (node (ref "R238") (pin "1") (pinfunction "1_1") (pintype "passive"))
    )
    (net (code "400") (name "T3_D10") (class "Default")
      (node (ref "Q118") (pin "D") (pinfunction "D_D") (pintype "passive"))
      (node (ref "Q195") (pin "G") (pinfunction "G_G") (pintype "passive"))
      (node (ref "R239") (pin "1") (pinfunction "1_1") (pintype "passive"))
    )
    (net (code "401") (name "T3_D11") (class "Default")
      (node (ref "Q120") (pin "D") (pinfunction "D_D") (pintype "passive"))
      (node (ref "Q200") (pin "G") (pinfunction "G_G") (pintype "passive"))
      (node (ref "R240") (pin "1") (pinfunction "1_1") (pintype "passive"))
    )
    (net (code "402") (name "T3_D12") (class "Default")
      (node (ref "Q122") (pin "D") (pinfunction "D_D") (pintype "passive"))
      (node (ref "Q205") (pin "G") (pinfunction "G_G") (pintype "passive"))
      (node (ref "R241") (pin "1") (pinfunction "1_1") (pintype "passive"))
    )
    (net (code "403") (name "T3_D13") (class "Default")
      (node (ref "Q124") (pin "D") (pinfunction "D_D") (pintype "passive"))
      (node (ref "Q210") (pin "G") (pinfunction "G_G") (pintype "passive"))
      (node (ref "R242") (pin "1") (pinfunction "1_1") (pintype "passive"))
    )
    (net (code "404") (name "T3_D14") (class "Default")
      (node (ref "Q126") (pin "D") (pinfunction "D_D") (pintype "passive"))
      (node (ref "Q215") (pin "G") (pinfunction "G_G") (pintype "passive"))
      (node (ref "R243") (pin "1") (pinfunction "1_1") (pintype "passive"))
    )
    (net (code "405") (name "T3_D15") (class "Default")
      (node (ref "Q128") (pin "D") (pinfunction "D_D") (pintype "passive"))
      (node (ref "Q220") (pin "G") (pinfunction "G_G") (pintype "passive"))
      (node (ref "R244") (pin "1") (pinfunction "1_1") (pintype "passive"))
    )
  )
)
